# SCH_3_0-CONTROLADORA-PARA-PS2_2024-07-29.net
KiCad netlist of a schematic drawn in EasyEDA
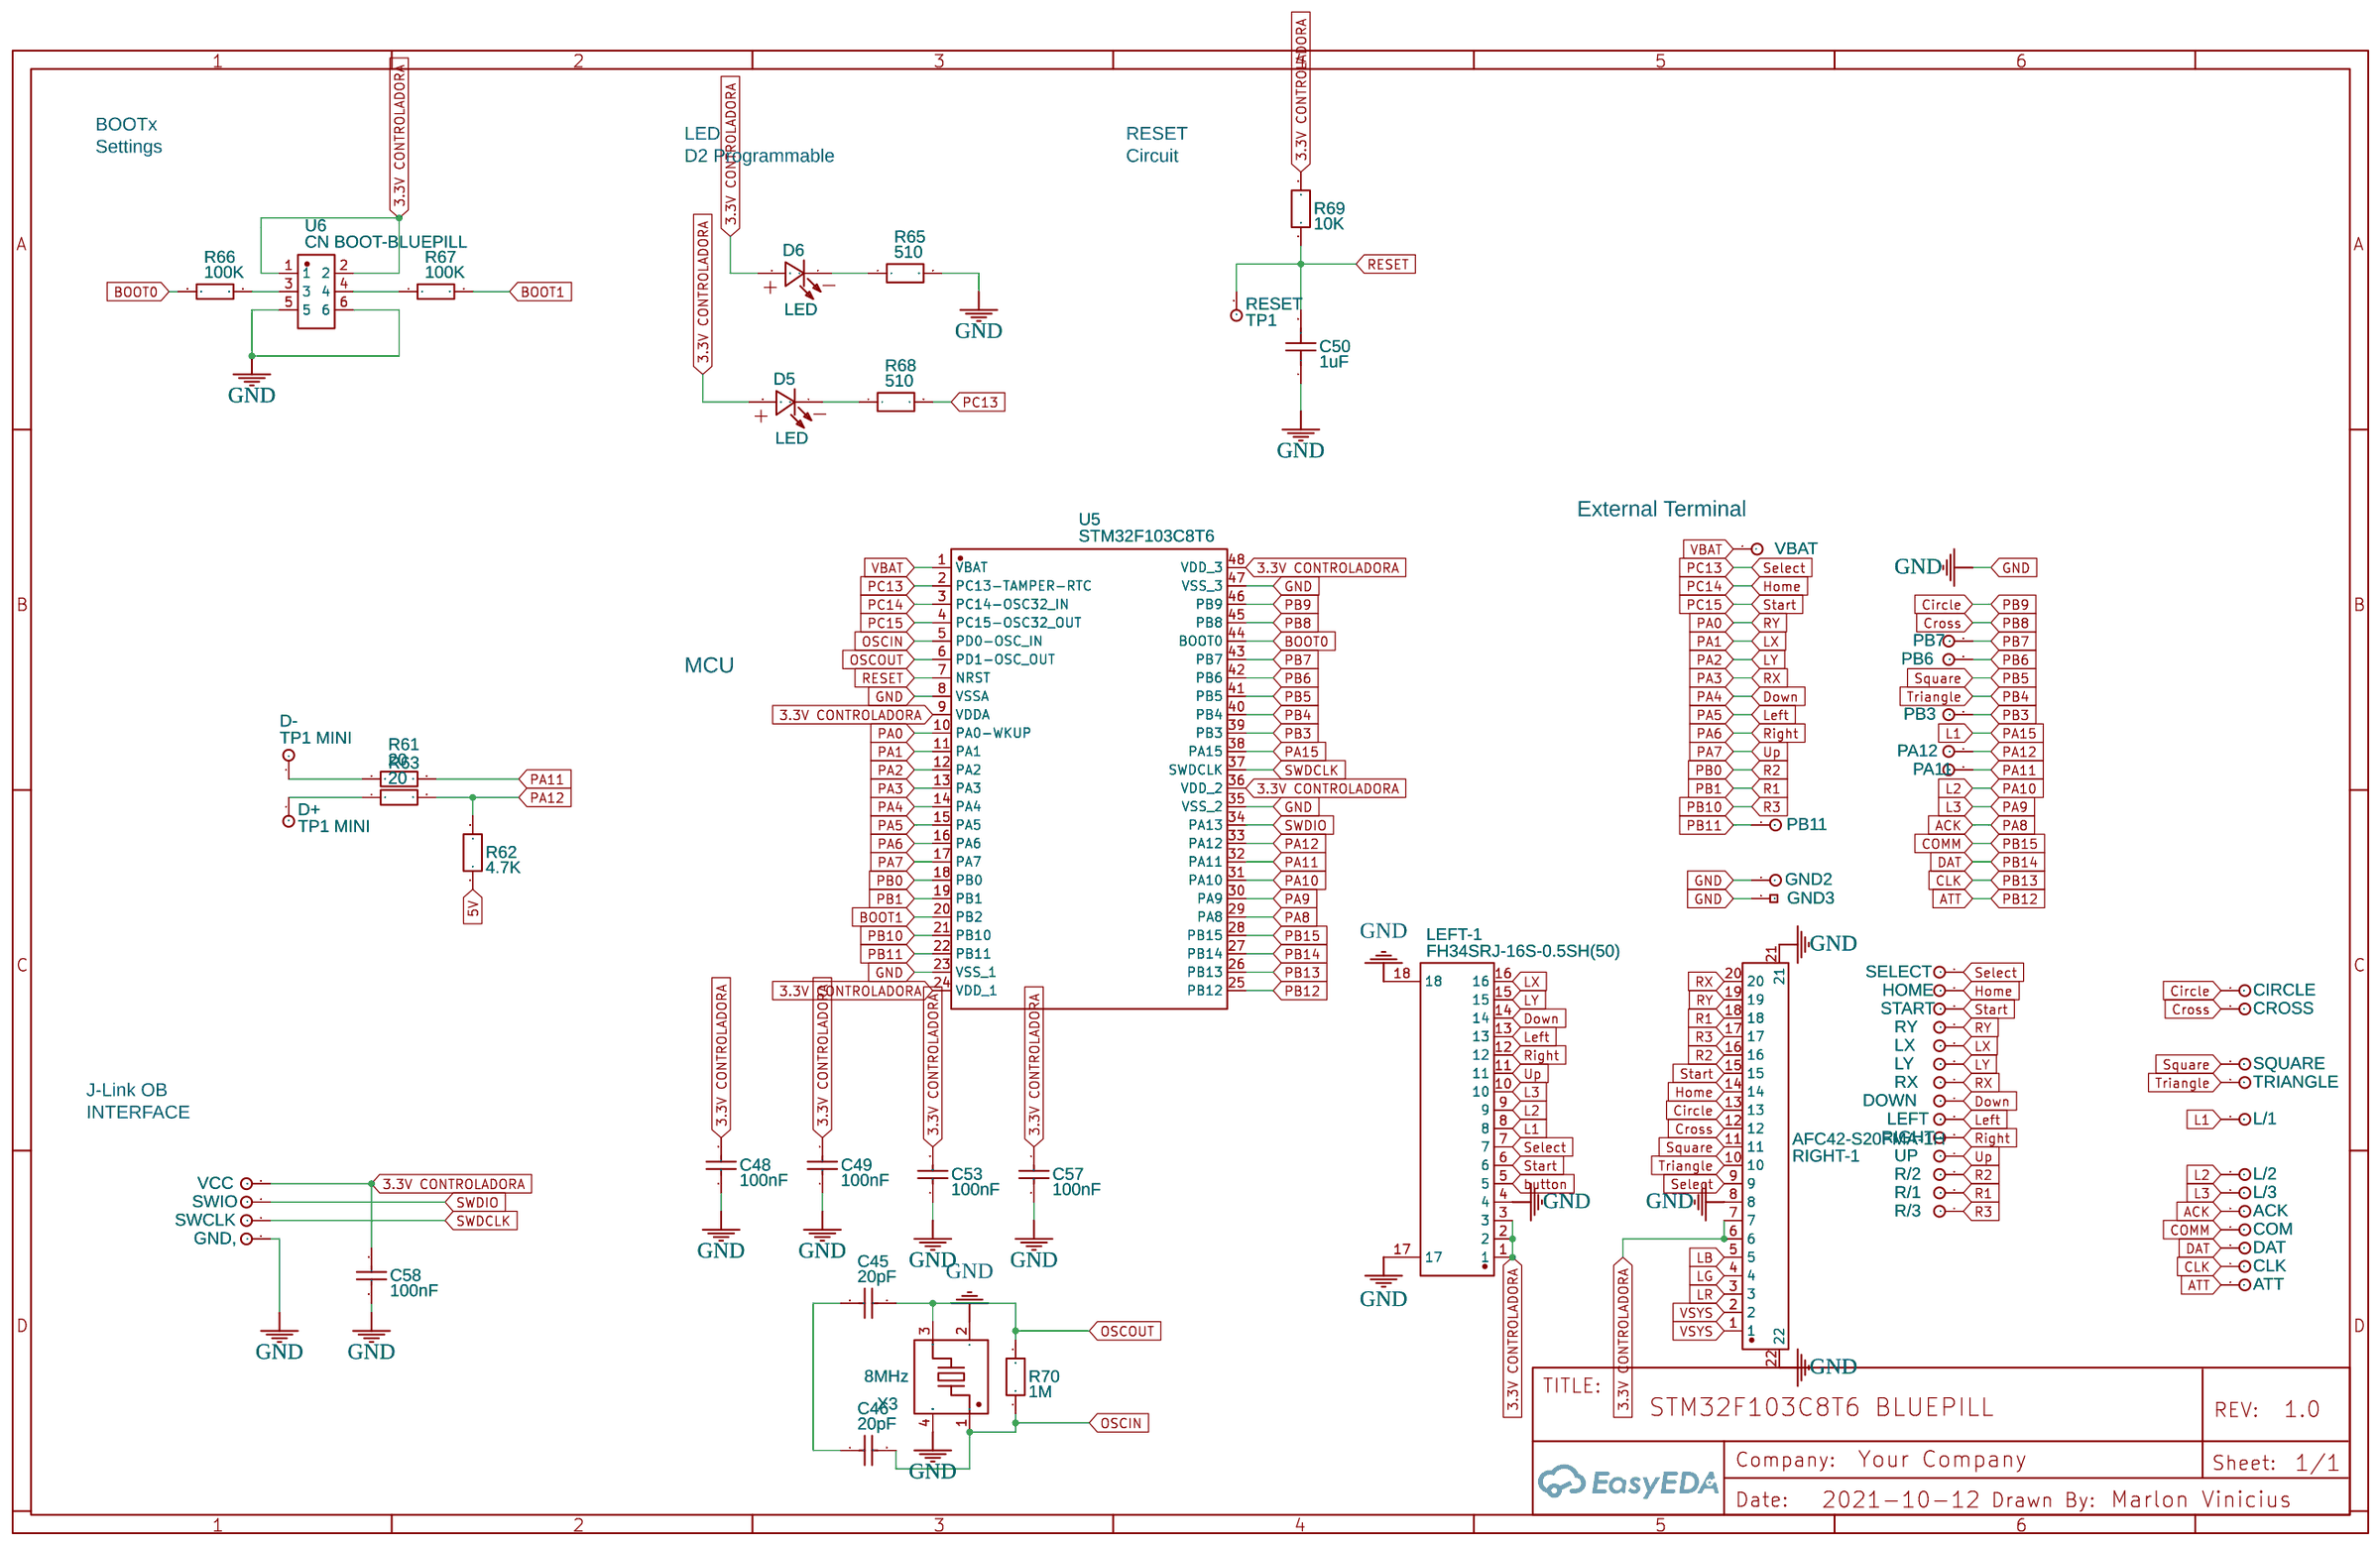
[diagram p0: STM32 BLUEPILL copy]
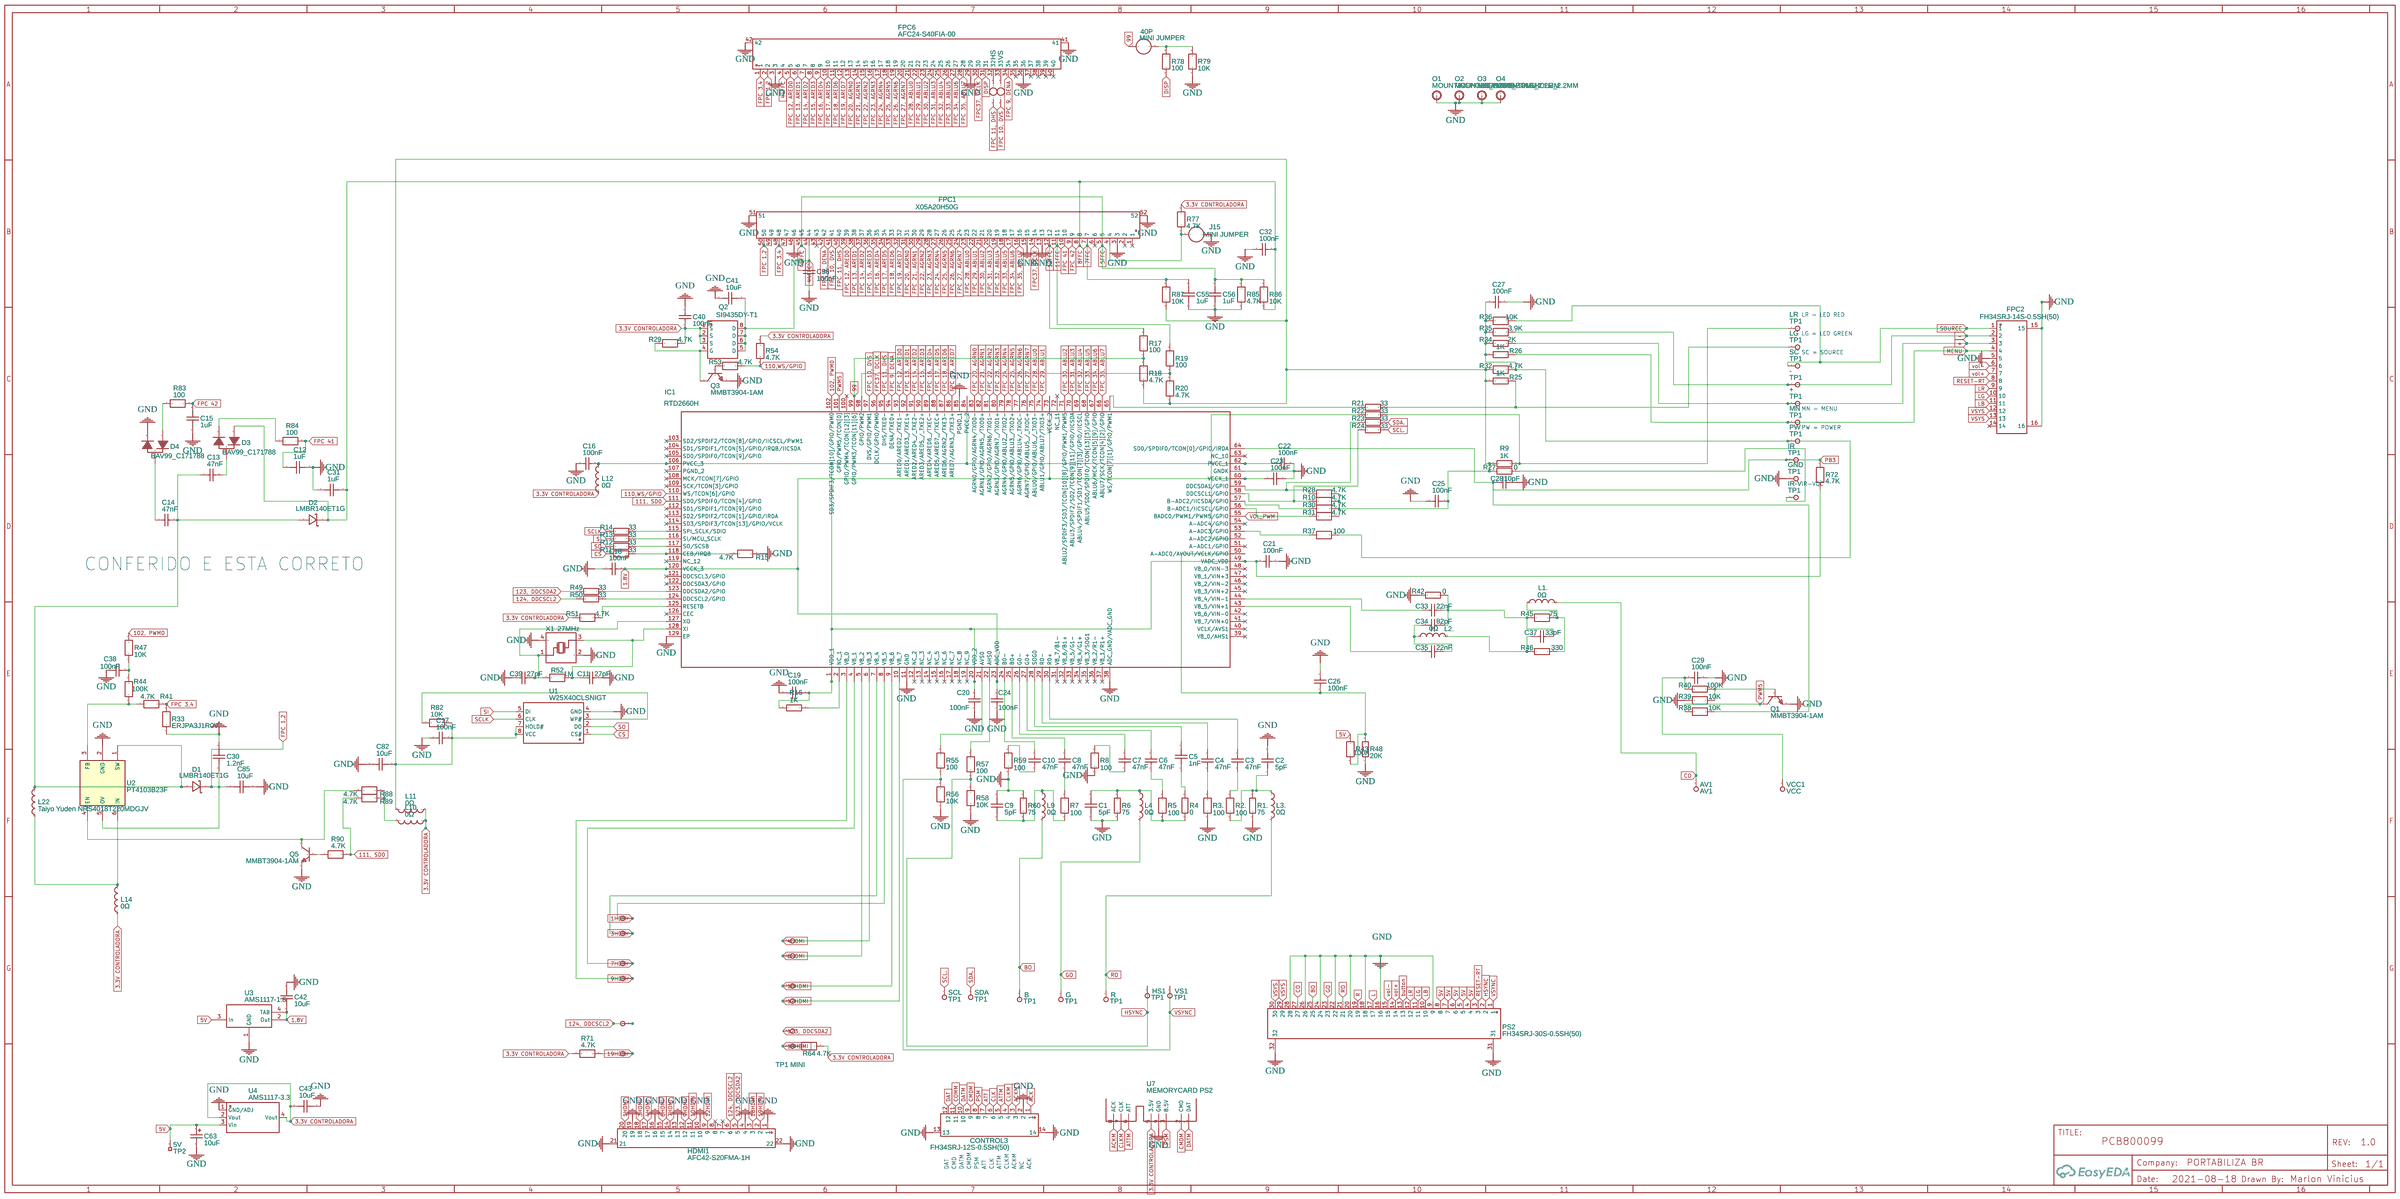
[diagram p1: Controladora copy]
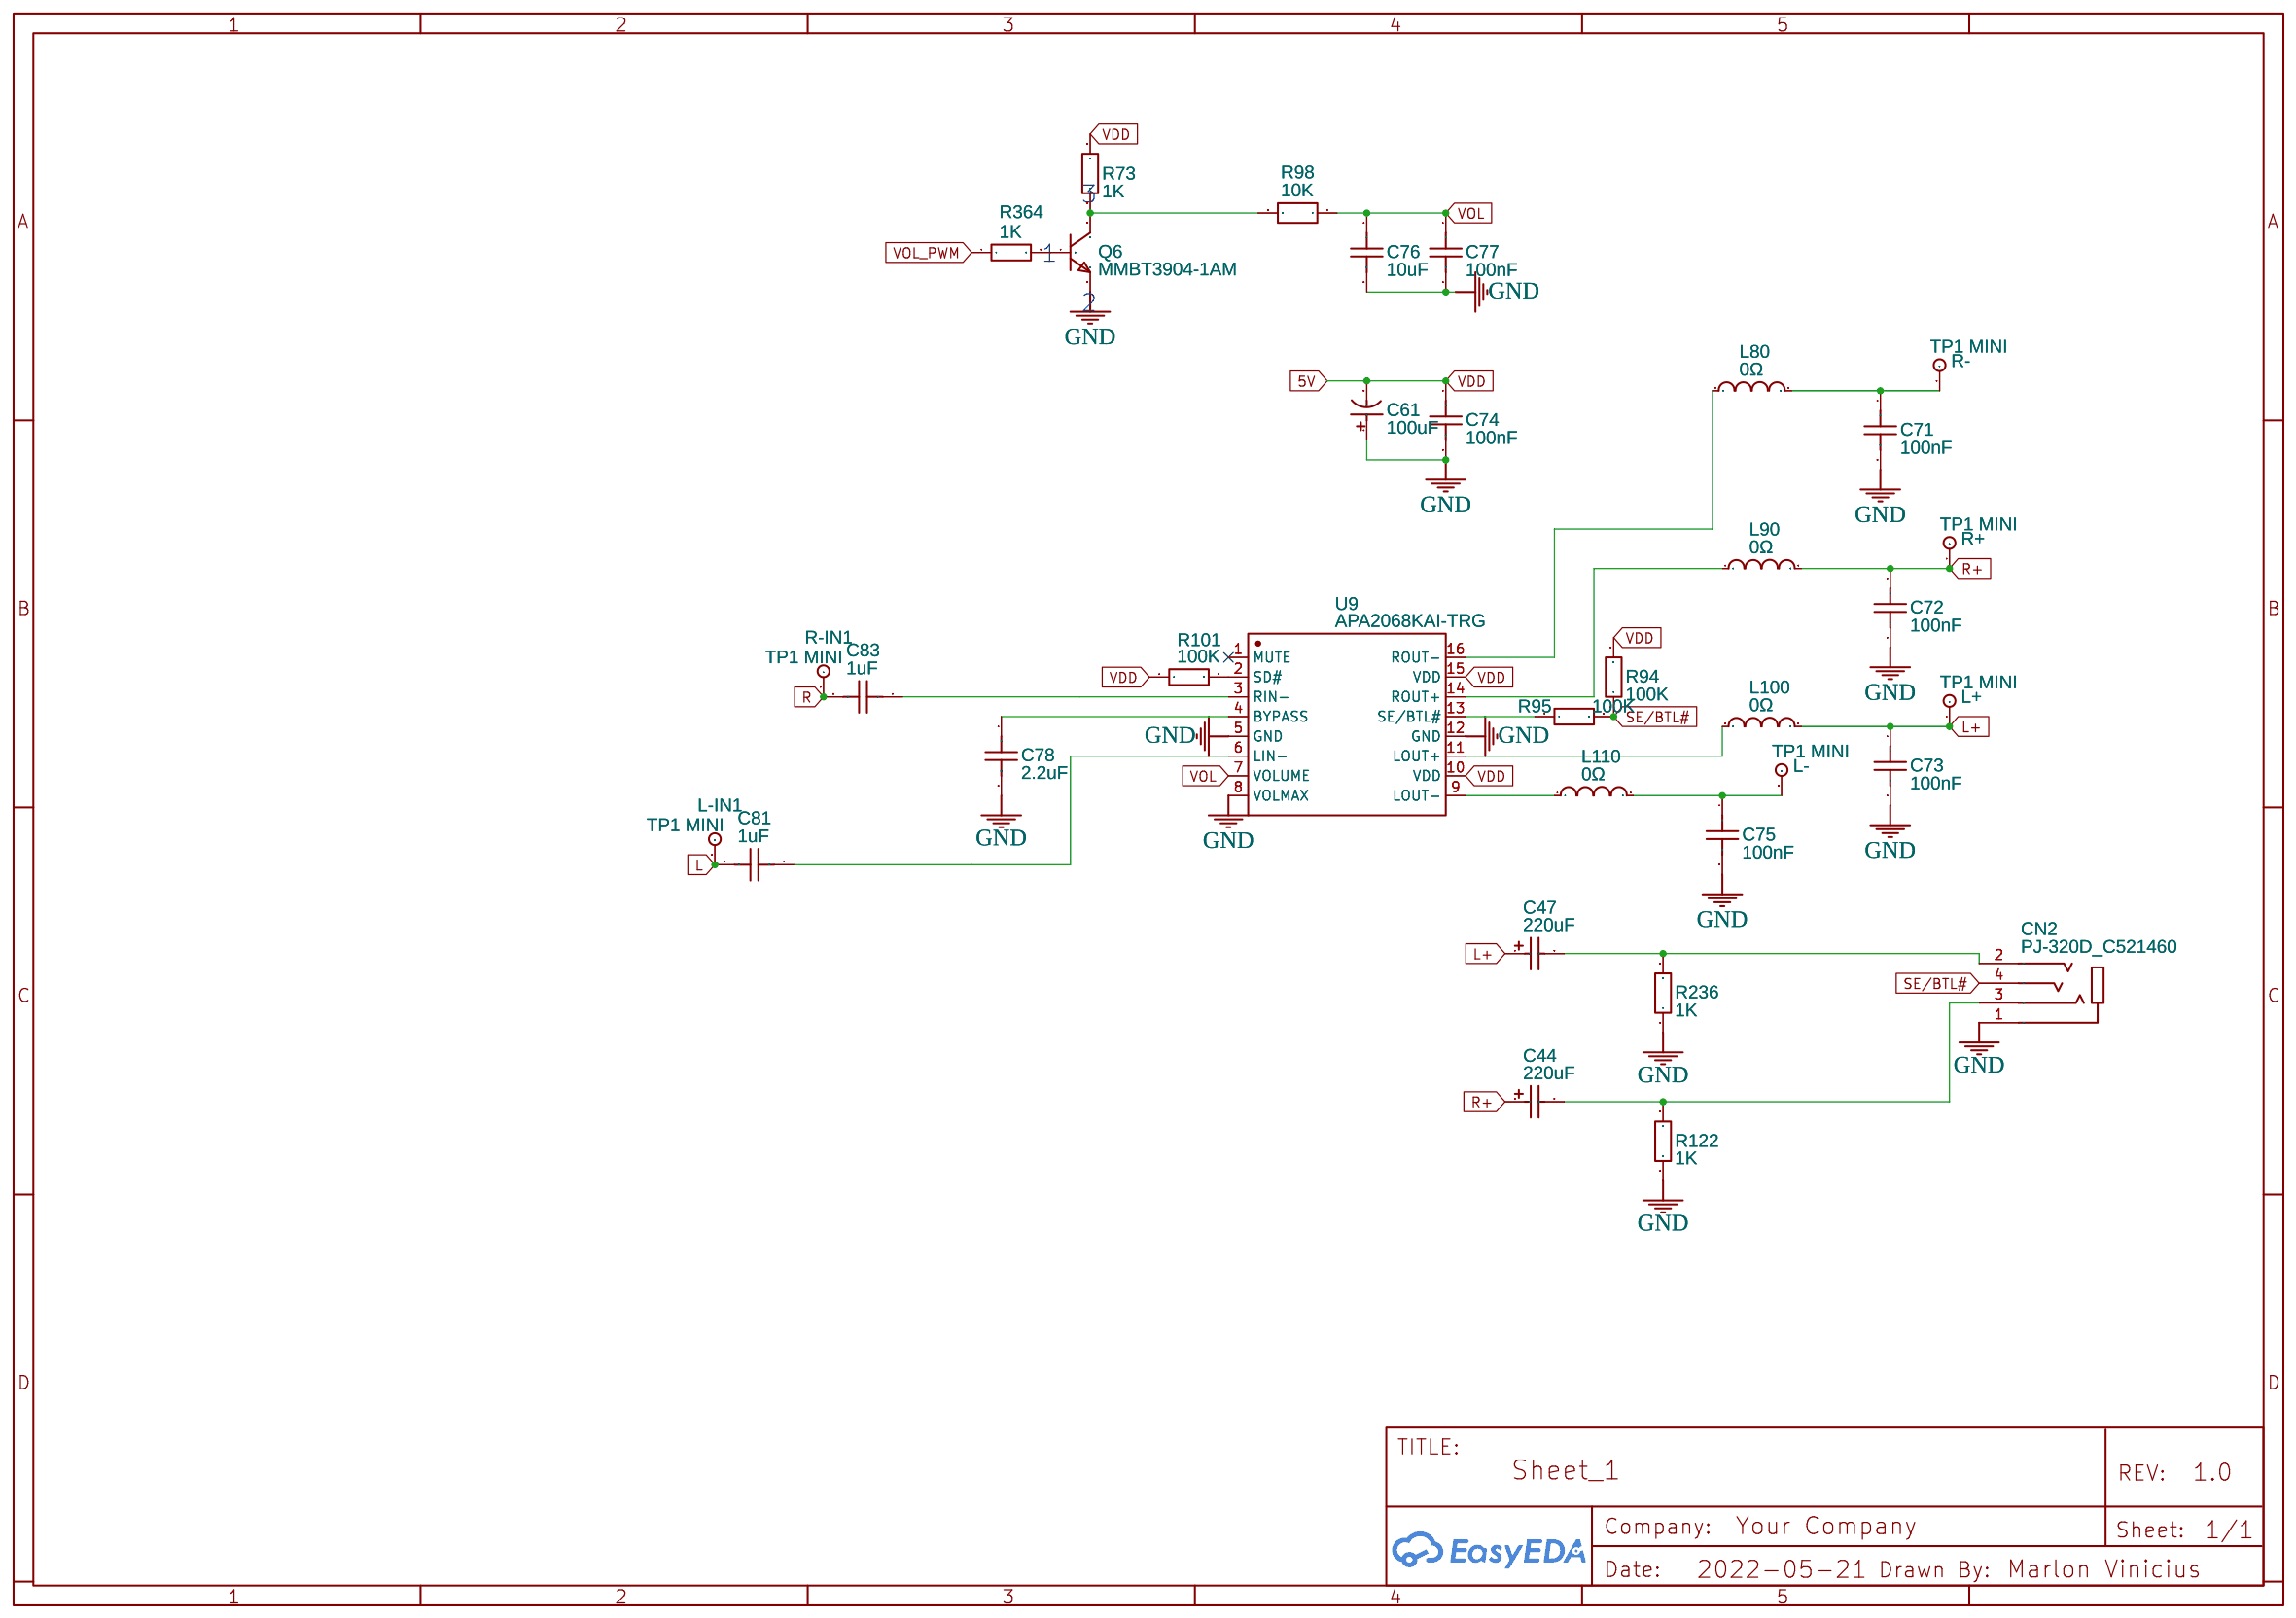
[diagram p2: AUDIO]
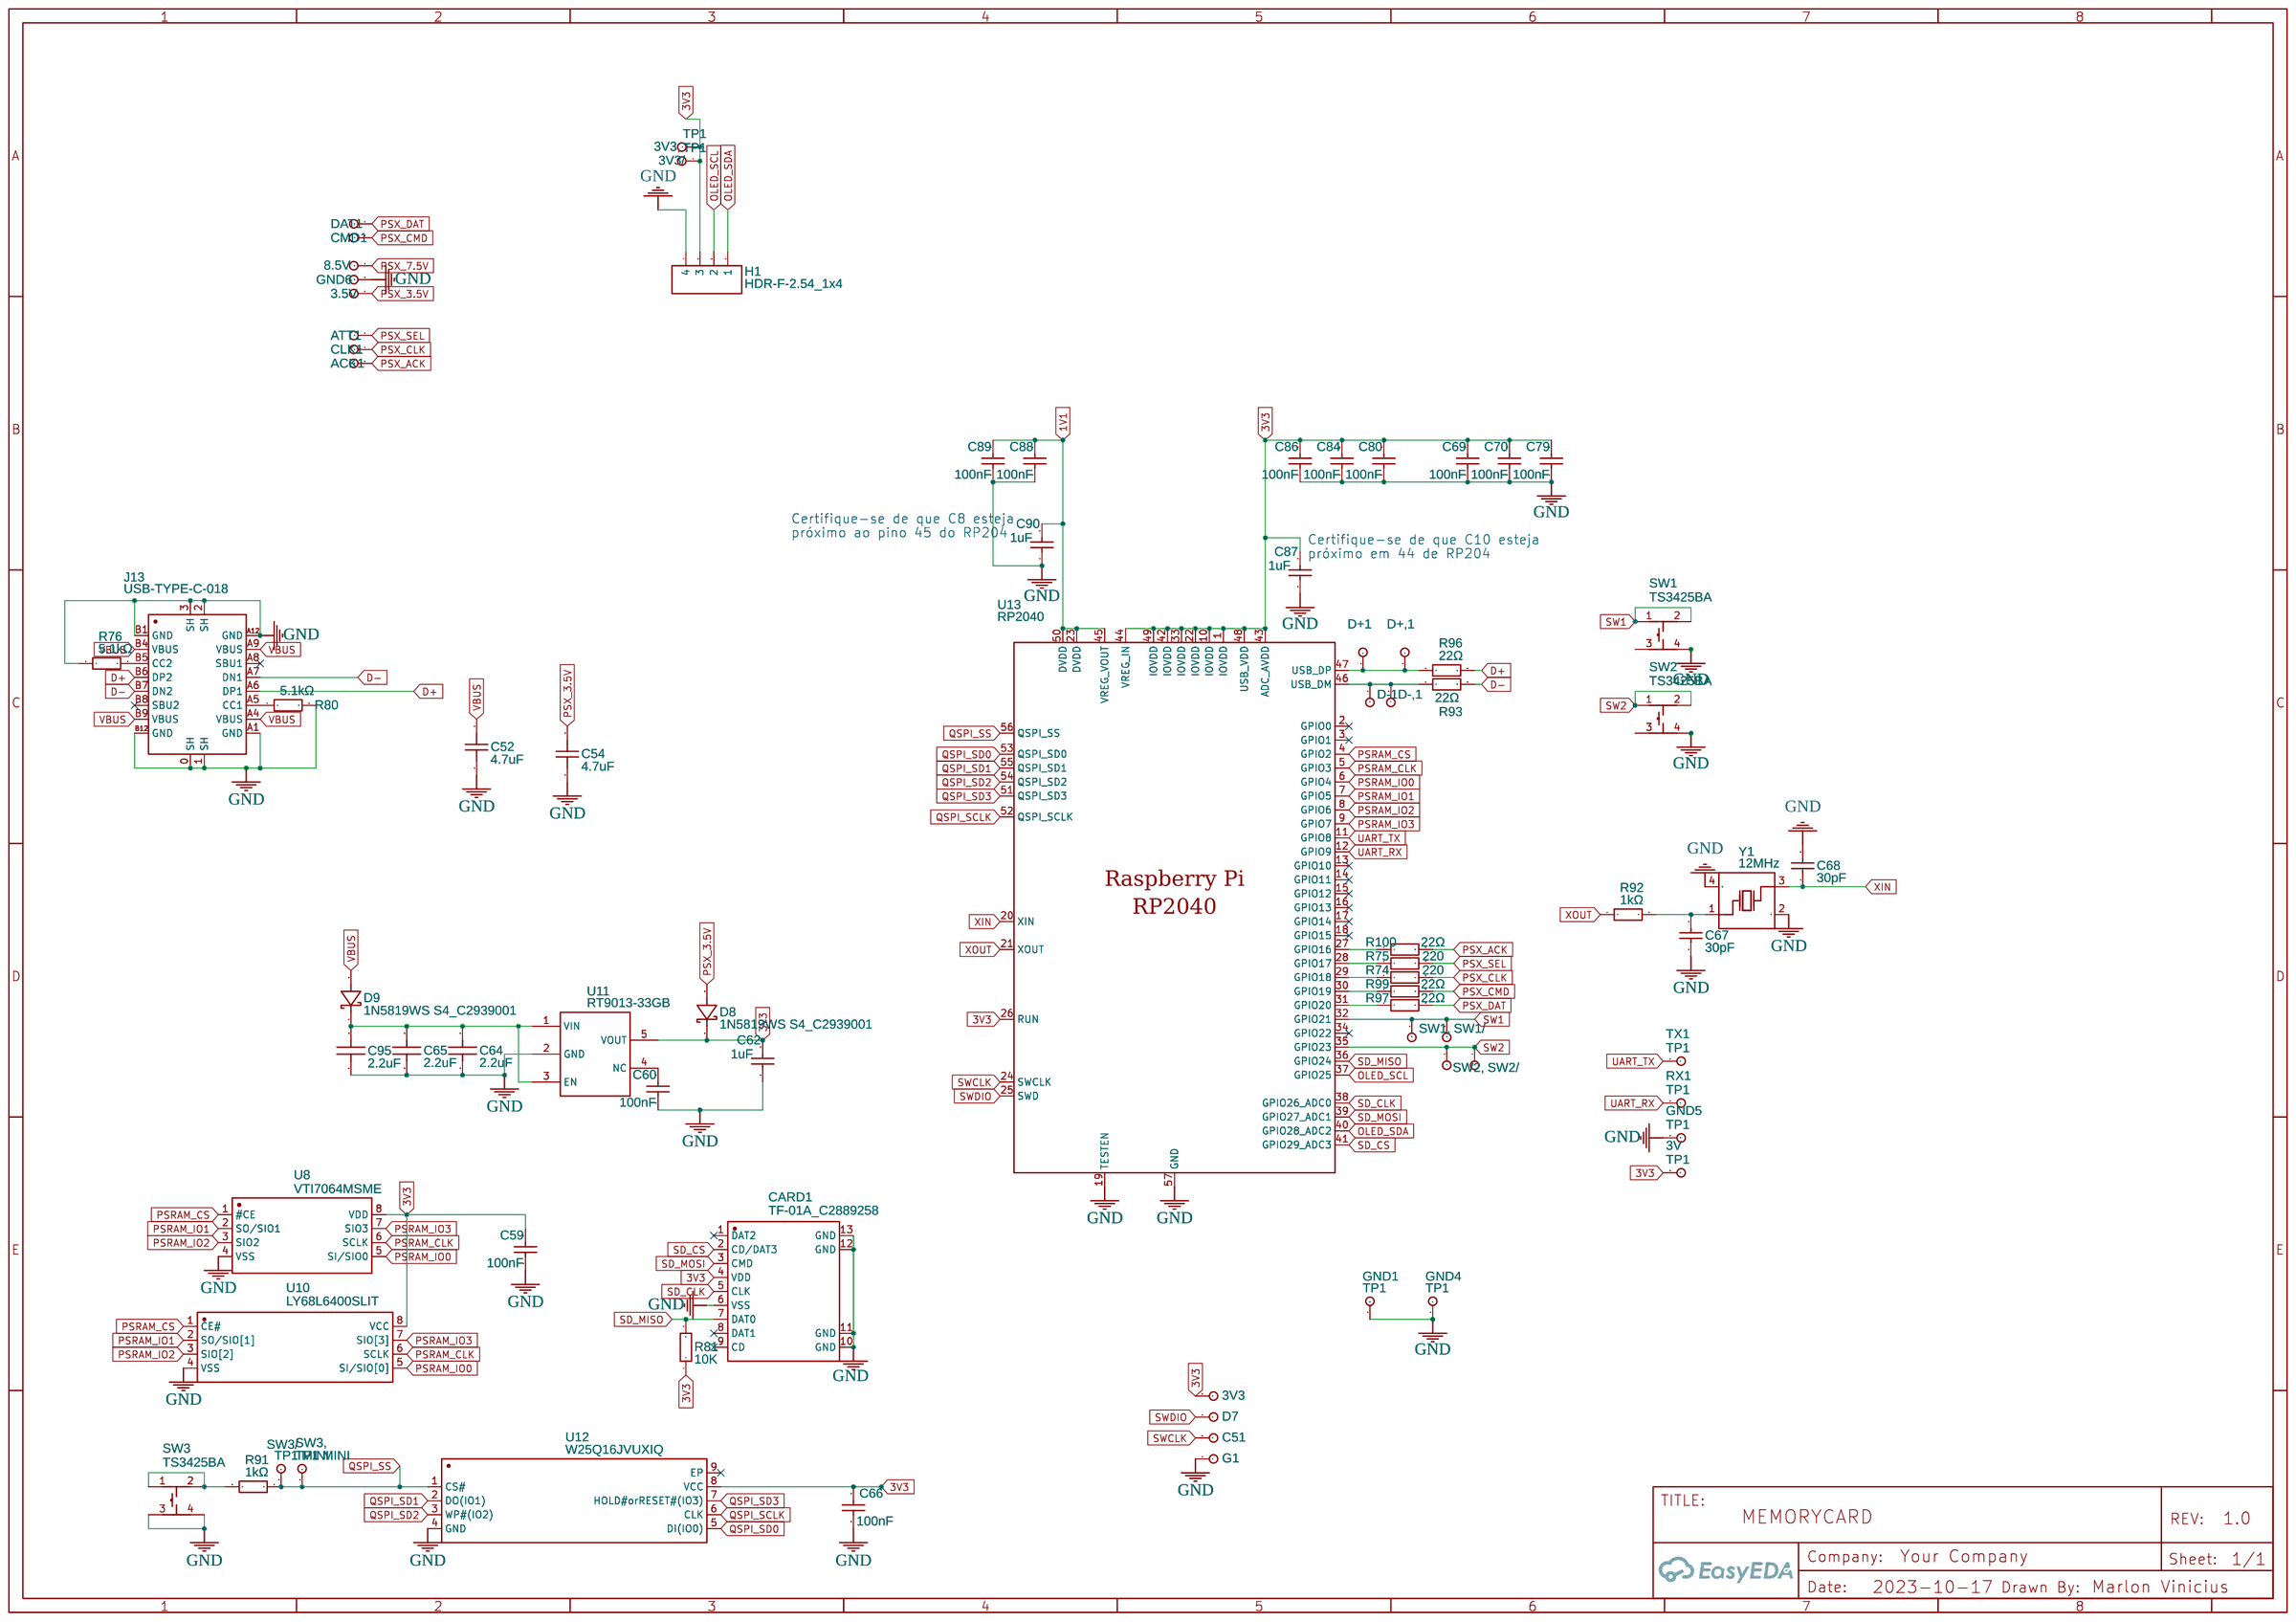
[diagram p3: MEMORYCARD]

(export (version "E")
  (design (tool "Eeschema 10.0.6"))
  (components
    (comp (ref "ACK") (value "TP1 MINI") (libsource (lib "") (part "TP1 MINI_27")))
    (comp (ref "ATT") (value "TP1 MINI") (libsource (lib "") (part "TP1 MINI_18")))
    (comp (ref "C45")
      (value "20pF")
      (fields (field (name "Manufacturer Part") "CC0402JRNPO9BN200") (field (name "Manufacturer") "YAGEO"))
      (libsource (lib "") (part "CC0402JRNPO9BN200"))
    )
    (comp (ref "C46")
      (value "20pF")
      (fields (field (name "Manufacturer Part") "CC0402JRNPO9BN200") (field (name "Manufacturer") "YAGEO"))
      (libsource (lib "") (part "CC0402JRNPO9BN200"))
    )
    (comp (ref "C48")
      (value "100nF")
      (fields (field (name "Manufacturer Part") "CC0402KRX7R8BB104") (field (name "Manufacturer") "YAGEO"))
      (libsource (lib "") (part "CC0402KRX7R8BB104"))
    )
    (comp (ref "C49")
      (value "100nF")
      (fields (field (name "Manufacturer Part") "CC0402KRX7R8BB104") (field (name "Manufacturer") "YAGEO"))
      (libsource (lib "") (part "CC0402KRX7R8BB104"))
    )
    (comp (ref "C50")
      (value "1uF")
      (fields (field (name "Manufacturer Part") "CL05A105KA5NQNC") (field (name "Manufacturer") "SAMSUNG"))
      (libsource (lib "") (part "CL05A105KA5NQNC"))
    )
    (comp (ref "C53")
      (value "100nF")
      (fields (field (name "Manufacturer Part") "CC0402KRX7R8BB104") (field (name "Manufacturer") "YAGEO"))
      (libsource (lib "") (part "CC0402KRX7R8BB104"))
    )
    (comp (ref "C57")
      (value "100nF")
      (fields (field (name "Manufacturer Part") "CC0402KRX7R8BB104") (field (name "Manufacturer") "YAGEO"))
      (libsource (lib "") (part "CC0402KRX7R8BB104"))
    )
    (comp (ref "C58")
      (value "100nF")
      (fields (field (name "Manufacturer Part") "CC0402KRX7R8BB104") (field (name "Manufacturer") "YAGEO"))
      (libsource (lib "") (part "CC0402KRX7R8BB104"))
    )
    (comp (ref "CIRCLE") (value "TP1 MINI") (libsource (lib "") (part "TP1 MINI_13")))
    (comp (ref "CLK") (value "TP1 MINI") (libsource (lib "") (part "TP1 MINI_7")))
    (comp (ref "COM") (value "TP1 MINI") (libsource (lib "") (part "TP1 MINI_6")))
    (comp (ref "CROSS") (value "TP1 MINI") (libsource (lib "") (part "TP1 MINI_14")))
    (comp (ref "D+") (value "TP1 MINI") (libsource (lib "") (part "TP1 MINI_24")))
    (comp (ref "D-") (value "TP1 MINI") (libsource (lib "") (part "TP1 MINI_11")))
    (comp (ref "D5")
      (value "LED")
      (fields
        (field (name "Manufacturer Part") "TJ-S2005SW9TGLC0A-A5")
        (field (name "Manufacturer") "TOGIALED")
      )
      (libsource (lib "") (part "TJ-S2005SW9TGLC0A-A5"))
    )
    (comp (ref "D6")
      (value "LED")
      (fields
        (field (name "Manufacturer Part") "TJ-S2005SW9TGLC0A-A5")
        (field (name "Manufacturer") "TOGIALED")
      )
      (libsource (lib "") (part "TJ-S2005SW9TGLC0A-A5"))
    )
    (comp (ref "DAT") (value "TP1 MINI") (libsource (lib "") (part "TP1 MINI_1")))
    (comp (ref "DOWN") (value "TP1 MINI") (libsource (lib "") (part "TP1 MINI_10")))
    (comp (ref "GND,") (value "TP1") (libsource (lib "") (part "TP1_2")))
    (comp (ref "GND2") (value "TP1") (libsource (lib "") (part "TP1_1")))
    (comp (ref "GND3") (value "TP2") (libsource (lib "") (part "TP2")))
    (comp (ref "HOME") (value "TP1 MINI") (libsource (lib "") (part "TP1 MINI_16")))
    (comp (ref "L/1") (value "TP1 MINI") (libsource (lib "") (part "TP1 MINI_5")))
    (comp (ref "L/2") (value "TP1 MINI") (libsource (lib "") (part "TP1 MINI_5")))
    (comp (ref "L/3") (value "TP1 MINI") (libsource (lib "") (part "TP1 MINI_5")))
    (comp (ref "LEFT") (value "TP1 MINI") (libsource (lib "") (part "TP1 MINI_20")))
    (comp (ref "LEFT-1")
      (value "FH34SRJ-16S-0.5SH(50)")
      (fields (field (name "Manufacturer") "Hirose"))
      (libsource (lib "") (part "FH34SRJ-16S-0.5SH(50)"))
    )
    (comp (ref "LX") (value "TP1 MINI") (libsource (lib "") (part "TP1 MINI_25")))
    (comp (ref "LY") (value "TP1 MINI") (libsource (lib "") (part "TP1 MINI")))
    (comp (ref "PA11") (value "TP1 MINI") (libsource (lib "") (part "TP1 MINI_23")))
    (comp (ref "PA12") (value "TP1 MINI") (libsource (lib "") (part "TP1 MINI_23")))
    (comp (ref "PB3") (value "TP1 MINI") (libsource (lib "") (part "TP1 MINI_21")))
    (comp (ref "PB6") (value "TP1 MINI") (libsource (lib "") (part "TP1 MINI_21")))
    (comp (ref "PB7") (value "TP1 MINI") (libsource (lib "") (part "TP1 MINI_21")))
    (comp (ref "PB11") (value "TP1 MINI") (libsource (lib "") (part "TP1 MINI_15")))
    (comp (ref "R/1") (value "TP1 MINI") (libsource (lib "") (part "TP1 MINI_3")))
    (comp (ref "R/2") (value "TP1 MINI") (libsource (lib "") (part "TP1 MINI_3")))
    (comp (ref "R/3") (value "TP1 MINI") (libsource (lib "") (part "TP1 MINI_3")))
    (comp (ref "R61")
      (value "20")
      (fields (field (name "Manufacturer Part") "RC0402FR-0720RL") (field (name "Manufacturer") "YAGEO"))
      (libsource (lib "") (part "RC0402FR-0720RL"))
    )
    (comp (ref "R62")
      (value "4.7K")
      (fields (field (name "Manufacturer Part") "ERJPA2F4701X") (field (name "Manufacturer") "PANASONIC"))
      (libsource (lib "") (part "ERJPA2F4701X"))
    )
    (comp (ref "R63")
      (value "20")
      (fields (field (name "Manufacturer Part") "RC0402FR-0720RL") (field (name "Manufacturer") "YAGEO"))
      (libsource (lib "") (part "RC0402FR-0720RL"))
    )
    (comp (ref "R65")
      (value "510")
      (fields (field (name "Manufacturer Part") "ERJ2RKF5100X") (field (name "Manufacturer") "PANASONIC"))
      (libsource (lib "") (part "ERJ2RKF5100X"))
    )
    (comp (ref "R66")
      (value "100K")
      (fields (field (name "Manufacturer Part") "RC0402FR-07100KL") (field (name "Manufacturer") "YAGEO"))
      (libsource (lib "") (part "RC0402FR-07100KL"))
    )
    (comp (ref "R67")
      (value "100K")
      (fields (field (name "Manufacturer Part") "RC0402FR-07100KL") (field (name "Manufacturer") "YAGEO"))
      (libsource (lib "") (part "RC0402FR-07100KL"))
    )
    (comp (ref "R68")
      (value "510")
      (fields (field (name "Manufacturer Part") "ERJ2RKF5100X") (field (name "Manufacturer") "PANASONIC"))
      (libsource (lib "") (part "ERJ2RKF5100X"))
    )
    (comp (ref "R69")
      (value "10K")
      (fields (field (name "Manufacturer Part") "ERJPA2F1002X") (field (name "Manufacturer") "PANASONIC"))
      (libsource (lib "") (part "ERJPA2F1002X"))
    )
    (comp (ref "R70")
      (value "1M")
      (fields (field (name "Manufacturer Part") "ERJPA2J105X") (field (name "Manufacturer") "PANASONIC"))
      (libsource (lib "") (part "ERJPA2J105X"))
    )
    (comp (ref "RESET") (value "TP1") (libsource (lib "") (part "TP1")))
    (comp (ref "RIGHT") (value "TP1 MINI") (libsource (lib "") (part "TP1 MINI_9")))
    (comp (ref "RIGHT-1")
      (value "AFC42-S20FMA-1H")
      (fields (field (name "Manufacturer") "JUSHUO"))
      (libsource (lib "") (part "AFC42-S20FMA-1H"))
    )
    (comp (ref "RX") (value "TP1 MINI") (libsource (lib "") (part "TP1 MINI_19")))
    (comp (ref "RY") (value "TP1 MINI") (libsource (lib "") (part "TP1 MINI_17")))
    (comp (ref "SELECT") (value "TP1 MINI") (libsource (lib "") (part "TP1 MINI_2")))
    (comp (ref "SQUARE") (value "TP1 MINI") (libsource (lib "") (part "TP1 MINI_12")))
    (comp (ref "START") (value "TP1 MINI") (libsource (lib "") (part "TP1 MINI_26")))
    (comp (ref "SWCLK") (value "TP1") (libsource (lib "") (part "TP1_4")))
    (comp (ref "SWIO") (value "TP1") (libsource (lib "") (part "TP1_3")))
    (comp (ref "TRIANGLE") (value "TP1 MINI") (libsource (lib "") (part "TP1 MINI_22")))
    (comp (ref "U5")
      (value "STM32F103C8T6")
      (fields (field (name "Manufacturer") "STMicroelectronics"))
      (libsource (lib "") (part "STM32F103C8T6"))
    )
    (comp (ref "U6") (value "CN BOOT-BLUEPILL") (libsource (lib "") (part "CN BOOT-BLUEPILL")))
    (comp (ref "UP") (value "TP1 MINI") (libsource (lib "") (part "TP1 MINI_8")))
    (comp (ref "VBAT") (value "TP1 MINI") (libsource (lib "") (part "TP1 MINI_4")))
    (comp (ref "VCC") (value "TP1") (libsource (lib "") (part "TP1_5")))
    (comp (ref "X3")
      (value "8MHz")
      (fields
        (field (name "Manufacturer Part") "3225-8.00-10-10-10/A")
        (field (name "Manufacturer") "Suzhou Liming Elec")
      )
      (libsource (lib "") (part "3225-8.00-10-10-10/A"))
    )
    (comp (ref "+") (value "TP1") (libsource (lib "") (part "TP1_15")))
    (comp (ref "-") (value "TP1") (libsource (lib "") (part "TP1_7")))
    (comp (ref "5V") (value "TP2") (libsource (lib "") (part "TP2")))
    (comp (ref "40P") (value "MINI JUMPER") (libsource (lib "") (part "MINI JUMPER_3")))
    (comp (ref "AV1") (value "AV1") (libsource (lib "") (part "TP1_11")))
    (comp (ref "B") (value "TP1") (libsource (lib "") (part "TP1_6")))
    (comp (ref "C1")
      (value "5pF")
      (fields (field (name "Manufacturer Part") "CC0402CRNPO9BN5R0") (field (name "Manufacturer") "YAGEO"))
      (libsource (lib "") (part "CC0402CRNPO9BN5R0"))
    )
    (comp (ref "C2")
      (value "5pF")
      (fields (field (name "Manufacturer Part") "CC0402CRNPO9BN5R0") (field (name "Manufacturer") "YAGEO"))
      (libsource (lib "") (part "CC0402CRNPO9BN5R0"))
    )
    (comp (ref "C3")
      (value "47nF")
      (fields (field (name "Manufacturer Part") "GRM155R71C473KA01D") (field (name "Manufacturer") "MuRata"))
      (libsource (lib "") (part "GRM155R71C473KA01D"))
    )
    (comp (ref "C4")
      (value "47nF")
      (fields (field (name "Manufacturer Part") "GRM155R71C473KA01D") (field (name "Manufacturer") "MuRata"))
      (libsource (lib "") (part "GRM155R71C473KA01D"))
    )
    (comp (ref "C5")
      (value "1nF")
      (fields (field (name "Manufacturer Part") "CC0402JRNPO8BN102") (field (name "Manufacturer") "YAGEO"))
      (libsource (lib "") (part "CC0402JRNPO8BN102"))
    )
    (comp (ref "C6")
      (value "47nF")
      (fields (field (name "Manufacturer Part") "GRM155R71C473KA01D") (field (name "Manufacturer") "MuRata"))
      (libsource (lib "") (part "GRM155R71C473KA01D"))
    )
    (comp (ref "C7")
      (value "47nF")
      (fields (field (name "Manufacturer Part") "GRM155R71C473KA01D") (field (name "Manufacturer") "MuRata"))
      (libsource (lib "") (part "GRM155R71C473KA01D"))
    )
    (comp (ref "C8")
      (value "47nF")
      (fields (field (name "Manufacturer Part") "GRM155R71C473KA01D") (field (name "Manufacturer") "MuRata"))
      (libsource (lib "") (part "GRM155R71C473KA01D"))
    )
    (comp (ref "C9")
      (value "5pF")
      (fields (field (name "Manufacturer Part") "CC0402CRNPO9BN5R0") (field (name "Manufacturer") "YAGEO"))
      (libsource (lib "") (part "CC0402CRNPO9BN5R0"))
    )
    (comp (ref "C10")
      (value "47nF")
      (fields (field (name "Manufacturer Part") "GRM155R71C473KA01D") (field (name "Manufacturer") "MuRata"))
      (libsource (lib "") (part "GRM155R71C473KA01D"))
    )
    (comp (ref "C11")
      (value "27pF")
      (fields (field (name "Manufacturer Part") "GCM1555C1H270JA16D") (field (name "Manufacturer") "MuRata"))
      (libsource (lib "") (part "GCM1555C1H270JA16D"))
    )
    (comp (ref "C12")
      (value "1uF")
      (fields (field (name "Manufacturer Part") "CL05A105KA5NQNC") (field (name "Manufacturer") "SAMSUNG"))
      (libsource (lib "") (part "CL05A105KA5NQNC_1"))
    )
    (comp (ref "C13")
      (value "47nF")
      (fields (field (name "Manufacturer Part") "CC0402KRX7R8BB473") (field (name "Manufacturer") "YAGEO"))
      (libsource (lib "") (part "CC0402KRX7R8BB473"))
    )
    (comp (ref "C14")
      (value "47nF")
      (fields (field (name "Manufacturer Part") "CC0402KRX7R8BB473") (field (name "Manufacturer") "YAGEO"))
      (libsource (lib "") (part "CC0402KRX7R8BB473"))
    )
    (comp (ref "C15")
      (value "1uF")
      (fields (field (name "Manufacturer Part") "CL05A105KA5NQNC") (field (name "Manufacturer") "SAMSUNG"))
      (libsource (lib "") (part "CL05A105KA5NQNC"))
    )
    (comp (ref "C16")
      (value "100nF")
      (fields (field (name "Manufacturer Part") "CC0402KRX7R8BB104") (field (name "Manufacturer") "YAGEO"))
      (libsource (lib "") (part "CC0402KRX7R8BB104"))
    )
    (comp (ref "C17")
      (value "100nF")
      (fields (field (name "Manufacturer Part") "CC0402KRX7R8BB104") (field (name "Manufacturer") "YAGEO"))
      (libsource (lib "") (part "CC0402KRX7R8BB104"))
    )
    (comp (ref "C18")
      (value "100nF")
      (fields (field (name "Manufacturer Part") "CC0402KRX7R8BB104") (field (name "Manufacturer") "YAGEO"))
      (libsource (lib "") (part "CC0402KRX7R8BB104"))
    )
    (comp (ref "C19")
      (value "100nF")
      (fields (field (name "Manufacturer Part") "CC0402JRX7R6BB104") (field (name "Manufacturer") "YAGEO"))
      (libsource (lib "") (part "CC0402JRX7R6BB104"))
    )
    (comp (ref "C20")
      (value "100nF")
      (fields (field (name "Manufacturer Part") "CC0402KRX7R8BB104") (field (name "Manufacturer") "YAGEO"))
      (libsource (lib "") (part "CC0402KRX7R8BB104_1"))
    )
    (comp (ref "C21")
      (value "100nF")
      (fields (field (name "Manufacturer Part") "CC0402KRX7R8BB104") (field (name "Manufacturer") "YAGEO"))
      (libsource (lib "") (part "CC0402KRX7R8BB104"))
    )
    (comp (ref "C22")
      (value "100nF")
      (fields (field (name "Manufacturer Part") "CC0402KRX7R8BB104") (field (name "Manufacturer") "YAGEO"))
      (libsource (lib "") (part "CC0402KRX7R8BB104"))
    )
    (comp (ref "C23")
      (value "100nF")
      (fields (field (name "Manufacturer Part") "CC0402KRX7R8BB104") (field (name "Manufacturer") "YAGEO"))
      (libsource (lib "") (part "CC0402KRX7R8BB104"))
    )
    (comp (ref "C24")
      (value "100nF")
      (fields (field (name "Manufacturer Part") "CC0402KRX7R8BB104") (field (name "Manufacturer") "YAGEO"))
      (libsource (lib "") (part "CC0402KRX7R8BB104_1"))
    )
    (comp (ref "C25")
      (value "100nF")
      (fields (field (name "Manufacturer Part") "CC0402KRX7R8BB104") (field (name "Manufacturer") "YAGEO"))
      (libsource (lib "") (part "CC0402KRX7R8BB104"))
    )
    (comp (ref "C26")
      (value "100nF")
      (fields (field (name "Manufacturer Part") "CC0402KRX7R8BB104") (field (name "Manufacturer") "YAGEO"))
      (libsource (lib "") (part "CC0402KRX7R8BB104_1"))
    )
    (comp (ref "C27")
      (value "100nF")
      (fields (field (name "Manufacturer Part") "CC0402KRX7R8BB104") (field (name "Manufacturer") "YAGEO"))
      (libsource (lib "") (part "CC0402KRX7R8BB104"))
    )
    (comp (ref "C28")
      (value "10pF")
      (fields (field (name "Manufacturer Part") "CC0402JRNPO9BN100") (field (name "Manufacturer") "YAGEO"))
      (libsource (lib "") (part "CC0402JRNPO9BN100"))
    )
    (comp (ref "C29")
      (value "100nF")
      (fields (field (name "Manufacturer Part") "CC0402KRX7R8BB104") (field (name "Manufacturer") "YAGEO"))
      (libsource (lib "") (part "CC0402KRX7R8BB104"))
    )
    (comp (ref "C30")
      (value "1.2nF")
      (fields (field (name "Manufacturer Part") "0402B122M500CT") (field (name "Manufacturer") "Huaxin S&T"))
      (libsource (lib "") (part "0402B122M500CT"))
    )
    (comp (ref "C31")
      (value "1uF")
      (fields (field (name "Manufacturer Part") "CL05A105KA5NQNC") (field (name "Manufacturer") "SAMSUNG"))
      (libsource (lib "") (part "CL05A105KA5NQNC_1"))
    )
    (comp (ref "C32")
      (value "100nF")
      (fields (field (name "Manufacturer Part") "CC0402KRX7R8BB104") (field (name "Manufacturer") "YAGEO"))
      (libsource (lib "") (part "CC0402KRX7R8BB104"))
    )
    (comp (ref "C33")
      (value "22nF")
      (fields (field (name "Manufacturer Part") "CC0402KRX7R9BB223") (field (name "Manufacturer") "YAGEO"))
      (libsource (lib "") (part "CC0402KRX7R9BB223"))
    )
    (comp (ref "C34")
      (value "82pF")
      (fields (field (name "Manufacturer Part") "CC0402JRNPO9BN820") (field (name "Manufacturer") "YAGEO"))
      (libsource (lib "") (part "CC0402JRNPO9BN820"))
    )
    (comp (ref "C35")
      (value "22nF")
      (fields (field (name "Manufacturer Part") "CC0402KRX7R9BB223") (field (name "Manufacturer") "YAGEO"))
      (libsource (lib "") (part "CC0402KRX7R9BB223"))
    )
    (comp (ref "C36")
      (value "100nF")
      (fields (field (name "Manufacturer Part") "CC0402KRX7R8BB104") (field (name "Manufacturer") "YAGEO"))
      (libsource (lib "") (part "CC0402KRX7R8BB104_1"))
    )
    (comp (ref "C37")
      (value "33pF")
      (fields (field (name "Manufacturer Part") "CL05C330JB5NNNC") (field (name "Manufacturer") "SAMSUNG"))
      (libsource (lib "") (part "CL05C330JB5NNNC"))
    )
    (comp (ref "C38")
      (value "100nF")
      (fields (field (name "Manufacturer Part") "CC0402KRX7R8BB104") (field (name "Manufacturer") "YAGEO"))
      (libsource (lib "") (part "CC0402KRX7R8BB104"))
    )
    (comp (ref "C39")
      (value "27pF")
      (fields (field (name "Manufacturer Part") "GCM1555C1H270JA16D") (field (name "Manufacturer") "MuRata"))
      (libsource (lib "") (part "GCM1555C1H270JA16D"))
    )
    (comp (ref "C40")
      (value "100nF")
      (fields (field (name "Manufacturer Part") "CC0402KRX7R8BB104") (field (name "Manufacturer") "YAGEO"))
      (libsource (lib "") (part "CC0402KRX7R8BB104_1"))
    )
    (comp (ref "C41")
      (value "10uF")
      (fields (field (name "Manufacturer Part") "CL10A106MA8NRNC") (field (name "Manufacturer") "SAMSUNG"))
      (libsource (lib "") (part "CL10A106MA8NRNC"))
    )
    (comp (ref "C42")
      (value "10uF")
      (fields (field (name "Manufacturer Part") "CL10A106MA8NRNC") (field (name "Manufacturer") "SAMSUNG"))
      (libsource (lib "") (part "CL10A106MA8NRNC_2"))
    )
    (comp (ref "C43")
      (value "10uF")
      (fields (field (name "Manufacturer Part") "CL10A106MA8NRNC") (field (name "Manufacturer") "SAMSUNG"))
      (libsource (lib "") (part "CL10A106MA8NRNC_1"))
    )
    (comp (ref "C55")
      (value "1uF")
      (fields (field (name "Manufacturer Part") "CL05A105KA5NQNC") (field (name "Manufacturer") "SAMSUNG"))
      (libsource (lib "") (part "CL05A105KA5NQNC"))
    )
    (comp (ref "C56")
      (value "1uF")
      (fields (field (name "Manufacturer Part") "CL05A105KA5NQNC") (field (name "Manufacturer") "SAMSUNG"))
      (libsource (lib "") (part "CL05A105KA5NQNC"))
    )
    (comp (ref "C63")
      (value "10uF")
      (fields (field (name "Manufacturer Part") "TAJA106K010RNJ") (field (name "Manufacturer") "AVX"))
      (libsource (lib "") (part "TAJA106K010RNJ"))
    )
    (comp (ref "C82")
      (value "10uF")
      (fields (field (name "Manufacturer Part") "CL10A106MA8NRNC") (field (name "Manufacturer") "SAMSUNG"))
      (libsource (lib "") (part "CL10A106MA8NRNC"))
    )
    (comp (ref "C85")
      (value "10uF")
      (fields (field (name "Manufacturer Part") "CL10A106MA8NRNC") (field (name "Manufacturer") "SAMSUNG"))
      (libsource (lib "") (part "CL10A106MA8NRNC"))
    )
    (comp (ref "CONTROL3")
      (value "FH34SRJ-12S-0.5SH(50)")
      (fields (field (name "Manufacturer") "Hirose"))
      (libsource (lib "") (part "FH34SRJ-12S-0.5SH(50)"))
    )
    (comp (ref "D1")
      (value "LMBR140ET1G")
      (fields (field (name "Manufacturer") "Leshan Radio"))
      (libsource (lib "") (part "LMBR140ET1G"))
    )
    (comp (ref "D2")
      (value "LMBR140ET1G")
      (fields (field (name "Manufacturer") "Leshan Radio"))
      (libsource (lib "") (part "LMBR140ET1G"))
    )
    (comp (ref "D3")
      (value "BAV99_C171788")
      (fields
        (field (name "Manufacturer Part") "BAV99")
        (field (name "Manufacturer") "Sangdest Microelectronicstronic (Nanjing)")
      )
      (libsource (lib "") (part "BAV99_C171788"))
    )
    (comp (ref "D4")
      (value "BAV99_C171788")
      (fields
        (field (name "Manufacturer Part") "BAV99")
        (field (name "Manufacturer") "Sangdest Microelectronicstronic (Nanjing)")
      )
      (libsource (lib "") (part "BAV99_C171788"))
    )
    (comp (ref "FPC1")
      (value "X05A20H50G")
      (fields (field (name "Manufacturer") "XKB Enterprise"))
      (libsource (lib "") (part "X05A20H50G"))
    )
    (comp (ref "FPC2")
      (value "FH34SRJ-14S-0.5SH(50)")
      (fields (field (name "Manufacturer") "Hirose"))
      (libsource (lib "") (part "FH34SRJ-14S-0.5SH(50)"))
    )
    (comp (ref "FPC6")
      (value "AFC24-S40FIA-00")
      (fields (field (name "Manufacturer") "JUSHUO"))
      (libsource (lib "") (part "AFC24-S40FIA-00"))
    )
    (comp (ref "G") (value "TP1") (libsource (lib "") (part "TP1_13")))
    (comp (ref "GND") (value "TP1") (libsource (lib "") (part "TP1_4")))
    (comp (ref "HDMI1")
      (value "AFC42-S20FMA-1H")
      (fields (field (name "Manufacturer") "JUSHUO"))
      (libsource (lib "") (part "AFC42-S20FMA-1H"))
    )
    (comp (ref "HS") (value "MINI JUMPER") (libsource (lib "") (part "MINI JUMPER_1")))
    (comp (ref "HS1") (value "TP1") (libsource (lib "") (part "TP1_5")))
    (comp (ref "IC1") (value "RTD2660H") (libsource (lib "") (part "RTD2660H")))
    (comp (ref "IR") (value "TP1") (libsource (lib "") (part "TP1_2")))
    (comp (ref "IR-V") (value "TP1") (libsource (lib "") (part "TP1_14")))
    (comp (ref "J1") (value "TP1 MINI") (libsource (lib "") (part "TP1 MINI")))
    (comp (ref "J2") (value "TP1 MINI") (libsource (lib "") (part "TP1 MINI")))
    (comp (ref "J3") (value "TP1 MINI") (libsource (lib "") (part "TP1 MINI")))
    (comp (ref "J4") (value "TP1 MINI") (libsource (lib "") (part "TP1 MINI")))
    (comp (ref "J5") (value "TP1 MINI") (libsource (lib "") (part "TP1 MINI")))
    (comp (ref "J6") (value "TP1 MINI") (libsource (lib "") (part "TP1 MINI")))
    (comp (ref "J7") (value "TP1 MINI") (libsource (lib "") (part "TP1 MINI_1")))
    (comp (ref "J8") (value "TP1 MINI") (libsource (lib "") (part "TP1 MINI_1")))
    (comp (ref "J9") (value "TP1 MINI") (libsource (lib "") (part "TP1 MINI_1")))
    (comp (ref "J10") (value "TP1 MINI") (libsource (lib "") (part "TP1 MINI_1")))
    (comp (ref "J11") (value "TP1 MINI") (libsource (lib "") (part "TP1 MINI_1")))
    (comp (ref "J12") (value "TP1 MINI") (libsource (lib "") (part "TP1 MINI_1")))
    (comp (ref "J15") (value "MINI JUMPER") (libsource (lib "") (part "MINI JUMPER")))
    (comp (ref "L1.")
      (value "0Ω")
      (fields (field (name "Manufacturer Part") "CBG100505U000T") (field (name "Manufacturer") "FH"))
      (libsource (lib "") (part "CBG100505U000T_2"))
    )
    (comp (ref "L2.")
      (value "0Ω")
      (fields (field (name "Manufacturer Part") "CBG100505U000T") (field (name "Manufacturer") "FH"))
      (libsource (lib "") (part "CBG100505U000T_1"))
    )
    (comp (ref "L3.")
      (value "0Ω")
      (fields (field (name "Manufacturer Part") "CBG100505U000T") (field (name "Manufacturer") "FH"))
      (libsource (lib "") (part "CBG100505U000T_3"))
    )
    (comp (ref "L4")
      (value "0Ω")
      (fields (field (name "Manufacturer Part") "CBG100505U000T") (field (name "Manufacturer") "FH"))
      (libsource (lib "") (part "CBG100505U000T"))
    )
    (comp (ref "L9")
      (value "0Ω")
      (fields (field (name "Manufacturer Part") "CBG100505U000T") (field (name "Manufacturer") "FH"))
      (libsource (lib "") (part "CBG100505U000T"))
    )
    (comp (ref "L10")
      (value "0Ω")
      (fields (field (name "Manufacturer Part") "CBW160808U000T") (field (name "Manufacturer") "FH"))
      (libsource (lib "") (part "CBW160808U000T"))
    )
    (comp (ref "L11")
      (value "0Ω")
      (fields (field (name "Manufacturer Part") "CBW160808U000T") (field (name "Manufacturer") "FH"))
      (libsource (lib "") (part "CBW160808U000T"))
    )
    (comp (ref "L12")
      (value "0Ω")
      (fields (field (name "Manufacturer Part") "CBW160808U000T") (field (name "Manufacturer") "FH"))
      (libsource (lib "") (part "CBW160808U000T_1"))
    )
    (comp (ref "L14")
      (value "0Ω")
      (fields (field (name "Manufacturer Part") "CBW160808U000T") (field (name "Manufacturer") "FH"))
      (libsource (lib "") (part "CBW160808U000T_2"))
    )
    (comp (ref "L22")
      (value "Taiyo Yuden NRS4018T220MDGJV")
      (fields
        (field (name "Manufacturer Part") "NRS4018T220MDGJV")
        (field (name "Manufacturer") "Taiyo Yuden")
      )
      (libsource (lib "") (part "Taiyo Yuden NRS4018T220MDGJV"))
    )
    (comp (ref "LG") (value "TP1") (libsource (lib "") (part "TP1_10")))
    (comp (ref "LR") (value "TP1") (libsource (lib "") (part "TP1_8")))
    (comp (ref "MN") (value "TP1") (libsource (lib "") (part "TP1_17")))
    (comp (ref "O1") (value "MOUNTINGHOLE_2.2MM") (libsource (lib "") (part "MOUNTINGHOLE_2.2MM")))
    (comp (ref "O2") (value "MOUNTINGHOLE_2.2MM") (libsource (lib "") (part "MOUNTINGHOLE_2.2MM")))
    (comp (ref "O3") (value "MOUNTINGHOLE_2.2MM") (libsource (lib "") (part "MOUNTINGHOLE_2.2MM")))
    (comp (ref "O4") (value "MOUNTINGHOLE_2.2MM") (libsource (lib "") (part "MOUNTINGHOLE_2.2MM")))
    (comp (ref "PS2")
      (value "FH34SRJ-30S-0.5SH(50)")
      (fields (field (name "Manufacturer") "Hirose"))
      (libsource (lib "") (part "FH34SRJ-30S-0.5SH(50)"))
    )
    (comp (ref "PW") (value "TP1") (libsource (lib "") (part "TP1_9")))
    (comp (ref "Q1")
      (value "MMBT3904-1AM")
      (fields (field (name "Manufacturer") "(MDD) Jiangsu Yutai Elec"))
      (libsource (lib "") (part "MMBT3904-1AM"))
    )
    (comp (ref "Q2")
      (value "SI9435DY-T1")
      (fields (field (name "Manufacturer") "VBsemi Elec"))
      (libsource (lib "") (part "SI9435DY-T1"))
    )
    (comp (ref "Q3")
      (value "MMBT3904-1AM")
      (fields (field (name "Manufacturer") "(MDD) Jiangsu Yutai Elec"))
      (libsource (lib "") (part "MMBT3904-1AM"))
    )
    (comp (ref "Q5")
      (value "MMBT3904-1AM")
      (fields (field (name "Manufacturer") "(MDD) Jiangsu Yutai Elec"))
      (libsource (lib "") (part "MMBT3904-1AM_1"))
    )
    (comp (ref "R") (value "TP1") (libsource (lib "") (part "TP1")))
    (comp (ref "R1.")
      (value "75")
      (fields (field (name "Manufacturer Part") "RC0402JR-0775RL") (field (name "Manufacturer") "YAGEO"))
      (libsource (lib "") (part "RC0402JR-0775RL"))
    )
    (comp (ref "R2.")
      (value "100")
      (fields (field (name "Manufacturer Part") "ERJPA2J101X") (field (name "Manufacturer") "PANASONIC"))
      (libsource (lib "") (part "ERJPA2J101X_2"))
    )
    (comp (ref "R3.")
      (value "100")
      (fields (field (name "Manufacturer Part") "ERJPA2J101X") (field (name "Manufacturer") "PANASONIC"))
      (libsource (lib "") (part "ERJPA2J101X_3"))
    )
    (comp (ref "R4")
      (value "0")
      (fields (field (name "Manufacturer Part") "RC0402FR-070RL") (field (name "Manufacturer") "YAGEO"))
      (libsource (lib "") (part "RC0402FR-070RL"))
    )
    (comp (ref "R5")
      (value "100")
      (fields (field (name "Manufacturer Part") "ERJPA2J101X") (field (name "Manufacturer") "PANASONIC"))
      (libsource (lib "") (part "ERJPA2J101X"))
    )
    (comp (ref "R6")
      (value "75")
      (fields (field (name "Manufacturer Part") "RC0402JR-0775RL") (field (name "Manufacturer") "YAGEO"))
      (libsource (lib "") (part "RC0402JR-0775RL_1"))
    )
    (comp (ref "R7")
      (value "100")
      (fields (field (name "Manufacturer Part") "ERJPA2J101X") (field (name "Manufacturer") "PANASONIC"))
      (libsource (lib "") (part "ERJPA2J101X"))
    )
    (comp (ref "R8")
      (value "100")
      (fields (field (name "Manufacturer Part") "ERJPA2J101X") (field (name "Manufacturer") "PANASONIC"))
      (libsource (lib "") (part "ERJPA2J101X"))
    )
    (comp (ref "R9")
      (value "1K")
      (fields (field (name "Manufacturer Part") "AC0402FR-071KL") (field (name "Manufacturer") "YAGEO"))
      (libsource (lib "") (part "AC0402FR-071KL"))
    )
    (comp (ref "R10")
      (value "4.7K")
      (fields (field (name "Manufacturer Part") "ERJPA2F4701X") (field (name "Manufacturer") "PANASONIC"))
      (libsource (lib "") (part "ERJPA2F4701X"))
    )
    (comp (ref "R11")
      (value "33")
      (fields (field (name "Manufacturer Part") "ERJ2RKF33R0X") (field (name "Manufacturer") "PANASONIC"))
      (libsource (lib "") (part "ERJ2RKF33R0X"))
    )
    (comp (ref "R12")
      (value "33")
      (fields (field (name "Manufacturer Part") "ERJ2RKF33R0X") (field (name "Manufacturer") "PANASONIC"))
      (libsource (lib "") (part "ERJ2RKF33R0X"))
    )
    (comp (ref "R13")
      (value "33")
      (fields (field (name "Manufacturer Part") "ERJ2RKF33R0X") (field (name "Manufacturer") "PANASONIC"))
      (libsource (lib "") (part "ERJ2RKF33R0X"))
    )
    (comp (ref "R14")
      (value "33")
      (fields (field (name "Manufacturer Part") "ERJ2RKF33R0X") (field (name "Manufacturer") "PANASONIC"))
      (libsource (lib "") (part "ERJ2RKF33R0X"))
    )
    (comp (ref "R15")
      (value "4.7K")
      (fields (field (name "Manufacturer Part") "ERJPA2F4701X") (field (name "Manufacturer") "PANASONIC"))
      (libsource (lib "") (part "ERJPA2F4701X_3"))
    )
    (comp (ref "R16")
      (value "1K")
      (fields (field (name "Manufacturer Part") "AC0402FR-071KL") (field (name "Manufacturer") "YAGEO"))
      (libsource (lib "") (part "AC0402FR-071KL"))
    )
    (comp (ref "R17")
      (value "100")
      (fields (field (name "Manufacturer Part") "ERJPA2J101X") (field (name "Manufacturer") "PANASONIC"))
      (libsource (lib "") (part "ERJPA2J101X"))
    )
    (comp (ref "R18")
      (value "4.7K")
      (fields (field (name "Manufacturer Part") "ERJPA2F4701X") (field (name "Manufacturer") "PANASONIC"))
      (libsource (lib "") (part "ERJPA2F4701X_1"))
    )
    (comp (ref "R19")
      (value "100")
      (fields (field (name "Manufacturer Part") "ERJPA2J101X") (field (name "Manufacturer") "PANASONIC"))
      (libsource (lib "") (part "ERJPA2J101X"))
    )
    (comp (ref "R20")
      (value "4.7K")
      (fields (field (name "Manufacturer Part") "ERJPA2F4701X") (field (name "Manufacturer") "PANASONIC"))
      (libsource (lib "") (part "ERJPA2F4701X_1"))
    )
    (comp (ref "R21")
      (value "33")
      (fields (field (name "Manufacturer Part") "ERJ2RKF33R0X") (field (name "Manufacturer") "PANASONIC"))
      (libsource (lib "") (part "ERJ2RKF33R0X"))
    )
    (comp (ref "R22")
      (value "33")
      (fields (field (name "Manufacturer Part") "ERJ2RKF33R0X") (field (name "Manufacturer") "PANASONIC"))
      (libsource (lib "") (part "ERJ2RKF33R0X"))
    )
    (comp (ref "R23")
      (value "33")
      (fields (field (name "Manufacturer Part") "ERJ2RKF33R0X") (field (name "Manufacturer") "PANASONIC"))
      (libsource (lib "") (part "ERJ2RKF33R0X"))
    )
    (comp (ref "R24")
      (value "33")
      (fields (field (name "Manufacturer Part") "ERJ2RKF33R0X") (field (name "Manufacturer") "PANASONIC"))
      (libsource (lib "") (part "ERJ2RKF33R0X"))
    )
    (comp (ref "R25")
      (value "1K")
      (fields (field (name "Manufacturer Part") "AC0402FR-071KL") (field (name "Manufacturer") "YAGEO"))
      (libsource (lib "") (part "AC0402FR-071KL"))
    )
    (comp (ref "R26")
      (value "1K")
      (fields (field (name "Manufacturer Part") "AC0402FR-071KL") (field (name "Manufacturer") "YAGEO"))
      (libsource (lib "") (part "AC0402FR-071KL"))
    )
    (comp (ref "R27")
      (value "0")
      (fields (field (name "Manufacturer Part") "RC0402FR-070RL") (field (name "Manufacturer") "YAGEO"))
      (libsource (lib "") (part "RC0402FR-070RL_1"))
    )
    (comp (ref "R28")
      (value "4.7K")
      (fields (field (name "Manufacturer Part") "ERJPA2F4701X") (field (name "Manufacturer") "PANASONIC"))
      (libsource (lib "") (part "ERJPA2F4701X"))
    )
    (comp (ref "R29")
      (value "4.7K")
      (fields (field (name "Manufacturer Part") "ERJPA2F4701X") (field (name "Manufacturer") "PANASONIC"))
      (libsource (lib "") (part "ERJPA2F4701X"))
    )
    (comp (ref "R30")
      (value "4.7K")
      (fields (field (name "Manufacturer Part") "ERJPA2F4701X") (field (name "Manufacturer") "PANASONIC"))
      (libsource (lib "") (part "ERJPA2F4701X"))
    )
    (comp (ref "R31")
      (value "4.7K")
      (fields (field (name "Manufacturer Part") "ERJPA2F4701X") (field (name "Manufacturer") "PANASONIC"))
      (libsource (lib "") (part "ERJPA2F4701X"))
    )
    (comp (ref "R32")
      (value "4.7K")
      (fields (field (name "Manufacturer Part") "ERJPA2F4701X") (field (name "Manufacturer") "PANASONIC"))
      (libsource (lib "") (part "ERJPA2F4701X"))
    )
    (comp (ref "R33")
      (value "ERJPA3J1R0V")
      (fields (field (name "Manufacturer") "PANASONIC"))
      (libsource (lib "") (part "ERJPA3J1R0V"))
    )
    (comp (ref "R34")
      (value "2K")
      (fields (field (name "Manufacturer Part") "RC0402FR-072KL") (field (name "Manufacturer") "YAGEO"))
      (libsource (lib "") (part "RC0402FR-072KL"))
    )
    (comp (ref "R35")
      (value "3.9K")
      (fields (field (name "Manufacturer Part") "ERJ2RKF3901X") (field (name "Manufacturer") "PANASONIC"))
      (libsource (lib "") (part "ERJ2RKF3901X"))
    )
    (comp (ref "R36")
      (value "10K")
      (fields (field (name "Manufacturer Part") "ERJPA2F1002X") (field (name "Manufacturer") "PANASONIC"))
      (libsource (lib "") (part "ERJPA2F1002X_1"))
    )
    (comp (ref "R37")
      (value "100")
      (fields (field (name "Manufacturer Part") "ERJPA2J101X") (field (name "Manufacturer") "PANASONIC"))
      (libsource (lib "") (part "ERJPA2J101X_1"))
    )
    (comp (ref "R38")
      (value "10K")
      (fields (field (name "Manufacturer Part") "ERJPA2F1002X") (field (name "Manufacturer") "PANASONIC"))
      (libsource (lib "") (part "ERJPA2F1002X_1"))
    )
    (comp (ref "R39")
      (value "10K")
      (fields (field (name "Manufacturer Part") "ERJPA2F1002X") (field (name "Manufacturer") "PANASONIC"))
      (libsource (lib "") (part "ERJPA2F1002X_1"))
    )
    (comp (ref "R40")
      (value "100K")
      (fields (field (name "Manufacturer Part") "RC0402FR-07100KL") (field (name "Manufacturer") "YAGEO"))
      (libsource (lib "") (part "RC0402FR-07100KL"))
    )
    (comp (ref "R41")
      (value "4.7K")
      (fields (field (name "Manufacturer Part") "ERJPA2F4701X") (field (name "Manufacturer") "PANASONIC"))
      (libsource (lib "") (part "ERJPA2F4701X_3"))
    )
    (comp (ref "R42")
      (value "0")
      (fields (field (name "Manufacturer Part") "RC0402FR-070RL") (field (name "Manufacturer") "YAGEO"))
      (libsource (lib "") (part "RC0402FR-070RL_1"))
    )
    (comp (ref "R43")
      (value "100K")
      (fields (field (name "Manufacturer Part") "ERJPA2J104X") (field (name "Manufacturer") "PANASONIC"))
      (libsource (lib "") (part "ERJPA2J104X"))
    )
    (comp (ref "R44")
      (value "100K")
      (fields (field (name "Manufacturer Part") "ERJPA2J104X") (field (name "Manufacturer") "PANASONIC"))
      (libsource (lib "") (part "ERJPA2J104X"))
    )
    (comp (ref "R45")
      (value "75")
      (fields (field (name "Manufacturer Part") "ERJ2RKF75R0X") (field (name "Manufacturer") "PANASONIC"))
      (libsource (lib "") (part "ERJ2RKF75R0X"))
    )
    (comp (ref "R46")
      (value "330")
      (fields (field (name "Manufacturer Part") "0402WGF3300TCE") (field (name "Manufacturer") "UniOhm"))
      (libsource (lib "") (part "0402WGF3300TCE"))
    )
    (comp (ref "R47")
      (value "10K")
      (fields (field (name "Manufacturer Part") "ERJPA2F1002X") (field (name "Manufacturer") "PANASONIC"))
      (libsource (lib "") (part "ERJPA2F1002X"))
    )
    (comp (ref "R48")
      (value "20K")
      (fields (field (name "Manufacturer Part") "RC0402JR-0720KL") (field (name "Manufacturer") "YAGEO"))
      (libsource (lib "") (part "RC0402JR-0720KL"))
    )
    (comp (ref "R49")
      (value "33")
      (fields (field (name "Manufacturer Part") "ERJ2RKF33R0X") (field (name "Manufacturer") "PANASONIC"))
      (libsource (lib "") (part "ERJ2RKF33R0X"))
    )
    (comp (ref "R50")
      (value "33")
      (fields (field (name "Manufacturer Part") "ERJ2RKF33R0X") (field (name "Manufacturer") "PANASONIC"))
      (libsource (lib "") (part "ERJ2RKF33R0X"))
    )
    (comp (ref "R51")
      (value "4.7K")
      (fields (field (name "Manufacturer Part") "ERJPA2F4701X") (field (name "Manufacturer") "PANASONIC"))
      (libsource (lib "") (part "ERJPA2F4701X"))
    )
    (comp (ref "R52")
      (value "1M")
      (fields (field (name "Manufacturer Part") "ERJPA2J105X") (field (name "Manufacturer") "PANASONIC"))
      (libsource (lib "") (part "ERJPA2J105X"))
    )
    (comp (ref "R53")
      (value "4.7K")
      (fields (field (name "Manufacturer Part") "ERJPA2F4701X") (field (name "Manufacturer") "PANASONIC"))
      (libsource (lib "") (part "ERJPA2F4701X"))
    )
    (comp (ref "R54")
      (value "4.7K")
      (fields (field (name "Manufacturer Part") "ERJPA2F4701X") (field (name "Manufacturer") "PANASONIC"))
      (libsource (lib "") (part "ERJPA2F4701X_2"))
    )
    (comp (ref "R55")
      (value "100")
      (fields (field (name "Manufacturer Part") "ERJPA2J101X") (field (name "Manufacturer") "PANASONIC"))
      (libsource (lib "") (part "ERJPA2J101X"))
    )
    (comp (ref "R56")
      (value "10K")
      (fields (field (name "Manufacturer Part") "ERJPA2F1002X") (field (name "Manufacturer") "PANASONIC"))
      (libsource (lib "") (part "ERJPA2F1002X"))
    )
    (comp (ref "R57")
      (value "100")
      (fields (field (name "Manufacturer Part") "ERJPA2J101X") (field (name "Manufacturer") "PANASONIC"))
      (libsource (lib "") (part "ERJPA2J101X"))
    )
    (comp (ref "R58")
      (value "10K")
      (fields (field (name "Manufacturer Part") "ERJPA2F1002X") (field (name "Manufacturer") "PANASONIC"))
      (libsource (lib "") (part "ERJPA2F1002X"))
    )
    (comp (ref "R59")
      (value "100")
      (fields (field (name "Manufacturer Part") "ERJPA2J101X") (field (name "Manufacturer") "PANASONIC"))
      (libsource (lib "") (part "ERJPA2J101X"))
    )
    (comp (ref "R60")
      (value "75")
      (fields (field (name "Manufacturer Part") "RC0402JR-0775RL") (field (name "Manufacturer") "YAGEO"))
      (libsource (lib "") (part "RC0402JR-0775RL_1"))
    )
    (comp (ref "R64")
      (value "4.7K")
      (fields (field (name "Manufacturer Part") "ERJPA2F4701X") (field (name "Manufacturer") "PANASONIC"))
      (libsource (lib "") (part "ERJPA2F4701X_3"))
    )
    (comp (ref "R71")
      (value "4.7K")
      (fields (field (name "Manufacturer Part") "ERJPA2F4701X") (field (name "Manufacturer") "PANASONIC"))
      (libsource (lib "") (part "ERJPA2F4701X"))
    )
    (comp (ref "R72")
      (value "4.7K")
      (fields (field (name "Manufacturer Part") "ERJPA2F4701X") (field (name "Manufacturer") "PANASONIC"))
      (libsource (lib "") (part "ERJPA2F4701X_2"))
    )
    (comp (ref "R77")
      (value "4.7K")
      (fields (field (name "Manufacturer Part") "ERJPA2F4701X") (field (name "Manufacturer") "PANASONIC"))
      (libsource (lib "") (part "ERJPA2F4701X_1"))
    )
    (comp (ref "R78")
      (value "100")
      (fields (field (name "Manufacturer Part") "ERJPA2J101X") (field (name "Manufacturer") "PANASONIC"))
      (libsource (lib "") (part "ERJPA2J101X"))
    )
    (comp (ref "R79")
      (value "10K")
      (fields (field (name "Manufacturer Part") "ERJPA2F1002X") (field (name "Manufacturer") "PANASONIC"))
      (libsource (lib "") (part "ERJPA2F1002X"))
    )
    (comp (ref "R82")
      (value "10K")
      (fields (field (name "Manufacturer Part") "ERJPA2F1002X") (field (name "Manufacturer") "PANASONIC"))
      (libsource (lib "") (part "ERJPA2F1002X_1"))
    )
    (comp (ref "R83")
      (value "100")
      (fields (field (name "Manufacturer Part") "ERJPA2J101X") (field (name "Manufacturer") "PANASONIC"))
      (libsource (lib "") (part "ERJPA2J101X_1"))
    )
    (comp (ref "R84")
      (value "100")
      (fields (field (name "Manufacturer Part") "ERJPA2J101X") (field (name "Manufacturer") "PANASONIC"))
      (libsource (lib "") (part "ERJPA2J101X_1"))
    )
    (comp (ref "R85")
      (value "4.7K")
      (fields (field (name "Manufacturer Part") "ERJPA2F4701X") (field (name "Manufacturer") "PANASONIC"))
      (libsource (lib "") (part "ERJPA2F4701X_1"))
    )
    (comp (ref "R86")
      (value "10K")
      (fields (field (name "Manufacturer Part") "ERJPA2F1002X") (field (name "Manufacturer") "PANASONIC"))
      (libsource (lib "") (part "ERJPA2F1002X"))
    )
    (comp (ref "R87")
      (value "10K")
      (fields (field (name "Manufacturer Part") "ERJPA2F1002X") (field (name "Manufacturer") "PANASONIC"))
      (libsource (lib "") (part "ERJPA2F1002X"))
    )
    (comp (ref "R88")
      (value "4.7K")
      (fields (field (name "Manufacturer Part") "ERJPA2F4701X") (field (name "Manufacturer") "PANASONIC"))
      (libsource (lib "") (part "ERJPA2F4701X_3"))
    )
    (comp (ref "R89")
      (value "4.7K")
      (fields (field (name "Manufacturer Part") "ERJPA2F4701X") (field (name "Manufacturer") "PANASONIC"))
      (libsource (lib "") (part "ERJPA2F4701X_3"))
    )
    (comp (ref "R90")
      (value "4.7K")
      (fields (field (name "Manufacturer Part") "ERJPA2F4701X") (field (name "Manufacturer") "PANASONIC"))
      (libsource (lib "") (part "ERJPA2F4701X_3"))
    )
    (comp (ref "SC") (value "TP1") (libsource (lib "") (part "TP1_12")))
    (comp (ref "SCL") (value "TP1") (libsource (lib "") (part "TP1_18")))
    (comp (ref "SDA") (value "TP1") (libsource (lib "") (part "TP1_16")))
    (comp (ref "U1")
      (value "W25X40CLSNIGT")
      (fields (field (name "Manufacturer") "WINBOND"))
      (libsource (lib "") (part "W25X40CLSNIGT"))
    )
    (comp (ref "U2")
      (value "PT4103B23F")
      (fields (field (name "Manufacturer") "PowTech"))
      (libsource (lib "") (part "PT4103B23F"))
    )
    (comp (ref "U3")
      (value "AMS1117-1.8")
      (fields (field (name "Manufacturer") "AMS"))
      (libsource (lib "") (part "AMS1117-1.8"))
    )
    (comp (ref "U4")
      (value "AMS1117-3.3")
      (fields (field (name "Manufacturer") "AMS"))
      (libsource (lib "") (part "AMS1117-3.3"))
    )
    (comp (ref "U7") (value "MEMORYCARD PS2") (libsource (lib "") (part "MEMORYCARD PS2")))
    (comp (ref "VCC1") (value "VCC") (libsource (lib "") (part "TP1_3")))
    (comp (ref "VS") (value "MINI JUMPER") (libsource (lib "") (part "MINI JUMPER_2")))
    (comp (ref "VS1") (value "TP1") (libsource (lib "") (part "TP1_1")))
    (comp (ref "X1")
      (value "27MHz")
      (fields (field (name "Manufacturer Part") "X322527MSB4SI") (field (name "Manufacturer") "YXC"))
      (libsource (lib "") (part "X322527MSB4SI"))
    )
    (comp (ref "C44")
      (value "220uF")
      (fields (field (name "Manufacturer Part") "TLJB227M006R0500") (field (name "Manufacturer") "AVX"))
      (libsource (lib "") (part "TLJB227M006R0500"))
    )
    (comp (ref "C47")
      (value "220uF")
      (fields (field (name "Manufacturer Part") "TLJB227M006R0500") (field (name "Manufacturer") "AVX"))
      (libsource (lib "") (part "TLJB227M006R0500"))
    )
    (comp (ref "C61")
      (value "100uF")
      (fields
        (field (name "Manufacturer Part") "CA45-A6R3K107T")
        (field (name "Manufacturer") "Hunan Xiangyee in S&T")
      )
      (libsource (lib "") (part "CA45-A6R3K107T"))
    )
    (comp (ref "C71")
      (value "100nF")
      (fields (field (name "Manufacturer Part") "CC0402JRX7R6BB104") (field (name "Manufacturer") "YAGEO"))
      (libsource (lib "") (part "CC0402JRX7R6BB104"))
    )
    (comp (ref "C72")
      (value "100nF")
      (fields (field (name "Manufacturer Part") "CC0402JRX7R6BB104") (field (name "Manufacturer") "YAGEO"))
      (libsource (lib "") (part "CC0402JRX7R6BB104"))
    )
    (comp (ref "C73")
      (value "100nF")
      (fields (field (name "Manufacturer Part") "CC0402JRX7R6BB104") (field (name "Manufacturer") "YAGEO"))
      (libsource (lib "") (part "CC0402JRX7R6BB104"))
    )
    (comp (ref "C74")
      (value "100nF")
      (fields (field (name "Manufacturer Part") "CC0402JRX7R6BB104") (field (name "Manufacturer") "YAGEO"))
      (libsource (lib "") (part "CC0402JRX7R6BB104"))
    )
    (comp (ref "C75")
      (value "100nF")
      (fields (field (name "Manufacturer Part") "CC0402JRX7R6BB104") (field (name "Manufacturer") "YAGEO"))
      (libsource (lib "") (part "CC0402JRX7R6BB104"))
    )
    (comp (ref "C76")
      (value "10uF")
      (fields (field (name "Manufacturer Part") "CL10A106KP8NNNC") (field (name "Manufacturer") "SAMSUNG"))
      (libsource (lib "") (part "CL10A106KP8NNNC"))
    )
    (comp (ref "C77")
      (value "100nF")
      (fields (field (name "Manufacturer Part") "CC0402JRX7R6BB104") (field (name "Manufacturer") "YAGEO"))
      (libsource (lib "") (part "CC0402JRX7R6BB104"))
    )
    (comp (ref "C78")
      (value "2.2uF")
      (fields
        (field (name "Manufacturer Part") "CL05A225KQ5NSNC")
        (field (name "Manufacturer") "Samsung Electro-Mechanics")
      )
      (libsource (lib "") (part "CL05A225KQ5NSNC"))
    )
    (comp (ref "C81")
      (value "1uF")
      (fields (field (name "Manufacturer Part") "CL05A105KA5NQNC") (field (name "Manufacturer") "SAMSUNG"))
      (libsource (lib "") (part "CL05A105KA5NQNC"))
    )
    (comp (ref "C83")
      (value "1uF")
      (fields (field (name "Manufacturer Part") "CL05A105KA5NQNC") (field (name "Manufacturer") "SAMSUNG"))
      (libsource (lib "") (part "CL05A105KA5NQNC"))
    )
    (comp (ref "CN2")
      (value "PJ-320D_C521460")
      (fields (field (name "Manufacturer Part") "PJ-320D") (field (name "Manufacturer") "USAKRO"))
      (libsource (lib "") (part "PJ-320D_C521460"))
    )
    (comp (ref "L+") (value "TP1 MINI") (libsource (lib "") (part "TP1 MINI")))
    (comp (ref "L-") (value "TP1 MINI") (libsource (lib "") (part "TP1 MINI_3")))
    (comp (ref "L-IN1") (value "TP1 MINI") (libsource (lib "") (part "TP1 MINI_5")))
    (comp (ref "L80")
      (value "0Ω")
      (fields (field (name "Manufacturer Part") "CBG100505U000T") (field (name "Manufacturer") "FH"))
      (libsource (lib "") (part "CBG100505U000T"))
    )
    (comp (ref "L90")
      (value "0Ω")
      (fields (field (name "Manufacturer Part") "CBG100505U000T") (field (name "Manufacturer") "FH"))
      (libsource (lib "") (part "CBG100505U000T"))
    )
    (comp (ref "L100")
      (value "0Ω")
      (fields (field (name "Manufacturer Part") "CBG100505U000T") (field (name "Manufacturer") "FH"))
      (libsource (lib "") (part "CBG100505U000T"))
    )
    (comp (ref "L110")
      (value "0Ω")
      (fields (field (name "Manufacturer Part") "CBG100505U000T") (field (name "Manufacturer") "FH"))
      (libsource (lib "") (part "CBG100505U000T"))
    )
    (comp (ref "Q6")
      (value "MMBT3904-1AM")
      (fields (field (name "Manufacturer") "(MDD) Jiangsu Yutai Elec"))
      (libsource (lib "") (part "MMBT3904-1AM"))
    )
    (comp (ref "R+") (value "TP1 MINI") (libsource (lib "") (part "TP1 MINI_4")))
    (comp (ref "R-") (value "TP1 MINI") (libsource (lib "") (part "TP1 MINI_1")))
    (comp (ref "R-IN1") (value "TP1 MINI") (libsource (lib "") (part "TP1 MINI_2")))
    (comp (ref "R73")
      (value "1K")
      (fields (field (name "Manufacturer Part") "AC0402FR-071KL") (field (name "Manufacturer") "YAGEO"))
      (libsource (lib "") (part "AC0402FR-071KL"))
    )
    (comp (ref "R94")
      (value "100K")
      (fields (field (name "Manufacturer Part") "RC0402FR-07100KL") (field (name "Manufacturer") "YAGEO"))
      (libsource (lib "") (part "RC0402FR-07100KL_1"))
    )
    (comp (ref "R95")
      (value "100K")
      (fields (field (name "Manufacturer Part") "RC0402FR-07100KL") (field (name "Manufacturer") "YAGEO"))
      (libsource (lib "") (part "RC0402FR-07100KL"))
    )
    (comp (ref "R98")
      (value "10K")
      (fields (field (name "Manufacturer Part") "ERJPA2F1002X") (field (name "Manufacturer") "PANASONIC"))
      (libsource (lib "") (part "ERJPA2F1002X"))
    )
    (comp (ref "R101")
      (value "100K")
      (fields (field (name "Manufacturer Part") "RC0402FR-07100KL") (field (name "Manufacturer") "YAGEO"))
      (libsource (lib "") (part "RC0402FR-07100KL"))
    )
    (comp (ref "R122")
      (value "1K")
      (fields (field (name "Manufacturer Part") "AC0402FR-071KL") (field (name "Manufacturer") "YAGEO"))
      (libsource (lib "") (part "AC0402FR-071KL"))
    )
    (comp (ref "R236")
      (value "1K")
      (fields (field (name "Manufacturer Part") "AC0402FR-071KL") (field (name "Manufacturer") "YAGEO"))
      (libsource (lib "") (part "AC0402FR-071KL"))
    )
    (comp (ref "R364")
      (value "1K")
      (fields (field (name "Manufacturer Part") "AC0402FR-071KL") (field (name "Manufacturer") "YAGEO"))
      (libsource (lib "") (part "AC0402FR-071KL_1"))
    )
    (comp (ref "U9")
      (value "APA2068KAI-TRG")
      (fields (field (name "Manufacturer") "ANPEC"))
      (libsource (lib "") (part "APA2068KAI-TRG"))
    )
    (comp (ref "3.5V") (value "TP1 MINI") (libsource (lib "") (part "TP1 MINI_17")))
    (comp (ref "3V") (value "TP1") (libsource (lib "") (part "TP1_5")))
    (comp (ref "3V3") (value "TP1 MINI") (libsource (lib "") (part "TP1 MINI")))
    (comp (ref "3V3,") (value "TP1") (libsource (lib "") (part "TP1")))
    (comp (ref "3V3/") (value "TP1") (libsource (lib "") (part "TP1_6")))
    (comp (ref "8.5V") (value "TP1 MINI") (libsource (lib "") (part "TP1 MINI_14")))
    (comp (ref "ACK1") (value "TP1 MINI") (libsource (lib "") (part "TP1 MINI_19")))
    (comp (ref "ATT1") (value "TP1 MINI") (libsource (lib "") (part "TP1 MINI_4")))
    (comp (ref "C51") (value "TP1 MINI") (libsource (lib "") (part "TP1 MINI_20")))
    (comp (ref "C52")
      (value "4.7uF")
      (fields
        (field (name "Manufacturer Part") "CL05A475KP5NRNC")
        (field (name "Manufacturer") "Samsung Electro-Mechanics")
      )
      (libsource (lib "") (part "CL05A475KP5NRNC"))
    )
    (comp (ref "C54")
      (value "4.7uF")
      (fields
        (field (name "Manufacturer Part") "CL05A475KP5NRNC")
        (field (name "Manufacturer") "Samsung Electro-Mechanics")
      )
      (libsource (lib "") (part "CL05A475KP5NRNC"))
    )
    (comp (ref "C59")
      (value "100nF")
      (fields (field (name "Manufacturer Part") "CL05B104KO5NNNC") (field (name "Manufacturer") "SAMSUNG"))
      (libsource (lib "") (part "CL05B104KO5NNNC"))
    )
    (comp (ref "C60")
      (value "100nF")
      (fields (field (name "Manufacturer Part") "CL05B104KO5NNNC") (field (name "Manufacturer") "SAMSUNG"))
      (libsource (lib "") (part "CL05B104KO5NNNC"))
    )
    (comp (ref "C62")
      (value "1uF")
      (fields (field (name "Manufacturer Part") "CL05A105KO5NNNC") (field (name "Manufacturer") "SAMSUNG"))
      (libsource (lib "") (part "CL05A105KO5NNNC"))
    )
    (comp (ref "C64")
      (value "2.2uF")
      (fields (field (name "Manufacturer Part") "CL05A225MQ5NSNC") (field (name "Manufacturer") "SAMSUNG"))
      (libsource (lib "") (part "CL05A225MQ5NSNC"))
    )
    (comp (ref "C65")
      (value "2.2uF")
      (fields (field (name "Manufacturer Part") "CL05A225MQ5NSNC") (field (name "Manufacturer") "SAMSUNG"))
      (libsource (lib "") (part "CL05A225MQ5NSNC"))
    )
    (comp (ref "C66")
      (value "100nF")
      (fields (field (name "Manufacturer Part") "CL05B104KO5NNNC") (field (name "Manufacturer") "SAMSUNG"))
      (libsource (lib "") (part "CL05B104KO5NNNC"))
    )
    (comp (ref "C67")
      (value "30pF")
      (fields
        (field (name "Manufacturer Part") "CC0402JRNPO9BN300")
        (field (name "Manufacturer") "YAGEO(国巨)")
      )
      (libsource (lib "") (part "CC0402JRNPO9BN300"))
    )
    (comp (ref "C68")
      (value "30pF")
      (fields
        (field (name "Manufacturer Part") "CC0402JRNPO9BN300")
        (field (name "Manufacturer") "YAGEO(国巨)")
      )
      (libsource (lib "") (part "CC0402JRNPO9BN300"))
    )
    (comp (ref "C69")
      (value "100nF")
      (fields (field (name "Manufacturer Part") "CL05B104KO5NNNC") (field (name "Manufacturer") "SAMSUNG"))
      (libsource (lib "") (part "CL05B104KO5NNNC"))
    )
    (comp (ref "C70")
      (value "100nF")
      (fields (field (name "Manufacturer Part") "CL05B104KO5NNNC") (field (name "Manufacturer") "SAMSUNG"))
      (libsource (lib "") (part "CL05B104KO5NNNC"))
    )
    (comp (ref "C79")
      (value "100nF")
      (fields (field (name "Manufacturer Part") "CL05B104KO5NNNC") (field (name "Manufacturer") "SAMSUNG"))
      (libsource (lib "") (part "CL05B104KO5NNNC"))
    )
    (comp (ref "C80")
      (value "100nF")
      (fields (field (name "Manufacturer Part") "CL05B104KO5NNNC") (field (name "Manufacturer") "SAMSUNG"))
      (libsource (lib "") (part "CL05B104KO5NNNC"))
    )
    (comp (ref "C84")
      (value "100nF")
      (fields (field (name "Manufacturer Part") "CL05B104KO5NNNC") (field (name "Manufacturer") "SAMSUNG"))
      (libsource (lib "") (part "CL05B104KO5NNNC"))
    )
    (comp (ref "C86")
      (value "100nF")
      (fields (field (name "Manufacturer Part") "CL05B104KO5NNNC") (field (name "Manufacturer") "SAMSUNG"))
      (libsource (lib "") (part "CL05B104KO5NNNC"))
    )
    (comp (ref "C87")
      (value "1uF")
      (fields (field (name "Manufacturer Part") "CL05A105KO5NNNC") (field (name "Manufacturer") "SAMSUNG"))
      (libsource (lib "") (part "CL05A105KO5NNNC"))
    )
    (comp (ref "C88")
      (value "100nF")
      (fields (field (name "Manufacturer Part") "CL05B104KO5NNNC") (field (name "Manufacturer") "SAMSUNG"))
      (libsource (lib "") (part "CL05B104KO5NNNC"))
    )
    (comp (ref "C89")
      (value "100nF")
      (fields (field (name "Manufacturer Part") "CL05B104KO5NNNC") (field (name "Manufacturer") "SAMSUNG"))
      (libsource (lib "") (part "CL05B104KO5NNNC"))
    )
    (comp (ref "C90")
      (value "1uF")
      (fields (field (name "Manufacturer Part") "CL05A105KO5NNNC") (field (name "Manufacturer") "SAMSUNG"))
      (libsource (lib "") (part "CL05A105KO5NNNC"))
    )
    (comp (ref "C95")
      (value "2.2uF")
      (fields (field (name "Manufacturer Part") "CL05A225MQ5NSNC") (field (name "Manufacturer") "SAMSUNG"))
      (libsource (lib "") (part "CL05A225MQ5NSNC"))
    )
    (comp (ref "CARD1")
      (value "TF-01A_C2889258")
      (fields (field (name "Manufacturer Part") "TF-01A") (field (name "Manufacturer") "Yuandi(台湾元迪)"))
      (libsource (lib "") (part "TF-01A_C2889258"))
    )
    (comp (ref "CLK1") (value "TP1 MINI") (libsource (lib "") (part "TP1 MINI_9")))
    (comp (ref "CMD1") (value "TP1 MINI") (libsource (lib "") (part "TP1 MINI_1")))
    (comp (ref "D+,1") (value "NO") (libsource (lib "") (part "TP1 MINI_7")))
    (comp (ref "D+1") (value "NO") (libsource (lib "") (part "TP1 MINI_3")))
    (comp (ref "D-,1") (value "NO") (libsource (lib "") (part "TP1 MINI_18")))
    (comp (ref "D-1") (value "NO") (libsource (lib "") (part "TP1 MINI_10")))
    (comp (ref "D7") (value "SWDIO") (libsource (lib "") (part "TP1 MINI_5")))
    (comp (ref "D8")
      (value "1N5819WS S4_C2939001")
      (fields (field (name "Manufacturer Part") "1N5819WS S4") (field (name "Manufacturer") "KUU"))
      (libsource (lib "") (part "1N5819WS S4_C2939001"))
    )
    (comp (ref "D9")
      (value "1N5819WS S4_C2939001")
      (fields (field (name "Manufacturer Part") "1N5819WS S4") (field (name "Manufacturer") "KUU"))
      (libsource (lib "") (part "1N5819WS S4_C2939001"))
    )
    (comp (ref "DAT1") (value "TP1 MINI") (libsource (lib "") (part "TP1 MINI_8")))
    (comp (ref "G1") (value "TP1 MINI") (libsource (lib "") (part "TP1 MINI_12")))
    (comp (ref "GND1") (value "TP1") (libsource (lib "") (part "TP1_3")))
    (comp (ref "GND4") (value "TP1") (libsource (lib "") (part "TP1_3")))
    (comp (ref "GND5") (value "TP1") (libsource (lib "") (part "TP1_4")))
    (comp (ref "GND6") (value "TP1 MINI") (libsource (lib "") (part "TP1 MINI_21")))
    (comp (ref "H1") (value "HDR-F-2.54_1x4") (libsource (lib "") (part "HDR-F-2.54_1x4")))
    (comp (ref "J13")
      (value "USB-TYPE-C-018")
      (fields (field (name "Manufacturer") "DEALON(德艺隆)"))
      (libsource (lib "") (part "USB-TYPE-C-018"))
    )
    (comp (ref "R74")
      (value "220")
      (fields (field (name "Manufacturer Part") "0402WGJ0221TCE") (field (name "Manufacturer") "UniOhm"))
      (libsource (lib "") (part "0402WGJ0221TCE"))
    )
    (comp (ref "R75")
      (value "220")
      (fields (field (name "Manufacturer Part") "0402WGJ0221TCE") (field (name "Manufacturer") "UniOhm"))
      (libsource (lib "") (part "0402WGJ0221TCE"))
    )
    (comp (ref "R76")
      (value "5.1kΩ")
      (fields
        (field (name "Manufacturer Part") "0402WGF5101TCE")
        (field (name "Manufacturer") "UNI-ROYAL(厚声)")
      )
      (libsource (lib "") (part "0402WGF5101TCE"))
    )
    (comp (ref "R80")
      (value "5.1kΩ")
      (fields
        (field (name "Manufacturer Part") "0402WGF5101TCE")
        (field (name "Manufacturer") "UNI-ROYAL(厚声)")
      )
      (libsource (lib "") (part "0402WGF5101TCE"))
    )
    (comp (ref "R81")
      (value "10K")
      (fields (field (name "Manufacturer Part") "0402WGF1002TCE") (field (name "Manufacturer") "UniOhm"))
      (libsource (lib "") (part "0402WGF1002TCE"))
    )
    (comp (ref "R91")
      (value "1kΩ")
      (fields (field (name "Manufacturer Part") "RC0402FR-071KL") (field (name "Manufacturer") "YAGEO(国巨)"))
      (libsource (lib "") (part "RC0402FR-071KL"))
    )
    (comp (ref "R92")
      (value "1kΩ")
      (fields (field (name "Manufacturer Part") "RC0402FR-071KL") (field (name "Manufacturer") "YAGEO(国巨)"))
      (libsource (lib "") (part "RC0402FR-071KL"))
    )
    (comp (ref "R93")
      (value "22Ω")
      (fields (field (name "Manufacturer Part") "RC0402JR-0722RL") (field (name "Manufacturer") "YAGEO(国巨)"))
      (libsource (lib "") (part "RC0402JR-0722RL"))
    )
    (comp (ref "R96")
      (value "22Ω")
      (fields (field (name "Manufacturer Part") "RC0402JR-0722RL") (field (name "Manufacturer") "YAGEO(国巨)"))
      (libsource (lib "") (part "RC0402JR-0722RL"))
    )
    (comp (ref "R97")
      (value "22Ω")
      (fields (field (name "Manufacturer Part") "RC0402JR-0722RL") (field (name "Manufacturer") "YAGEO(国巨)"))
      (libsource (lib "") (part "RC0402JR-0722RL"))
    )
    (comp (ref "R99")
      (value "22Ω")
      (fields (field (name "Manufacturer Part") "RC0402JR-0722RL") (field (name "Manufacturer") "YAGEO(国巨)"))
      (libsource (lib "") (part "RC0402JR-0722RL"))
    )
    (comp (ref "R100")
      (value "22Ω")
      (fields (field (name "Manufacturer Part") "RC0402JR-0722RL") (field (name "Manufacturer") "YAGEO(国巨)"))
      (libsource (lib "") (part "RC0402JR-0722RL"))
    )
    (comp (ref "RX1") (value "TP1") (libsource (lib "") (part "TP1_2")))
    (comp (ref "SW1")
      (value "TS3425BA")
      (fields (field (name "Manufacturer") "SHOU HAN(首韩)"))
      (libsource (lib "") (part "TS3425BA"))
    )
    (comp (ref "SW1,") (value "NO") (libsource (lib "") (part "TP1 MINI_2")))
    (comp (ref "SW1/") (value "NO") (libsource (lib "") (part "TP1 MINI_6")))
    (comp (ref "SW2")
      (value "TS3425BA")
      (fields (field (name "Manufacturer") "SHOU HAN(首韩)"))
      (libsource (lib "") (part "TS3425BA"))
    )
    (comp (ref "SW2,") (value "NO") (libsource (lib "") (part "TP1 MINI_16")))
    (comp (ref "SW2/") (value "NO") (libsource (lib "") (part "TP1 MINI_15")))
    (comp (ref "SW3")
      (value "TS3425BA")
      (fields (field (name "Manufacturer") "SHOU HAN(首韩)"))
      (libsource (lib "") (part "TS3425BA"))
    )
    (comp (ref "SW3,") (value "TP1 MINI") (libsource (lib "") (part "TP1 MINI_11")))
    (comp (ref "SW3/") (value "TP1 MINI") (libsource (lib "") (part "TP1 MINI_13")))
    (comp (ref "TX1") (value "TP1") (libsource (lib "") (part "TP1_1")))
    (comp (ref "U8")
      (value "VTI7064MSME")
      (fields (field (name "Manufacturer") "Vilsion"))
      (libsource (lib "") (part "VTI7064MSME"))
    )
    (comp (ref "U10")
      (value "LY68L6400SLIT")
      (fields (field (name "Manufacturer") "Lyontek(来扬)"))
      (libsource (lib "") (part "LY68L6400SLIT"))
    )
    (comp (ref "U11")
      (value "RT9013-33GB")
      (fields (field (name "Manufacturer") "RICHTEK(立锜)"))
      (libsource (lib "") (part "RT9013-33GB"))
    )
    (comp (ref "U12")
      (value "W25Q16JVUXIQ")
      (fields (field (name "Manufacturer") "WINBOND(华邦)"))
      (libsource (lib "") (part "W25Q16JVUXIQ"))
    )
    (comp (ref "U13")
      (value "RP2040")
      (fields (field (name "Manufacturer") "Raspberry Pi(树莓派)"))
      (libsource (lib "") (part "RP2040"))
    )
    (comp (ref "Y1")
      (value "12MHz")
      (fields (field (name "Manufacturer Part") "TAXM12M4RDBCCT2T") (field (name "Manufacturer") "TAE(雅晶鑫)"))
      (libsource (lib "") (part "SMD-3225_4P12MHZ10PF10PPM-40&#126;+85℃"))
    )
  )
  (nets
    (net (code "1") (name "+") (class "Default")
      (node (ref "+") (pin "1") (pinfunction "1_1") (pintype "unspecified"))
      (node (ref "FPC2") (pin "3") (pinfunction "3_3") (pintype "unspecified"))
      (node (ref "R34") (pin "2") (pinfunction "2_2") (pintype "input"))
    )
    (net (code "2") (name "-") (class "Default")
      (node (ref "-") (pin "1") (pinfunction "1_1") (pintype "unspecified"))
      (node (ref "FPC2") (pin "2") (pinfunction "2_2") (pintype "unspecified"))
      (node (ref "R35") (pin "2") (pinfunction "2_2") (pintype "unspecified"))
    )
    (net (code "3") (name "1.8V") (class "Default")
      (node (ref "C18") (pin "2") (pinfunction "2_2") (pintype "input"))
      (node (ref "C23") (pin "1") (pinfunction "1_1") (pintype "input"))
      (node (ref "C24") (pin "2") (pinfunction "2_2") (pintype "input"))
      (node (ref "C42") (pin "1") (pinfunction "1_1") (pintype "unspecified"))
      (node (ref "IC1") (pin "120") (pinfunction "VCCK_3_120") (pintype "bidirectional"))
      (node (ref "IC1") (pin "23") (pinfunction "ADC_VDD_23") (pintype "bidirectional"))
      (node (ref "IC1") (pin "60") (pinfunction "VCCK_1_60") (pintype "bidirectional"))
      (node (ref "IC1") (pin "73") (pinfunction "VCCK_2_73") (pintype "bidirectional"))
      (node (ref "U3") (pin "2") (pinfunction "Out_2") (pintype "unspecified"))
      (node (ref "U3") (pin "4") (pinfunction "TAB_4") (pintype "unspecified"))
    )
    (net (code "4") (name "1HDMI") (class "Default")
      (node (ref "HDMI1") (pin "20") (pinfunction "20_20") (pintype "unspecified"))
      (node (ref "IC1") (pin "8") (pinfunction "V8_5_8") (pintype "bidirectional"))
      (node (ref "J1") (pin "1") (pinfunction "1_1") (pintype "unspecified"))
    )
    (net (code "5") (name "1V1") (class "Default")
      (node (ref "C88") (pin "2") (pinfunction "2_2") (pintype "input"))
      (node (ref "C89") (pin "2") (pinfunction "2_2") (pintype "input"))
      (node (ref "C90") (pin "2") (pinfunction "2_2") (pintype "input"))
      (node (ref "U13") (pin "23") (pinfunction "DVDD_23") (pintype "bidirectional"))
      (node (ref "U13") (pin "45") (pinfunction "VREG_VOUT_45") (pintype "bidirectional"))
      (node (ref "U13") (pin "50") (pinfunction "DVDD_50") (pintype "bidirectional"))
    )
    (net (code "6") (name "3.3V CONTROLADORA") (class "Default")
      (node (ref "C40") (pin "1") (pinfunction "1_1") (pintype "input"))
      (node (ref "C43") (pin "2") (pinfunction "2_2") (pintype "unspecified"))
      (node (ref "C48") (pin "2") (pinfunction "2_2") (pintype "input"))
      (node (ref "C49") (pin "2") (pinfunction "2_2") (pintype "input"))
      (node (ref "C53") (pin "2") (pinfunction "2_2") (pintype "input"))
      (node (ref "C57") (pin "2") (pinfunction "2_2") (pintype "input"))
      (node (ref "C58") (pin "2") (pinfunction "2_2") (pintype "input"))
      (node (ref "D5") (pin "2") (pinfunction "2_2") (pintype "unspecified"))
      (node (ref "D6") (pin "2") (pinfunction "2_2") (pintype "unspecified"))
      (node (ref "L10") (pin "1") (pinfunction "1_1") (pintype "unspecified"))
      (node (ref "L11") (pin "1") (pinfunction "1_1") (pintype "unspecified"))
      (node (ref "L12") (pin "1") (pinfunction "1_1") (pintype "unspecified"))
      (node (ref "L14") (pin "1") (pinfunction "1_1") (pintype "unspecified"))
      (node (ref "LEFT-1") (pin "1") (pinfunction "1_1") (pintype "unspecified"))
      (node (ref "LEFT-1") (pin "2") (pinfunction "2_2") (pintype "unspecified"))
      (node (ref "LEFT-1") (pin "3") (pinfunction "3_3") (pintype "unspecified"))
      (node (ref "Q2") (pin "1") (pinfunction "S_1") (pintype "unspecified"))
      (node (ref "Q2") (pin "2") (pinfunction "S_2") (pintype "unspecified"))
      (node (ref "Q2") (pin "3") (pinfunction "S_3") (pintype "unspecified"))
      (node (ref "R29") (pin "1") (pinfunction "1_1") (pintype "unspecified"))
      (node (ref "R51") (pin "2") (pinfunction "2_2") (pintype "unspecified"))
      (node (ref "R54") (pin "1") (pinfunction "1_1") (pintype "unspecified"))
      (node (ref "R64") (pin "2") (pinfunction "2_2") (pintype "unspecified"))
      (node (ref "R69") (pin "2") (pinfunction "2_2") (pintype "unspecified"))
      (node (ref "R71") (pin "2") (pinfunction "2_2") (pintype "unspecified"))
      (node (ref "R77") (pin "2") (pinfunction "2_2") (pintype "unspecified"))
      (node (ref "RIGHT-1") (pin "6") (pinfunction "6_6") (pintype "unspecified"))
      (node (ref "RIGHT-1") (pin "7") (pinfunction "7_7") (pintype "unspecified"))
      (node (ref "U4") (pin "2") (pinfunction "Vout_2") (pintype "unspecified"))
      (node (ref "U4") (pin "4") (pinfunction "Vout_4") (pintype "unspecified"))
      (node (ref "U5") (pin "24") (pinfunction "VDD_1_24") (pintype "unspecified"))
      (node (ref "U5") (pin "36") (pinfunction "VDD_2_36") (pintype "unspecified"))
      (node (ref "U5") (pin "48") (pinfunction "VDD_3_48") (pintype "unspecified"))
      (node (ref "U5") (pin "9") (pinfunction "VDDA_9") (pintype "unspecified"))
      (node (ref "U6") (pin "1") (pinfunction "1_1") (pintype "unspecified"))
      (node (ref "U6") (pin "2") (pinfunction "2_2") (pintype "unspecified"))
      (node (ref "U7") (pin "5") (pinfunction "3.5V_5") (pintype "unspecified"))
      (node (ref "VCC") (pin "1") (pinfunction "1_1") (pintype "unspecified"))
    )
    (net (code "7") (name "3HDMI") (class "Default")
      (node (ref "HDMI1") (pin "18") (pinfunction "18_18") (pintype "unspecified"))
      (node (ref "IC1") (pin "7") (pinfunction "V8_4_7") (pintype "bidirectional"))
      (node (ref "J2") (pin "1") (pinfunction "1_1") (pintype "unspecified"))
    )
    (net (code "8") (name "3V3") (class "Default")
      (node (ref "3V") (pin "1") (pinfunction "1_1") (pintype "unspecified"))
      (node (ref "3V3") (pin "1") (pinfunction "1_1") (pintype "unspecified"))
      (node (ref "3V3,") (pin "1") (pinfunction "1_1") (pintype "unspecified"))
      (node (ref "3V3/") (pin "1") (pinfunction "1_1") (pintype "unspecified"))
      (node (ref "C59") (pin "2") (pinfunction "2_2") (pintype "input"))
      (node (ref "C62") (pin "2") (pinfunction "2_2") (pintype "input"))
      (node (ref "C66") (pin "2") (pinfunction "2_2") (pintype "input"))
      (node (ref "C69") (pin "2") (pinfunction "2_2") (pintype "input"))
      (node (ref "C70") (pin "2") (pinfunction "2_2") (pintype "input"))
      (node (ref "C79") (pin "2") (pinfunction "2_2") (pintype "input"))
      (node (ref "C80") (pin "2") (pinfunction "2_2") (pintype "input"))
      (node (ref "C84") (pin "2") (pinfunction "2_2") (pintype "input"))
      (node (ref "C86") (pin "2") (pinfunction "2_2") (pintype "input"))
      (node (ref "C87") (pin "2") (pinfunction "2_2") (pintype "input"))
      (node (ref "CARD1") (pin "4") (pinfunction "VDD_4") (pintype "unspecified"))
      (node (ref "D8") (pin "1") (pinfunction "K_1") (pintype "unspecified"))
      (node (ref "H1") (pin "3") (pinfunction "3_3") (pintype "unspecified"))
      (node (ref "R81") (pin "1") (pinfunction "1_1") (pintype "input"))
      (node (ref "U10") (pin "8") (pinfunction "VCC_8") (pintype "unspecified"))
      (node (ref "U11") (pin "5") (pinfunction "VOUT_5") (pintype "unspecified"))
      (node (ref "U12") (pin "8") (pinfunction "VCC_8") (pintype "unspecified"))
      (node (ref "U13") (pin "1") (pinfunction "IOVDD_1") (pintype "bidirectional"))
      (node (ref "U13") (pin "10") (pinfunction "IOVDD_10") (pintype "bidirectional"))
      (node (ref "U13") (pin "22") (pinfunction "IOVDD_22") (pintype "bidirectional"))
      (node (ref "U13") (pin "26") (pinfunction "RUN_26") (pintype "input"))
      (node (ref "U13") (pin "33") (pinfunction "IOVDD_33") (pintype "bidirectional"))
      (node (ref "U13") (pin "42") (pinfunction "IOVDD_42") (pintype "bidirectional"))
      (node (ref "U13") (pin "43") (pinfunction "ADC_AVDD_43") (pintype "bidirectional"))
      (node (ref "U13") (pin "44") (pinfunction "VREG_IN_44") (pintype "bidirectional"))
      (node (ref "U13") (pin "48") (pinfunction "USB_VDD_48") (pintype "bidirectional"))
      (node (ref "U13") (pin "49") (pinfunction "IOVDD_49") (pintype "bidirectional"))
      (node (ref "U8") (pin "8") (pinfunction "VDD_8") (pintype "unspecified"))
    )
    (net (code "9") (name "4HDMI") (class "Default")
      (node (ref "HDMI1") (pin "17") (pinfunction "17_17") (pintype "unspecified"))
      (node (ref "IC1") (pin "6") (pinfunction "V8_3_6") (pintype "bidirectional"))
      (node (ref "J7") (pin "1") (pinfunction "1_1") (pintype "unspecified"))
    )
    (net (code "10") (name "5V") (class "Default")
      (node (ref "5V") (pin "1") (pinfunction "1_1") (pintype "unspecified"))
      (node (ref "C61") (pin "2") (pinfunction "2_2") (pintype "input"))
      (node (ref "C63") (pin "1") (pinfunction "1_1") (pintype "input"))
      (node (ref "C74") (pin "1") (pinfunction "1_1") (pintype "unspecified"))
      (node (ref "PS2") (pin "4") (pinfunction "4_4") (pintype "unspecified"))
      (node (ref "PS2") (pin "5") (pinfunction "5_5") (pintype "unspecified"))
      (node (ref "PS2") (pin "6") (pinfunction "6_6") (pintype "unspecified"))
      (node (ref "PS2") (pin "7") (pinfunction "7_7") (pintype "unspecified"))
      (node (ref "PS2") (pin "8") (pinfunction "8_8") (pintype "unspecified"))
      (node (ref "R101") (pin "1") (pinfunction "1_1") (pintype "input"))
      (node (ref "R43") (pin "2") (pinfunction "2_2") (pintype "unspecified"))
      (node (ref "R62") (pin "1") (pinfunction "1_1") (pintype "unspecified"))
      (node (ref "R73") (pin "2") (pinfunction "2_2") (pintype "unspecified"))
      (node (ref "R94") (pin "2") (pinfunction "2_2") (pintype "input"))
      (node (ref "U3") (pin "3") (pinfunction "In_3") (pintype "unspecified"))
      (node (ref "U4") (pin "3") (pinfunction "Vin_3") (pintype "unspecified"))
      (node (ref "U9") (pin "10") (pinfunction "VDD_10") (pintype "unspecified"))
      (node (ref "U9") (pin "15") (pinfunction "VDD_15") (pintype "unspecified"))
    )
    (net (code "11") (name "6HDMI") (class "Default")
      (node (ref "HDMI1") (pin "15") (pinfunction "15_15") (pintype "unspecified"))
      (node (ref "IC1") (pin "5") (pinfunction "V8_2_5") (pintype "bidirectional"))
      (node (ref "J8") (pin "1") (pinfunction "1_1") (pintype "unspecified"))
    )
    (net (code "12") (name "7FFC") (class "Default")
      (node (ref "C55") (pin "2") (pinfunction "2_2") (pintype "unspecified"))
      (node (ref "FPC1") (pin "7") (pinfunction "7_7") (pintype "unspecified"))
      (node (ref "R87") (pin "2") (pinfunction "2_2") (pintype "unspecified"))
    )
    (net (code "13") (name "7HDMI") (class "Default")
      (node (ref "HDMI1") (pin "14") (pinfunction "14_14") (pintype "unspecified"))
      (node (ref "IC1") (pin "4") (pinfunction "V8_1_4") (pintype "bidirectional"))
      (node (ref "J3") (pin "1") (pinfunction "1_1") (pintype "unspecified"))
    )
    (net (code "14") (name "8FFC") (class "Default")
      (node (ref "C31") (pin "2") (pinfunction "2_2") (pintype "unspecified"))
      (node (ref "C32") (pin "2") (pinfunction "2_2") (pintype "input"))
      (node (ref "D2") (pin "1") (pinfunction "1_1") (pintype "unspecified"))
      (node (ref "D3") (pin "1") (pinfunction "A_1") (pintype "unspecified"))
      (node (ref "FPC1") (pin "8") (pinfunction "8_8") (pintype "unspecified"))
      (node (ref "R86") (pin "1") (pinfunction "1_1") (pintype "unspecified"))
    )
    (net (code "15") (name "9HDMI") (class "Default")
      (node (ref "HDMI1") (pin "12") (pinfunction "12_12") (pintype "unspecified"))
      (node (ref "IC1") (pin "3") (pinfunction "V8_0_3") (pintype "bidirectional"))
      (node (ref "J4") (pin "1") (pinfunction "1_1") (pintype "unspecified"))
    )
    (net (code "16") (name "10HDMI") (class "Default")
      (node (ref "HDMI1") (pin "11") (pinfunction "11_11") (pintype "unspecified"))
      (node (ref "IC1") (pin "9") (pinfunction "V8_6_9") (pintype "bidirectional"))
      (node (ref "J9") (pin "1") (pinfunction "1_1") (pintype "unspecified"))
    )
    (net (code "17") (name "11FFC") (class "Default")
      (node (ref "FPC1") (pin "11") (pinfunction "11_11") (pintype "unspecified"))
      (node (ref "R19") (pin "2") (pinfunction "2_2") (pintype "unspecified"))
    )
    (net (code "18") (name "12FFC") (class "Default")
      (node (ref "FPC1") (pin "12") (pinfunction "12_12") (pintype "unspecified"))
      (node (ref "R17") (pin "2") (pinfunction "2_2") (pintype "unspecified"))
    )
    (net (code "19") (name "12HDMI") (class "Default")
      (node (ref "HDMI1") (pin "9") (pinfunction "9_9") (pintype "unspecified"))
      (node (ref "IC1") (pin "10") (pinfunction "V8_7_10") (pintype "bidirectional"))
      (node (ref "J10") (pin "1") (pinfunction "1_1") (pintype "unspecified"))
    )
    (net (code "20") (name "18HDMI") (class "Default")
      (node (ref "HDMI1") (pin "3") (pinfunction "3_3") (pintype "unspecified"))
      (node (ref "J12") (pin "1") (pinfunction "1_1") (pintype "unspecified"))
      (node (ref "R64") (pin "1") (pinfunction "1_1") (pintype "unspecified"))
    )
    (net (code "21") (name "19HDMI") (class "Default")
      (node (ref "HDMI1") (pin "2") (pinfunction "2_2") (pintype "unspecified"))
      (node (ref "J6") (pin "1") (pinfunction "1_1") (pintype "unspecified"))
      (node (ref "R71") (pin "1") (pinfunction "1_1") (pintype "unspecified"))
    )
    (net (code "22") (name "44FFC") (class "Default")
      (node (ref "C36") (pin "2") (pinfunction "2_2") (pintype "input"))
      (node (ref "C41") (pin "2") (pinfunction "2_2") (pintype "unspecified"))
      (node (ref "FPC1") (pin "44") (pinfunction "44_44") (pintype "unspecified"))
      (node (ref "FPC6") (pin "4") (pinfunction "4_4") (pintype "unspecified"))
      (node (ref "Q2") (pin "5") (pinfunction "D_5") (pintype "unspecified"))
      (node (ref "Q2") (pin "6") (pinfunction "D_6") (pintype "unspecified"))
      (node (ref "Q2") (pin "7") (pinfunction "D_7") (pintype "unspecified"))
      (node (ref "Q2") (pin "8") (pinfunction "D_8") (pintype "unspecified"))
    )
    (net (code "23") (name "45FFC") (class "Default")
      (node (ref "C56") (pin "2") (pinfunction "2_2") (pintype "unspecified"))
      (node (ref "FPC1") (pin "45") (pinfunction "45_45") (pintype "unspecified"))
      (node (ref "FPC1") (pin "5") (pinfunction "5_5") (pintype "unspecified"))
      (node (ref "R85") (pin "2") (pinfunction "2_2") (pintype "unspecified"))
      (node (ref "R86") (pin "2") (pinfunction "2_2") (pintype "unspecified"))
    )
    (net (code "24") (name "99") (class "Default")
      (node (ref "40P") (pin "1") (pinfunction "1_1") (pintype "input"))
      (node (ref "IC1") (pin "99") (pinfunction "GPIO/PWM3/TCON[11][6]_99") (pintype "bidirectional"))
      (node (ref "R17") (pin "1") (pinfunction "1_1") (pintype "unspecified"))
      (node (ref "R18") (pin "2") (pinfunction "2_2") (pintype "unspecified"))
    )
    (net (code "25") (name "102, PWM0") (class "Default")
      (node (ref "IC1") (pin "102") (pinfunction "SD3/SPDIF3/TCON[10]/GPIO/PWM0_102") (pintype "bidirectional"))
      (node (ref "R47") (pin "2") (pinfunction "2_2") (pintype "unspecified"))
    )
    (net (code "26") (name "110,WS{slash}GPIO") (class "Default")
      (node (ref "IC1") (pin "110") (pinfunction "WS/TCON[6]/GPIO_110") (pintype "bidirectional"))
      (node (ref "R53") (pin "1") (pinfunction "1_1") (pintype "unspecified"))
      (node (ref "R54") (pin "2") (pinfunction "2_2") (pintype "unspecified"))
    )
    (net (code "27") (name "111, SD0") (class "Default")
      (node (ref "IC1") (pin "111") (pinfunction "SD0/SPDIF0/TCON[4]/GPIO_111") (pintype "bidirectional"))
      (node (ref "R89") (pin "1") (pinfunction "1_1") (pintype "unspecified"))
      (node (ref "R90") (pin "2") (pinfunction "2_2") (pintype "unspecified"))
    )
    (net (code "28") (name "123, DDCSDA2") (class "Default")
      (node (ref "HDMI1") (pin "5") (pinfunction "5_5") (pintype "unspecified"))
      (node (ref "J11") (pin "1") (pinfunction "1_1") (pintype "unspecified"))
      (node (ref "R49") (pin "1") (pinfunction "1_1") (pintype "unspecified"))
    )
    (net (code "29") (name "124, DDCSCL2") (class "Default")
      (node (ref "HDMI1") (pin "6") (pinfunction "6_6") (pintype "unspecified"))
      (node (ref "J5") (pin "1") (pinfunction "1_1") (pintype "unspecified"))
      (node (ref "R50") (pin "1") (pinfunction "1_1") (pintype "unspecified"))
    )
    (net (code "30") (name "ACK") (class "Default")
      (node (ref "ACK") (pin "1") (pinfunction "1_1") (pintype "unspecified"))
      (node (ref "CONTROL3") (pin "1") (pinfunction "1_1") (pintype "unspecified"))
      (node (ref "U5") (pin "29") (pinfunction "PA8_29") (pintype "unspecified"))
    )
    (net (code "31") (name "ACKM") (class "Default")
      (node (ref "CONTROL3") (pin "3") (pinfunction "3_3") (pintype "unspecified"))
      (node (ref "U7") (pin "8") (pinfunction "ACK_8") (pintype "unspecified"))
    )
    (net (code "32") (name "ATT") (class "Default")
      (node (ref "ATT") (pin "1") (pinfunction "1_1") (pintype "unspecified"))
      (node (ref "CONTROL3") (pin "7") (pinfunction "7_7") (pintype "unspecified"))
      (node (ref "U5") (pin "25") (pinfunction "PB12_25") (pintype "unspecified"))
    )
    (net (code "33") (name "ATTM") (class "Default")
      (node (ref "CONTROL3") (pin "5") (pinfunction "5_5") (pintype "unspecified"))
      (node (ref "U7") (pin "6") (pinfunction "ATT_6") (pintype "unspecified"))
    )
    (net (code "34") (name "BO") (class "Default")
      (node (ref "B") (pin "1") (pinfunction "1_1") (pintype "unspecified"))
      (node (ref "L9") (pin "2") (pinfunction "2_2") (pintype "unspecified"))
      (node (ref "PS2") (pin "25") (pinfunction "25_25") (pintype "unspecified"))
    )
    (net (code "35") (name "BOOT0") (class "Default")
      (node (ref "R66") (pin "1") (pinfunction "1_1") (pintype "input"))
      (node (ref "U5") (pin "44") (pinfunction "BOOT0_44") (pintype "unspecified"))
    )
    (net (code "36") (name "BOOT1") (class "Default")
      (node (ref "R67") (pin "2") (pinfunction "2_2") (pintype "input"))
      (node (ref "U5") (pin "20") (pinfunction "PB2_20") (pintype "unspecified"))
    )
    (net (code "37") (name "CLK") (class "Default")
      (node (ref "CLK") (pin "1") (pinfunction "1_1") (pintype "unspecified"))
      (node (ref "CONTROL3") (pin "6") (pinfunction "6_6") (pintype "unspecified"))
      (node (ref "U5") (pin "26") (pinfunction "PB13_26") (pintype "unspecified"))
    )
    (net (code "38") (name "CLKM") (class "Default")
      (node (ref "CONTROL3") (pin "4") (pinfunction "4_4") (pintype "unspecified"))
      (node (ref "U7") (pin "7") (pinfunction "CLK_7") (pintype "unspecified"))
    )
    (net (code "39") (name "CMDM") (class "Default")
      (node (ref "CONTROL3") (pin "9") (pinfunction "9_9") (pintype "unspecified"))
      (node (ref "U7") (pin "2") (pinfunction "CMD_2") (pintype "unspecified"))
    )
    (net (code "40") (name "CO") (class "Default")
      (node (ref "AV1") (pin "1") (pinfunction "1_1") (pintype "unspecified"))
      (node (ref "L1.") (pin "2") (pinfunction "2_2") (pintype "unspecified"))
      (node (ref "PS2") (pin "27") (pinfunction "27_27") (pintype "unspecified"))
    )
    (net (code "41") (name "COMM") (class "Default")
      (node (ref "COM") (pin "1") (pinfunction "1_1") (pintype "unspecified"))
      (node (ref "CONTROL3") (pin "11") (pinfunction "11_11") (pintype "unspecified"))
      (node (ref "U5") (pin "28") (pinfunction "PB15_28") (pintype "unspecified"))
    )
    (net (code "42") (name "CS") (class "Default")
      (node (ref "R11") (pin "1") (pinfunction "1_1") (pintype "unspecified"))
      (node (ref "U1") (pin "1") (pinfunction "CS#_1") (pintype "unspecified"))
    )
    (net (code "43") (name "Circle") (class "Default")
      (node (ref "CIRCLE") (pin "1") (pinfunction "1_1") (pintype "unspecified"))
      (node (ref "RIGHT-1") (pin "13") (pinfunction "13_13") (pintype "unspecified"))
      (node (ref "U5") (pin "46") (pinfunction "PB9_46") (pintype "unspecified"))
    )
    (net (code "44") (name "Cross") (class "Default")
      (node (ref "CROSS") (pin "1") (pinfunction "1_1") (pintype "unspecified"))
      (node (ref "RIGHT-1") (pin "12") (pinfunction "12_12") (pintype "unspecified"))
      (node (ref "U5") (pin "45") (pinfunction "PB8_45") (pintype "unspecified"))
    )
    (net (code "45") (name "D+") (class "Default")
      (node (ref "J13") (pin "A6") (pinfunction "DP1_A6") (pintype "unspecified"))
      (node (ref "J13") (pin "B6") (pinfunction "DP2_B6") (pintype "unspecified"))
      (node (ref "R96") (pin "2") (pinfunction "2_2") (pintype "input"))
    )
    (net (code "46") (name "D-") (class "Default")
      (node (ref "J13") (pin "A7") (pinfunction "DN1_A7") (pintype "unspecified"))
      (node (ref "J13") (pin "B7") (pinfunction "DN2_B7") (pintype "unspecified"))
      (node (ref "R93") (pin "2") (pinfunction "2_2") (pintype "input"))
    )
    (net (code "47") (name "DAT") (class "Default")
      (node (ref "CONTROL3") (pin "12") (pinfunction "12_12") (pintype "unspecified"))
      (node (ref "DAT") (pin "1") (pinfunction "1_1") (pintype "unspecified"))
      (node (ref "U5") (pin "27") (pinfunction "PB14_27") (pintype "unspecified"))
    )
    (net (code "48") (name "DATM") (class "Default")
      (node (ref "CONTROL3") (pin "10") (pinfunction "10_10") (pintype "unspecified"))
      (node (ref "U7") (pin "1") (pinfunction "DAT_1") (pintype "unspecified"))
    )
    (net (code "49") (name "DISP") (class "Default")
      (node (ref "FPC6") (pin "31") (pinfunction "31_31") (pintype "unspecified"))
      (node (ref "R78") (pin "1") (pinfunction "1_1") (pintype "unspecified"))
    )
    (net (code "50") (name "Down") (class "Default")
      (node (ref "DOWN") (pin "1") (pinfunction "1_1") (pintype "unspecified"))
      (node (ref "LEFT-1") (pin "14") (pinfunction "14_14") (pintype "unspecified"))
      (node (ref "U5") (pin "14") (pinfunction "PA4_14") (pintype "unspecified"))
    )
    (net (code "51") (name "FPC 1,2") (class "Default")
      (node (ref "C30") (pin "1") (pinfunction "1_1") (pintype "unspecified"))
      (node (ref "C85") (pin "1") (pinfunction "1_1") (pintype "unspecified"))
      (node (ref "D1") (pin "1") (pinfunction "1_1") (pintype "unspecified"))
      (node (ref "FPC1") (pin "49") (pinfunction "49_49") (pintype "unspecified"))
      (node (ref "FPC1") (pin "50") (pinfunction "50_50") (pintype "unspecified"))
      (node (ref "FPC6") (pin "2") (pinfunction "2_2") (pintype "unspecified"))
      (node (ref "U2") (pin "5") (pinfunction "OV_5") (pintype "unspecified"))
    )
    (net (code "52") (name "FPC 3,4") (class "Default")
      (node (ref "FPC1") (pin "47") (pinfunction "47_47") (pintype "unspecified"))
      (node (ref "FPC1") (pin "48") (pinfunction "48_48") (pintype "unspecified"))
      (node (ref "FPC6") (pin "1") (pinfunction "1_1") (pintype "unspecified"))
      (node (ref "R33") (pin "2") (pinfunction "2_2") (pintype "unspecified"))
      (node (ref "R41") (pin "2") (pinfunction "2_2") (pintype "unspecified"))
    )
    (net (code "53") (name "FPC 9, DENA") (class "Default")
      (node (ref "FPC1") (pin "42") (pinfunction "42_42") (pintype "unspecified"))
      (node (ref "FPC6") (pin "34") (pinfunction "34_34") (pintype "unspecified"))
      (node (ref "IC1") (pin "94") (pinfunction "DENA/TXE0+_94") (pintype "bidirectional"))
    )
    (net (code "54") (name "FPC 10, DVS") (class "Default")
      (node (ref "FPC1") (pin "41") (pinfunction "41_41") (pintype "unspecified"))
      (node (ref "IC1") (pin "97") (pinfunction "DVS/GPIO/PWM1_97") (pintype "bidirectional"))
      (node (ref "VS") (pin "1") (pinfunction "1_1") (pintype "input"))
    )
    (net (code "55") (name "FPC 11, DHS") (class "Default")
      (node (ref "FPC1") (pin "40") (pinfunction "40_40") (pintype "unspecified"))
      (node (ref "HS") (pin "1") (pinfunction "1_1") (pintype "input"))
      (node (ref "IC1") (pin "95") (pinfunction "DHS/TXE0-_95") (pintype "bidirectional"))
    )
    (net (code "56") (name "FPC 12, ARED0") (class "Default")
      (node (ref "FPC1") (pin "39") (pinfunction "39_39") (pintype "unspecified"))
      (node (ref "FPC6") (pin "5") (pinfunction "5_5") (pintype "unspecified"))
      (node (ref "IC1") (pin "93") (pinfunction "ARED0/ARED2_/TXE1-_93") (pintype "bidirectional"))
    )
    (net (code "57") (name "FPC 13, ARED1") (class "Default")
      (node (ref "FPC1") (pin "38") (pinfunction "38_38") (pintype "unspecified"))
      (node (ref "FPC6") (pin "6") (pinfunction "6_6") (pintype "unspecified"))
      (node (ref "IC1") (pin "92") (pinfunction "ARED1/ARED3_/TXE1+_92") (pintype "bidirectional"))
    )
    (net (code "58") (name "FPC 14, ARED2") (class "Default")
      (node (ref "FPC1") (pin "37") (pinfunction "37_37") (pintype "unspecified"))
      (node (ref "FPC6") (pin "7") (pinfunction "7_7") (pintype "unspecified"))
      (node (ref "IC1") (pin "91") (pinfunction "ARED2/ARED4_/_TXE2-_91") (pintype "bidirectional"))
    )
    (net (code "59") (name "FPC 15, ARED3") (class "Default")
      (node (ref "FPC1") (pin "36") (pinfunction "36_36") (pintype "unspecified"))
      (node (ref "FPC6") (pin "8") (pinfunction "8_8") (pintype "unspecified"))
      (node (ref "IC1") (pin "90") (pinfunction "ARED3/ARED5_/_TXE2+_90") (pintype "bidirectional"))
    )
    (net (code "60") (name "FPC 16, ARED4") (class "Default")
      (node (ref "FPC1") (pin "35") (pinfunction "35_35") (pintype "unspecified"))
      (node (ref "FPC6") (pin "9") (pinfunction "9_9") (pintype "unspecified"))
      (node (ref "IC1") (pin "89") (pinfunction "ARED4/ARED6_/TXEC-_89") (pintype "bidirectional"))
    )
    (net (code "61") (name "FPC 17, ARED5") (class "Default")
      (node (ref "FPC1") (pin "34") (pinfunction "34_34") (pintype "unspecified"))
      (node (ref "FPC6") (pin "10") (pinfunction "10_10") (pintype "unspecified"))
      (node (ref "IC1") (pin "88") (pinfunction "ARED5/ARED7_/TXEC+_88") (pintype "bidirectional"))
    )
    (net (code "62") (name "FPC 18, ARED6") (class "Default")
      (node (ref "FPC1") (pin "33") (pinfunction "33_33") (pintype "unspecified"))
      (node (ref "FPC6") (pin "11") (pinfunction "11_11") (pintype "unspecified"))
      (node (ref "IC1") (pin "87") (pinfunction "ARED6/AGRN2_/TXE3-_87") (pintype "bidirectional"))
    )
    (net (code "63") (name "FPC 19, ARED7") (class "Default")
      (node (ref "FPC1") (pin "32") (pinfunction "32_32") (pintype "unspecified"))
      (node (ref "FPC6") (pin "12") (pinfunction "12_12") (pintype "unspecified"))
      (node (ref "IC1") (pin "86") (pinfunction "ARED7/AGRN3_/TXE3+_86") (pintype "bidirectional"))
    )
    (net (code "64") (name "FPC 20, AGRN0") (class "Default")
      (node (ref "FPC1") (pin "31") (pinfunction "31_31") (pintype "unspecified"))
      (node (ref "FPC6") (pin "13") (pinfunction "13_13") (pintype "unspecified"))
      (node (ref "IC1") (pin "83") (pinfunction "AGRN0/GPIO/AGRN4/TXO0-_83") (pintype "bidirectional"))
    )
    (net (code "65") (name "FPC 21, AGRN1") (class "Default")
      (node (ref "FPC1") (pin "30") (pinfunction "30_30") (pintype "unspecified"))
      (node (ref "FPC6") (pin "14") (pinfunction "14_14") (pintype "unspecified"))
      (node (ref "IC1") (pin "82") (pinfunction "AGRN1/GPIO/AGRN5_/TXO0+_82") (pintype "bidirectional"))
    )
    (net (code "66") (name "FPC 22, AGRN2") (class "Default")
      (node (ref "FPC1") (pin "29") (pinfunction "29_29") (pintype "unspecified"))
      (node (ref "FPC6") (pin "15") (pinfunction "15_15") (pintype "unspecified"))
      (node (ref "IC1") (pin "81") (pinfunction "AGRN2/GPIO/AGRN6/TXO1-_81") (pintype "bidirectional"))
    )
    (net (code "67") (name "FPC 23, AGRN3") (class "Default")
      (node (ref "FPC1") (pin "28") (pinfunction "28_28") (pintype "unspecified"))
      (node (ref "FPC6") (pin "16") (pinfunction "16_16") (pintype "unspecified"))
      (node (ref "IC1") (pin "80") (pinfunction "AGRN3/GPIO/AGRN7_/TXO1+_80") (pintype "bidirectional"))
    )
    (net (code "68") (name "FPC 24, AGRN4") (class "Default")
      (node (ref "FPC1") (pin "27") (pinfunction "27_27") (pintype "unspecified"))
      (node (ref "FPC6") (pin "17") (pinfunction "17_17") (pintype "unspecified"))
      (node (ref "IC1") (pin "79") (pinfunction "AGRN4/GPIO/ABLU2_/TXO2-_79") (pintype "bidirectional"))
    )
    (net (code "69") (name "FPC 25, AGRN5") (class "Default")
      (node (ref "FPC1") (pin "26") (pinfunction "26_26") (pintype "unspecified"))
      (node (ref "FPC6") (pin "18") (pinfunction "18_18") (pintype "unspecified"))
      (node (ref "IC1") (pin "78") (pinfunction "AGRN5/GPIO/ABLU3_/TXO2+_78") (pintype "bidirectional"))
    )
    (net (code "70") (name "FPC 26, AGRN6") (class "Default")
      (node (ref "FPC1") (pin "25") (pinfunction "25_25") (pintype "unspecified"))
      (node (ref "FPC6") (pin "19") (pinfunction "19_19") (pintype "unspecified"))
      (node (ref "IC1") (pin "77") (pinfunction "AGRN6/GPIO/ABLU4/_TXOC-_77") (pintype "bidirectional"))
    )
    (net (code "71") (name "FPC 27, AGRN7") (class "Default")
      (node (ref "FPC1") (pin "24") (pinfunction "24_24") (pintype "unspecified"))
      (node (ref "FPC6") (pin "20") (pinfunction "20_20") (pintype "unspecified"))
      (node (ref "IC1") (pin "76") (pinfunction "AGRN7/GPIO/ABLU5_/_TXOC+_76") (pintype "bidirectional"))
    )
    (net (code "72") (name "FPC 28, ABLU0") (class "Default")
      (node (ref "FPC1") (pin "23") (pinfunction "23_23") (pintype "unspecified"))
      (node (ref "FPC6") (pin "21") (pinfunction "21_21") (pintype "unspecified"))
      (node (ref "IC1") (pin "75") (pinfunction "ABLU0/GPIO/ABLU6_/_TXO3-_75") (pintype "bidirectional"))
    )
    (net (code "73") (name "FPC 29, ABLU1") (class "Default")
      (node (ref "FPC1") (pin "22") (pinfunction "22_22") (pintype "unspecified"))
      (node (ref "FPC6") (pin "22") (pinfunction "22_22") (pintype "unspecified"))
      (node (ref "IC1") (pin "74") (pinfunction "ABLU1/GPIO/ABLU7/TXO3+_74") (pintype "bidirectional"))
    )
    (net (code "74") (name "FPC 30, ABLU2") (class "Default")
      (node (ref "FPC1") (pin "21") (pinfunction "21_21") (pintype "unspecified"))
      (node (ref "FPC6") (pin "23") (pinfunction "23_23") (pintype "unspecified"))
      (node (ref "IC1") (pin "71") (pinfunction "ABLU2/SPDIF3/SD3/TCON[10][8]/GPIO/PWM1/PWM5_71") (pintype "bidirectional"))
    )
    (net (code "75") (name "FPC 31, ABLU3") (class "Default")
      (node (ref "FPC1") (pin "20") (pinfunction "20_20") (pintype "unspecified"))
      (node (ref "FPC6") (pin "24") (pinfunction "24_24") (pintype "unspecified"))
      (node (ref "IC1") (pin "70") (pinfunction "ABLU3/SPDIF2/SD2/TCON[9][11]/GPIO/IICSDA_70") (pintype "bidirectional"))
    )
    (net (code "76") (name "FPC 32, ABLU4") (class "Default")
      (node (ref "FPC1") (pin "19") (pinfunction "19_19") (pintype "unspecified"))
      (node (ref "FPC6") (pin "25") (pinfunction "25_25") (pintype "unspecified"))
      (node (ref "IC1") (pin "69") (pinfunction "ABLU4/SPDIF1/SD1/TCON[7][3]/GPIO/IICSCL_69") (pintype "bidirectional"))
    )
    (net (code "77") (name "FPC 33, ABLU5") (class "Default")
      (node (ref "FPC1") (pin "18") (pinfunction "18_18") (pintype "unspecified"))
      (node (ref "FPC6") (pin "26") (pinfunction "26_26") (pintype "unspecified"))
      (node (ref "IC1") (pin "68") (pinfunction "ABLU5/SD0/SPDIF0/TCON[13][3]/GPIO_68") (pintype "bidirectional"))
    )
    (net (code "78") (name "FPC 34, ABLU6") (class "Default")
      (node (ref "FPC1") (pin "17") (pinfunction "17_17") (pintype "unspecified"))
      (node (ref "FPC6") (pin "27") (pinfunction "27_27") (pintype "unspecified"))
      (node (ref "IC1") (pin "67") (pinfunction "ABLU6/MCK/TCON[5][9]/GPIO_67") (pintype "bidirectional"))
    )
    (net (code "79") (name "FPC 35, ABLU7") (class "Default")
      (node (ref "FPC1") (pin "16") (pinfunction "16_16") (pintype "unspecified"))
      (node (ref "FPC6") (pin "28") (pinfunction "28_28") (pintype "unspecified"))
      (node (ref "IC1") (pin "66") (pinfunction "ABLU7/SCK/TCON[4][2]/GPIO_66") (pintype "bidirectional"))
    )
    (net (code "80") (name "FPC 41") (class "Default")
      (node (ref "C12") (pin "1") (pinfunction "1_1") (pintype "unspecified"))
      (node (ref "FPC1") (pin "10") (pinfunction "10_10") (pintype "unspecified"))
      (node (ref "R84") (pin "2") (pinfunction "2_2") (pintype "unspecified"))
    )
    (net (code "81") (name "FPC 42") (class "Default")
      (node (ref "C15") (pin "2") (pinfunction "2_2") (pintype "unspecified"))
      (node (ref "FPC1") (pin "9") (pinfunction "9_9") (pintype "unspecified"))
      (node (ref "R83") (pin "2") (pinfunction "2_2") (pintype "unspecified"))
    )
    (net (code "82") (name "FPC37, DCLK") (class "Default")
      (node (ref "FPC1") (pin "14") (pinfunction "14_14") (pintype "unspecified"))
      (node (ref "FPC6") (pin "30") (pinfunction "30_30") (pintype "unspecified"))
      (node (ref "IC1") (pin "96") (pinfunction "DCLK/GPIO/PWM0_96") (pintype "bidirectional"))
    )
    (net (code "83") (name "GND") (class "Default")
      (node (ref "C1") (pin "1") (pinfunction "1_1") (pintype "unspecified"))
      (node (ref "C11") (pin "2") (pinfunction "2_2") (pintype "input"))
      (node (ref "C12") (pin "2") (pinfunction "2_2") (pintype "unspecified"))
      (node (ref "C15") (pin "1") (pinfunction "1_1") (pintype "unspecified"))
      (node (ref "C16") (pin "1") (pinfunction "1_1") (pintype "input"))
      (node (ref "C17") (pin "1") (pinfunction "1_1") (pintype "input"))
      (node (ref "C18") (pin "1") (pinfunction "1_1") (pintype "input"))
      (node (ref "C19") (pin "2") (pinfunction "2_2") (pintype "unspecified"))
      (node (ref "C2") (pin "2") (pinfunction "2_2") (pintype "unspecified"))
      (node (ref "C20") (pin "1") (pinfunction "1_1") (pintype "input"))
      (node (ref "C21") (pin "2") (pinfunction "2_2") (pintype "input"))
      (node (ref "C22") (pin "2") (pinfunction "2_2") (pintype "input"))
      (node (ref "C23") (pin "2") (pinfunction "2_2") (pintype "input"))
      (node (ref "C24") (pin "1") (pinfunction "1_1") (pintype "input"))
      (node (ref "C25") (pin "1") (pinfunction "1_1") (pintype "input"))
      (node (ref "C26") (pin "2") (pinfunction "2_2") (pintype "input"))
      (node (ref "C27") (pin "2") (pinfunction "2_2") (pintype "input"))
      (node (ref "C28") (pin "2") (pinfunction "2_2") (pintype "input"))
      (node (ref "C29") (pin "2") (pinfunction "2_2") (pintype "input"))
      (node (ref "C30") (pin "2") (pinfunction "2_2") (pintype "unspecified"))
      (node (ref "C31") (pin "1") (pinfunction "1_1") (pintype "unspecified"))
      (node (ref "C32") (pin "1") (pinfunction "1_1") (pintype "input"))
      (node (ref "C36") (pin "1") (pinfunction "1_1") (pintype "input"))
      (node (ref "C38") (pin "1") (pinfunction "1_1") (pintype "input"))
      (node (ref "C39") (pin "1") (pinfunction "1_1") (pintype "input"))
      (node (ref "C40") (pin "2") (pinfunction "2_2") (pintype "input"))
      (node (ref "C41") (pin "1") (pinfunction "1_1") (pintype "unspecified"))
      (node (ref "C42") (pin "2") (pinfunction "2_2") (pintype "unspecified"))
      (node (ref "C43") (pin "1") (pinfunction "1_1") (pintype "unspecified"))
      (node (ref "C48") (pin "1") (pinfunction "1_1") (pintype "input"))
      (node (ref "C49") (pin "1") (pinfunction "1_1") (pintype "input"))
      (node (ref "C50") (pin "1") (pinfunction "1_1") (pintype "unspecified"))
      (node (ref "C52") (pin "1") (pinfunction "1_1") (pintype "unspecified"))
      (node (ref "C53") (pin "1") (pinfunction "1_1") (pintype "input"))
      (node (ref "C54") (pin "1") (pinfunction "1_1") (pintype "unspecified"))
      (node (ref "C55") (pin "1") (pinfunction "1_1") (pintype "unspecified"))
      (node (ref "C56") (pin "1") (pinfunction "1_1") (pintype "unspecified"))
      (node (ref "C57") (pin "1") (pinfunction "1_1") (pintype "input"))
      (node (ref "C58") (pin "1") (pinfunction "1_1") (pintype "input"))
      (node (ref "C59") (pin "1") (pinfunction "1_1") (pintype "input"))
      (node (ref "C60") (pin "1") (pinfunction "1_1") (pintype "input"))
      (node (ref "C61") (pin "1") (pinfunction "1_1") (pintype "input"))
      (node (ref "C62") (pin "1") (pinfunction "1_1") (pintype "input"))
      (node (ref "C63") (pin "2") (pinfunction "2_2") (pintype "input"))
      (node (ref "C64") (pin "1") (pinfunction "1_1") (pintype "unspecified"))
      (node (ref "C65") (pin "1") (pinfunction "1_1") (pintype "unspecified"))
      (node (ref "C66") (pin "1") (pinfunction "1_1") (pintype "input"))
      (node (ref "C67") (pin "1") (pinfunction "1_1") (pintype "input"))
      (node (ref "C68") (pin "2") (pinfunction "2_2") (pintype "input"))
      (node (ref "C69") (pin "1") (pinfunction "1_1") (pintype "input"))
      (node (ref "C70") (pin "1") (pinfunction "1_1") (pintype "input"))
      (node (ref "C71") (pin "2") (pinfunction "2_2") (pintype "unspecified"))
      (node (ref "C72") (pin "2") (pinfunction "2_2") (pintype "unspecified"))
      (node (ref "C73") (pin "2") (pinfunction "2_2") (pintype "unspecified"))
      (node (ref "C74") (pin "2") (pinfunction "2_2") (pintype "unspecified"))
      (node (ref "C75") (pin "2") (pinfunction "2_2") (pintype "unspecified"))
      (node (ref "C76") (pin "2") (pinfunction "2_2") (pintype "unspecified"))
      (node (ref "C77") (pin "2") (pinfunction "2_2") (pintype "unspecified"))
      (node (ref "C78") (pin "2") (pinfunction "2_2") (pintype "unspecified"))
      (node (ref "C79") (pin "1") (pinfunction "1_1") (pintype "input"))
      (node (ref "C80") (pin "1") (pinfunction "1_1") (pintype "input"))
      (node (ref "C82") (pin "1") (pinfunction "1_1") (pintype "unspecified"))
      (node (ref "C84") (pin "1") (pinfunction "1_1") (pintype "input"))
      (node (ref "C85") (pin "2") (pinfunction "2_2") (pintype "unspecified"))
      (node (ref "C86") (pin "1") (pinfunction "1_1") (pintype "input"))
      (node (ref "C87") (pin "1") (pinfunction "1_1") (pintype "input"))
      (node (ref "C88") (pin "1") (pinfunction "1_1") (pintype "input"))
      (node (ref "C89") (pin "1") (pinfunction "1_1") (pintype "input"))
      (node (ref "C9") (pin "2") (pinfunction "2_2") (pintype "unspecified"))
      (node (ref "C90") (pin "1") (pinfunction "1_1") (pintype "input"))
      (node (ref "C95") (pin "1") (pinfunction "1_1") (pintype "unspecified"))
      (node (ref "CARD1") (pin "10") (pinfunction "GND_10") (pintype "unspecified"))
      (node (ref "CARD1") (pin "11") (pinfunction "GND_11") (pintype "unspecified"))
      (node (ref "CARD1") (pin "12") (pinfunction "GND_12") (pintype "unspecified"))
      (node (ref "CARD1") (pin "13") (pinfunction "GND_13") (pintype "unspecified"))
      (node (ref "CARD1") (pin "6") (pinfunction "VSS_6") (pintype "unspecified"))
      (node (ref "CN2") (pin "1") (pinfunction "1_1") (pintype "unspecified"))
      (node (ref "CONTROL3") (pin "13") (pinfunction "13_13") (pintype "unspecified"))
      (node (ref "CONTROL3") (pin "14") (pinfunction "14_14") (pintype "unspecified"))
      (node (ref "CONTROL3") (pin "2") (pinfunction "2_2") (pintype "unspecified"))
      (node (ref "D4") (pin "2") (pinfunction "K_2") (pintype "unspecified"))
      (node (ref "FPC1") (pin "13") (pinfunction "13_13") (pintype "unspecified"))
      (node (ref "FPC1") (pin "15") (pinfunction "15_15") (pintype "unspecified"))
      (node (ref "FPC1") (pin "3") (pinfunction "3_3") (pintype "unspecified"))
      (node (ref "FPC1") (pin "46") (pinfunction "46_46") (pintype "unspecified"))
      (node (ref "FPC1") (pin "51") (pinfunction "51_51") (pintype "unspecified"))
      (node (ref "FPC1") (pin "52") (pinfunction "52_52") (pintype "unspecified"))
      (node (ref "FPC2") (pin "15") (pinfunction "15_15") (pintype "unspecified"))
      (node (ref "FPC2") (pin "16") (pinfunction "16_16") (pintype "unspecified"))
      (node (ref "FPC2") (pin "5") (pinfunction "5_5") (pintype "unspecified"))
      (node (ref "FPC6") (pin "29") (pinfunction "29_29") (pintype "unspecified"))
      (node (ref "FPC6") (pin "3") (pinfunction "3_3") (pintype "unspecified"))
      (node (ref "FPC6") (pin "36") (pinfunction "36_36") (pintype "unspecified"))
      (node (ref "FPC6") (pin "41") (pinfunction "41_41") (pintype "unspecified"))
      (node (ref "FPC6") (pin "42") (pinfunction "42_42") (pintype "unspecified"))
      (node (ref "G1") (pin "1") (pinfunction "1_1") (pintype "unspecified"))
      (node (ref "GND") (pin "1") (pinfunction "1_1") (pintype "unspecified"))
      (node (ref "GND,") (pin "1") (pinfunction "1_1") (pintype "unspecified"))
      (node (ref "GND1") (pin "1") (pinfunction "1_1") (pintype "unspecified"))
      (node (ref "GND2") (pin "1") (pinfunction "1_1") (pintype "unspecified"))
      (node (ref "GND3") (pin "1") (pinfunction "1_1") (pintype "unspecified"))
      (node (ref "GND4") (pin "1") (pinfunction "1_1") (pintype "unspecified"))
      (node (ref "GND5") (pin "1") (pinfunction "1_1") (pintype "unspecified"))
      (node (ref "GND6") (pin "1") (pinfunction "1_1") (pintype "unspecified"))
      (node (ref "H1") (pin "4") (pinfunction "4_4") (pintype "unspecified"))
      (node (ref "HDMI1") (pin "1") (pinfunction "1_1") (pintype "unspecified"))
      (node (ref "HDMI1") (pin "10") (pinfunction "10_10") (pintype "unspecified"))
      (node (ref "HDMI1") (pin "13") (pinfunction "13_13") (pintype "unspecified"))
      (node (ref "HDMI1") (pin "16") (pinfunction "16_16") (pintype "unspecified"))
      (node (ref "HDMI1") (pin "19") (pinfunction "19_19") (pintype "unspecified"))
      (node (ref "HDMI1") (pin "21") (pinfunction "21_21") (pintype "unspecified"))
      (node (ref "HDMI1") (pin "22") (pinfunction "22_22") (pintype "unspecified"))
      (node (ref "HDMI1") (pin "4") (pinfunction "4_4") (pintype "unspecified"))
      (node (ref "IC1") (pin "11") (pinfunction "GND_11") (pintype "bidirectional"))
      (node (ref "IC1") (pin "129") (pinfunction "EP_129") (pintype "bidirectional"))
      (node (ref "IC1") (pin "38") (pinfunction "ADC_GND/VADC_GND_38") (pintype "bidirectional"))
      (node (ref "IC1") (pin "61") (pinfunction "GNDK_61") (pintype "bidirectional"))
      (node (ref "IC1") (pin "85") (pinfunction "PGND_1_85") (pintype "bidirectional"))
      (node (ref "J13") (pin "0") (pinfunction "SH_0") (pintype "unspecified"))
      (node (ref "J13") (pin "1") (pinfunction "SH_1") (pintype "unspecified"))
      (node (ref "J13") (pin "2") (pinfunction "SH_2") (pintype "unspecified"))
      (node (ref "J13") (pin "3") (pinfunction "SH_3") (pintype "unspecified"))
      (node (ref "J13") (pin "A1") (pinfunction "GND_A1") (pintype "unspecified"))
      (node (ref "J13") (pin "A12") (pinfunction "GND_A12") (pintype "unspecified"))
      (node (ref "J13") (pin "B1") (pinfunction "GND_B1") (pintype "unspecified"))
      (node (ref "J13") (pin "B12") (pinfunction "GND_B12") (pintype "unspecified"))
      (node (ref "J15") (pin "2") (pinfunction "2_2") (pintype "input"))
      (node (ref "LEFT-1") (pin "17") (pinfunction "17_17") (pintype "unspecified"))
      (node (ref "LEFT-1") (pin "18") (pinfunction "18_18") (pintype "unspecified"))
      (node (ref "LEFT-1") (pin "4") (pinfunction "4_4") (pintype "unspecified"))
      (node (ref "O1") (pin "1") (pinfunction "1_1") (pintype "unspecified"))
      (node (ref "O2") (pin "1") (pinfunction "1_1") (pintype "unspecified"))
      (node (ref "O3") (pin "1") (pinfunction "1_1") (pintype "unspecified"))
      (node (ref "O4") (pin "1") (pinfunction "1_1") (pintype "unspecified"))
      (node (ref "PS2") (pin "16") (pinfunction "16_16") (pintype "unspecified"))
      (node (ref "PS2") (pin "18") (pinfunction "18_18") (pintype "unspecified"))
      (node (ref "PS2") (pin "20") (pinfunction "20_20") (pintype "unspecified"))
      (node (ref "PS2") (pin "22") (pinfunction "22_22") (pintype "unspecified"))
      (node (ref "PS2") (pin "24") (pinfunction "24_24") (pintype "unspecified"))
      (node (ref "PS2") (pin "26") (pinfunction "26_26") (pintype "unspecified"))
      (node (ref "PS2") (pin "28") (pinfunction "28_28") (pintype "unspecified"))
      (node (ref "PS2") (pin "31") (pinfunction "31_31") (pintype "unspecified"))
      (node (ref "PS2") (pin "32") (pinfunction "32_32") (pintype "unspecified"))
      (node (ref "PS2") (pin "9") (pinfunction "9_9") (pintype "unspecified"))
      (node (ref "Q1") (pin "2") (pinfunction "E_2") (pintype "unspecified"))
      (node (ref "Q3") (pin "2") (pinfunction "E_2") (pintype "unspecified"))
      (node (ref "Q5") (pin "2") (pinfunction "E_2") (pintype "unspecified"))
      (node (ref "Q6") (pin "2") (pinfunction "E_2") (pintype "unspecified"))
      (node (ref "R1.") (pin "1") (pinfunction "1_1") (pintype "input"))
      (node (ref "R122") (pin "1") (pinfunction "1_1") (pintype "unspecified"))
      (node (ref "R15") (pin "2") (pinfunction "2_2") (pintype "unspecified"))
      (node (ref "R236") (pin "1") (pinfunction "1_1") (pintype "unspecified"))
      (node (ref "R3.") (pin "1") (pinfunction "1_1") (pintype "unspecified"))
      (node (ref "R33") (pin "1") (pinfunction "1_1") (pintype "unspecified"))
      (node (ref "R39") (pin "2") (pinfunction "2_2") (pintype "unspecified"))
      (node (ref "R42") (pin "1") (pinfunction "1_1") (pintype "input"))
      (node (ref "R48") (pin "1") (pinfunction "1_1") (pintype "input"))
      (node (ref "R56") (pin "1") (pinfunction "1_1") (pintype "unspecified"))
      (node (ref "R58") (pin "1") (pinfunction "1_1") (pintype "unspecified"))
      (node (ref "R59") (pin "1") (pinfunction "1_1") (pintype "unspecified"))
      (node (ref "R6") (pin "1") (pinfunction "1_1") (pintype "input"))
      (node (ref "R60") (pin "2") (pinfunction "2_2") (pintype "input"))
      (node (ref "R65") (pin "2") (pinfunction "2_2") (pintype "unspecified"))
      (node (ref "R76") (pin "1") (pinfunction "1_1") (pintype "input"))
      (node (ref "R79") (pin "1") (pinfunction "1_1") (pintype "unspecified"))
      (node (ref "R8") (pin "1") (pinfunction "1_1") (pintype "unspecified"))
      (node (ref "R80") (pin "2") (pinfunction "2_2") (pintype "input"))
      (node (ref "R85") (pin "1") (pinfunction "1_1") (pintype "unspecified"))
      (node (ref "RIGHT-1") (pin "21") (pinfunction "21_21") (pintype "unspecified"))
      (node (ref "RIGHT-1") (pin "22") (pinfunction "22_22") (pintype "unspecified"))
      (node (ref "RIGHT-1") (pin "8") (pinfunction "8_8") (pintype "unspecified"))
      (node (ref "SW1") (pin "3") (pinfunction "3_3") (pintype "unspecified"))
      (node (ref "SW1") (pin "4") (pinfunction "4_4") (pintype "unspecified"))
      (node (ref "SW2") (pin "3") (pinfunction "3_3") (pintype "unspecified"))
      (node (ref "SW2") (pin "4") (pinfunction "4_4") (pintype "unspecified"))
      (node (ref "SW3") (pin "3") (pinfunction "3_3") (pintype "unspecified"))
      (node (ref "SW3") (pin "4") (pinfunction "4_4") (pintype "unspecified"))
      (node (ref "U1") (pin "4") (pinfunction "GND_4") (pintype "unspecified"))
      (node (ref "U10") (pin "4") (pinfunction "VSS_4") (pintype "unspecified"))
      (node (ref "U11") (pin "2") (pinfunction "GND_2") (pintype "unspecified"))
      (node (ref "U12") (pin "4") (pinfunction "GND_4") (pintype "unspecified"))
      (node (ref "U13") (pin "19") (pinfunction "TESTEN_19") (pintype "unspecified"))
      (node (ref "U13") (pin "57") (pinfunction "GND_57") (pintype "bidirectional"))
      (node (ref "U2") (pin "2") (pinfunction "GND_2") (pintype "unspecified"))
      (node (ref "U3") (pin "1") (pinfunction "GND_1") (pintype "unspecified"))
      (node (ref "U4") (pin "1") (pinfunction "GND/ADJ_1") (pintype "unspecified"))
      (node (ref "U5") (pin "23") (pinfunction "VSS_1_23") (pintype "unspecified"))
      (node (ref "U5") (pin "35") (pinfunction "VSS_2_35") (pintype "unspecified"))
      (node (ref "U5") (pin "47") (pinfunction "VSS_3_47") (pintype "unspecified"))
      (node (ref "U5") (pin "8") (pinfunction "VSSA_8") (pintype "unspecified"))
      (node (ref "U6") (pin "5") (pinfunction "5_5") (pintype "unspecified"))
      (node (ref "U6") (pin "6") (pinfunction "6_6") (pintype "unspecified"))
      (node (ref "U7") (pin "4") (pinfunction "GND_4") (pintype "unspecified"))
      (node (ref "U8") (pin "4") (pinfunction "VSS_4") (pintype "unspecified"))
      (node (ref "U9") (pin "12") (pinfunction "GND_12") (pintype "unspecified"))
      (node (ref "U9") (pin "5") (pinfunction "GND_5") (pintype "unspecified"))
      (node (ref "U9") (pin "8") (pinfunction "VOLMAX_8") (pintype "unspecified"))
      (node (ref "X1") (pin "2") (pinfunction "GND_2") (pintype "unspecified"))
      (node (ref "X1") (pin "4") (pinfunction "GND_4") (pintype "unspecified"))
      (node (ref "X3") (pin "2") (pinfunction "GND_2") (pintype "input"))
      (node (ref "X3") (pin "4") (pinfunction "GND_4") (pintype "input"))
      (node (ref "Y1") (pin "2") (pinfunction "GND_2") (pintype "unspecified"))
      (node (ref "Y1") (pin "4") (pinfunction "GND_4") (pintype "unspecified"))
    )
    (net (code "84") (name "GO") (class "Default")
      (node (ref "G") (pin "1") (pinfunction "1_1") (pintype "unspecified"))
      (node (ref "L4") (pin "2") (pinfunction "2_2") (pintype "unspecified"))
      (node (ref "PS2") (pin "23") (pinfunction "23_23") (pintype "unspecified"))
    )
    (net (code "85") (name "HSYNC") (class "Default")
      (node (ref "HS1") (pin "1") (pinfunction "1_1") (pintype "unspecified"))
      (node (ref "PS2") (pin "2") (pinfunction "2_2") (pintype "unspecified"))
      (node (ref "R57") (pin "1") (pinfunction "1_1") (pintype "unspecified"))
      (node (ref "R58") (pin "2") (pinfunction "2_2") (pintype "unspecified"))
    )
    (net (code "86") (name "Home") (class "Default")
      (node (ref "HOME") (pin "1") (pinfunction "1_1") (pintype "unspecified"))
      (node (ref "RIGHT-1") (pin "14") (pinfunction "14_14") (pintype "unspecified"))
      (node (ref "U5") (pin "3") (pinfunction "PC14-OSC32_IN_3") (pintype "unspecified"))
    )
    (net (code "87") (name "L") (class "Default")
      (node (ref "C81") (pin "2") (pinfunction "2_2") (pintype "unspecified"))
      (node (ref "L-IN1") (pin "1") (pinfunction "1_1") (pintype "unspecified"))
      (node (ref "PS2") (pin "17") (pinfunction "17_17") (pintype "unspecified"))
    )
    (net (code "88") (name "L+") (class "Default")
      (node (ref "C47") (pin "1") (pinfunction "1_1") (pintype "input"))
      (node (ref "C73") (pin "1") (pinfunction "1_1") (pintype "unspecified"))
      (node (ref "L+") (pin "1") (pinfunction "1_1") (pintype "unspecified"))
      (node (ref "L100") (pin "2") (pinfunction "2_2") (pintype "unspecified"))
    )
    (net (code "89") (name "L1") (class "Default")
      (node (ref "L/1") (pin "1") (pinfunction "1_1") (pintype "unspecified"))
      (node (ref "LEFT-1") (pin "8") (pinfunction "8_8") (pintype "unspecified"))
      (node (ref "U5") (pin "38") (pinfunction "PA15_38") (pintype "unspecified"))
    )
    (net (code "90") (name "L2") (class "Default")
      (node (ref "L/2") (pin "1") (pinfunction "1_1") (pintype "unspecified"))
      (node (ref "LEFT-1") (pin "9") (pinfunction "9_9") (pintype "unspecified"))
      (node (ref "U5") (pin "31") (pinfunction "PA10_31") (pintype "unspecified"))
    )
    (net (code "91") (name "L3") (class "Default")
      (node (ref "L/3") (pin "1") (pinfunction "1_1") (pintype "unspecified"))
      (node (ref "LEFT-1") (pin "10") (pinfunction "10_10") (pintype "unspecified"))
      (node (ref "U5") (pin "30") (pinfunction "PA9_30") (pintype "unspecified"))
    )
    (net (code "92") (name "LB") (class "Default")
      (node (ref "FPC2") (pin "11") (pinfunction "11_11") (pintype "unspecified"))
      (node (ref "PS2") (pin "10") (pinfunction "10_10") (pintype "unspecified"))
      (node (ref "RIGHT-1") (pin "5") (pinfunction "5_5") (pintype "unspecified"))
    )
    (net (code "93") (name "LG") (class "Default")
      (node (ref "FPC2") (pin "10") (pinfunction "10_10") (pintype "unspecified"))
      (node (ref "PS2") (pin "11") (pinfunction "11_11") (pintype "unspecified"))
      (node (ref "RIGHT-1") (pin "4") (pinfunction "4_4") (pintype "unspecified"))
    )
    (net (code "94") (name "LR") (class "Default")
      (node (ref "FPC2") (pin "9") (pinfunction "9_9") (pintype "unspecified"))
      (node (ref "PS2") (pin "12") (pinfunction "12_12") (pintype "unspecified"))
      (node (ref "RIGHT-1") (pin "3") (pinfunction "3_3") (pintype "unspecified"))
    )
    (net (code "95") (name "LX") (class "Default")
      (node (ref "LEFT-1") (pin "16") (pinfunction "16_16") (pintype "unspecified"))
      (node (ref "LX") (pin "1") (pinfunction "1_1") (pintype "unspecified"))
      (node (ref "U5") (pin "11") (pinfunction "PA1_11") (pintype "unspecified"))
    )
    (net (code "96") (name "LY") (class "Default")
      (node (ref "LEFT-1") (pin "15") (pinfunction "15_15") (pintype "unspecified"))
      (node (ref "LY") (pin "1") (pinfunction "1_1") (pintype "unspecified"))
      (node (ref "U5") (pin "12") (pinfunction "PA2_12") (pintype "unspecified"))
    )
    (net (code "97") (name "Left") (class "Default")
      (node (ref "LEFT") (pin "1") (pinfunction "1_1") (pintype "unspecified"))
      (node (ref "LEFT-1") (pin "13") (pinfunction "13_13") (pintype "unspecified"))
      (node (ref "U5") (pin "15") (pinfunction "PA5_15") (pintype "unspecified"))
    )
    (net (code "98") (name "MENU") (class "Default")
      (node (ref "FPC2") (pin "4") (pinfunction "4_4") (pintype "unspecified"))
      (node (ref "MN") (pin "1") (pinfunction "1_1") (pintype "unspecified"))
      (node (ref "R26") (pin "2") (pinfunction "2_2") (pintype "unspecified"))
    )
    (net (code "99") (name "Net-(40P-Pad2)") (class "Default")
      (node (ref "40P") (pin "2") (pinfunction "2_2") (pintype "input"))
      (node (ref "R78") (pin "2") (pinfunction "2_2") (pintype "unspecified"))
      (node (ref "R79") (pin "2") (pinfunction "2_2") (pintype "unspecified"))
    )
    (net (code "100") (name "Net-(C1-Pad2)") (class "Default")
      (node (ref "C1") (pin "2") (pinfunction "2_2") (pintype "unspecified"))
      (node (ref "L4") (pin "1") (pinfunction "1_1") (pintype "unspecified"))
      (node (ref "R4") (pin "1") (pinfunction "1_1") (pintype "input"))
      (node (ref "R5") (pin "1") (pinfunction "1_1") (pintype "unspecified"))
      (node (ref "R6") (pin "2") (pinfunction "2_2") (pintype "input"))
    )
    (net (code "101") (name "Net-(C2-Pad1)") (class "Default")
      (node (ref "C2") (pin "1") (pinfunction "1_1") (pintype "unspecified"))
      (node (ref "L3.") (pin "1") (pinfunction "1_1") (pintype "unspecified"))
      (node (ref "R1.") (pin "2") (pinfunction "2_2") (pintype "input"))
      (node (ref "R2.") (pin "1") (pinfunction "1_1") (pintype "unspecified"))
    )
    (net (code "102") (name "Net-(C3-Pad1)") (class "Default")
      (node (ref "C3") (pin "1") (pinfunction "1_1") (pintype "input"))
      (node (ref "R2.") (pin "2") (pinfunction "2_2") (pintype "unspecified"))
    )
    (net (code "103") (name "Net-(C4-Pad1)") (class "Default")
      (node (ref "C4") (pin "1") (pinfunction "1_1") (pintype "input"))
      (node (ref "R3.") (pin "2") (pinfunction "2_2") (pintype "unspecified"))
    )
    (net (code "104") (name "Net-(C5-Pad1)") (class "Default")
      (node (ref "C5") (pin "1") (pinfunction "1_1") (pintype "unspecified"))
      (node (ref "R4") (pin "2") (pinfunction "2_2") (pintype "input"))
    )
    (net (code "105") (name "Net-(C6-Pad1)") (class "Default")
      (node (ref "C6") (pin "1") (pinfunction "1_1") (pintype "input"))
      (node (ref "R5") (pin "2") (pinfunction "2_2") (pintype "unspecified"))
    )
    (net (code "106") (name "Net-(C7-Pad1)") (class "Default")
      (node (ref "C7") (pin "1") (pinfunction "1_1") (pintype "input"))
      (node (ref "R8") (pin "2") (pinfunction "2_2") (pintype "unspecified"))
    )
    (net (code "107") (name "Net-(C8-Pad1)") (class "Default")
      (node (ref "C8") (pin "1") (pinfunction "1_1") (pintype "input"))
      (node (ref "R7") (pin "2") (pinfunction "2_2") (pintype "unspecified"))
    )
    (net (code "108") (name "Net-(C9-Pad1)") (class "Default")
      (node (ref "C9") (pin "1") (pinfunction "1_1") (pintype "unspecified"))
      (node (ref "L9") (pin "1") (pinfunction "1_1") (pintype "unspecified"))
      (node (ref "R60") (pin "1") (pinfunction "1_1") (pintype "input"))
      (node (ref "R7") (pin "1") (pinfunction "1_1") (pintype "unspecified"))
    )
    (net (code "109") (name "Net-(C10-Pad1)") (class "Default")
      (node (ref "C10") (pin "1") (pinfunction "1_1") (pintype "input"))
      (node (ref "R59") (pin "2") (pinfunction "2_2") (pintype "unspecified"))
    )
    (net (code "110") (name "Net-(C27-Pad1)") (class "Default")
      (node (ref "C27") (pin "1") (pinfunction "1_1") (pintype "input"))
      (node (ref "PW") (pin "1") (pinfunction "1_1") (pintype "unspecified"))
      (node (ref "R26") (pin "1") (pinfunction "1_1") (pintype "unspecified"))
      (node (ref "R32") (pin "1") (pinfunction "1_1") (pintype "unspecified"))
      (node (ref "R34") (pin "1") (pinfunction "1_1") (pintype "input"))
      (node (ref "R35") (pin "1") (pinfunction "1_1") (pintype "unspecified"))
      (node (ref "R36") (pin "2") (pinfunction "2_2") (pintype "unspecified"))
      (node (ref "R37") (pin "2") (pinfunction "2_2") (pintype "unspecified"))
    )
    (net (code "111") (name "Net-(C29-Pad1)") (class "Default")
      (node (ref "C29") (pin "1") (pinfunction "1_1") (pintype "input"))
      (node (ref "R40") (pin "1") (pinfunction "1_1") (pintype "input"))
      (node (ref "VCC1") (pin "1") (pinfunction "1_1") (pintype "unspecified"))
    )
    (net (code "112") (name "Net-(C33-Pad2)") (class "Default")
      (node (ref "C33") (pin "2") (pinfunction "2_2") (pintype "input"))
      (node (ref "C34") (pin "2") (pinfunction "2_2") (pintype "input"))
      (node (ref "C37") (pin "2") (pinfunction "2_2") (pintype "input"))
      (node (ref "R42") (pin "2") (pinfunction "2_2") (pintype "input"))
      (node (ref "R45") (pin "1") (pinfunction "1_1") (pintype "unspecified"))
    )
    (net (code "113") (name "Net-(C34-Pad1)") (class "Default")
      (node (ref "C34") (pin "1") (pinfunction "1_1") (pintype "input"))
      (node (ref "C35") (pin "2") (pinfunction "2_2") (pintype "input"))
      (node (ref "L2.") (pin "1") (pinfunction "1_1") (pintype "unspecified"))
    )
    (net (code "114") (name "Net-(C37-Pad1)") (class "Default")
      (node (ref "C37") (pin "1") (pinfunction "1_1") (pintype "input"))
      (node (ref "L2.") (pin "2") (pinfunction "2_2") (pintype "unspecified"))
      (node (ref "R46") (pin "1") (pinfunction "1_1") (pintype "input"))
    )
    (net (code "115") (name "Net-(C38-Pad2)") (class "Default")
      (node (ref "C38") (pin "2") (pinfunction "2_2") (pintype "input"))
      (node (ref "R44") (pin "2") (pinfunction "2_2") (pintype "unspecified"))
      (node (ref "R47") (pin "1") (pinfunction "1_1") (pintype "unspecified"))
    )
    (net (code "116") (name "Net-(C44-Pad2)") (class "Default")
      (node (ref "C44") (pin "2") (pinfunction "2_2") (pintype "input"))
      (node (ref "CN2") (pin "3") (pinfunction "3_3") (pintype "unspecified"))
      (node (ref "R122") (pin "2") (pinfunction "2_2") (pintype "unspecified"))
    )
    (net (code "117") (name "Net-(C45-Pad1)") (class "Default")
      (node (ref "C45") (pin "1") (pinfunction "1_1") (pintype "input"))
      (node (ref "C46") (pin "1") (pinfunction "1_1") (pintype "input"))
    )
    (net (code "118") (name "Net-(C47-Pad2)") (class "Default")
      (node (ref "C47") (pin "2") (pinfunction "2_2") (pintype "input"))
      (node (ref "CN2") (pin "2") (pinfunction "2_2") (pintype "unspecified"))
      (node (ref "R236") (pin "2") (pinfunction "2_2") (pintype "unspecified"))
    )
    (net (code "119") (name "Net-(C71-Pad1)") (class "Default")
      (node (ref "C71") (pin "1") (pinfunction "1_1") (pintype "unspecified"))
      (node (ref "L80") (pin "2") (pinfunction "2_2") (pintype "unspecified"))
      (node (ref "R-") (pin "1") (pinfunction "1_1") (pintype "unspecified"))
    )
    (net (code "120") (name "Net-(C75-Pad1)") (class "Default")
      (node (ref "C75") (pin "1") (pinfunction "1_1") (pintype "unspecified"))
      (node (ref "L-") (pin "1") (pinfunction "1_1") (pintype "unspecified"))
      (node (ref "L110") (pin "2") (pinfunction "2_2") (pintype "unspecified"))
    )
    (net (code "121") (name "Net-(D+-Pad1)") (class "Default")
      (node (ref "D+") (pin "1") (pinfunction "1_1") (pintype "unspecified"))
      (node (ref "R63") (pin "1") (pinfunction "1_1") (pintype "input"))
    )
    (net (code "122") (name "Net-(D--Pad1)") (class "Default")
      (node (ref "D-") (pin "1") (pinfunction "1_1") (pintype "unspecified"))
      (node (ref "R61") (pin "1") (pinfunction "1_1") (pintype "input"))
    )
    (net (code "123") (name "Net-(D3-COM)") (class "Default")
      (node (ref "C13") (pin "2") (pinfunction "2_2") (pintype "input"))
      (node (ref "D3") (pin "3") (pinfunction "COM_3") (pintype "unspecified"))
    )
    (net (code "124") (name "Net-(D3-K)") (class "Default")
      (node (ref "D3") (pin "2") (pinfunction "K_2") (pintype "unspecified"))
      (node (ref "R84") (pin "1") (pinfunction "1_1") (pintype "unspecified"))
    )
    (net (code "125") (name "Net-(D4-A)") (class "Default")
      (node (ref "D4") (pin "1") (pinfunction "A_1") (pintype "unspecified"))
      (node (ref "R83") (pin "1") (pinfunction "1_1") (pintype "unspecified"))
    )
    (net (code "126") (name "Net-(D4-COM)") (class "Default")
      (node (ref "C14") (pin "1") (pinfunction "1_1") (pintype "input"))
      (node (ref "D4") (pin "3") (pinfunction "COM_3") (pintype "unspecified"))
    )
    (net (code "127") (name "Net-(D5-Pad1)") (class "Default")
      (node (ref "D5") (pin "1") (pinfunction "1_1") (pintype "unspecified"))
      (node (ref "R68") (pin "1") (pinfunction "1_1") (pintype "unspecified"))
    )
    (net (code "128") (name "Net-(D6-Pad1)") (class "Default")
      (node (ref "D6") (pin "1") (pinfunction "1_1") (pintype "unspecified"))
      (node (ref "R65") (pin "1") (pinfunction "1_1") (pintype "unspecified"))
    )
    (net (code "129") (name "Net-(D9-K)") (class "Default")
      (node (ref "C64") (pin "2") (pinfunction "2_2") (pintype "unspecified"))
      (node (ref "C65") (pin "2") (pinfunction "2_2") (pintype "unspecified"))
      (node (ref "C95") (pin "2") (pinfunction "2_2") (pintype "unspecified"))
      (node (ref "D9") (pin "1") (pinfunction "K_1") (pintype "unspecified"))
      (node (ref "U11") (pin "1") (pinfunction "VIN_1") (pintype "unspecified"))
      (node (ref "U11") (pin "3") (pinfunction "EN_3") (pintype "unspecified"))
    )
    (net (code "130") (name "Net-(FPC1-Pad4)") (class "Default")
      (node (ref "FPC1") (pin "4") (pinfunction "4_4") (pintype "unspecified"))
      (node (ref "J15") (pin "1") (pinfunction "1_1") (pintype "input"))
      (node (ref "R77") (pin "1") (pinfunction "1_1") (pintype "unspecified"))
    )
    (net (code "131") (name "Net-(FPC6-Pad32)") (class "Default")
      (node (ref "FPC6") (pin "32") (pinfunction "32_32") (pintype "unspecified"))
      (node (ref "HS") (pin "2") (pinfunction "2_2") (pintype "input"))
    )
    (net (code "132") (name "Net-(FPC6-Pad33)") (class "Default")
      (node (ref "FPC6") (pin "33") (pinfunction "33_33") (pintype "unspecified"))
      (node (ref "VS") (pin "2") (pinfunction "2_2") (pintype "input"))
    )
    (net (code "133") (name "Net-(IC1-A-ADC0{slash}AVOUT{slash}VCLK{slash}GPIO)") (class "Default")
      (node (ref "C26") (pin "1") (pinfunction "1_1") (pintype "input"))
      (node (ref "IC1") (pin "50") (pinfunction "A-ADC0/AVOUT/VCLK/GPIO_50") (pintype "bidirectional"))
      (node (ref "R43") (pin "1") (pinfunction "1_1") (pintype "unspecified"))
      (node (ref "R48") (pin "2") (pinfunction "2_2") (pintype "input"))
    )
    (net (code "134") (name "Net-(IC1-A-ADC2{slash}GPIO)") (class "Default")
      (node (ref "IC1") (pin "52") (pinfunction "A-ADC2/GPIO_52") (pintype "bidirectional"))
      (node (ref "R22") (pin "1") (pinfunction "1_1") (pintype "unspecified"))
    )
    (net (code "135") (name "Net-(IC1-A-ADC3{slash}GPIO)") (class "Default")
      (node (ref "IC1") (pin "53") (pinfunction "A-ADC3/GPIO_53") (pintype "bidirectional"))
      (node (ref "R37") (pin "1") (pinfunction "1_1") (pintype "unspecified"))
    )
    (net (code "136") (name "Net-(IC1-AHS0)") (class "Default")
      (node (ref "IC1") (pin "22") (pinfunction "AHS0_22") (pintype "bidirectional"))
      (node (ref "R57") (pin "2") (pinfunction "2_2") (pintype "unspecified"))
    )
    (net (code "137") (name "Net-(IC1-AVS0)") (class "Default")
      (node (ref "IC1") (pin "21") (pinfunction "AVS0_21") (pintype "bidirectional"))
      (node (ref "R55") (pin "2") (pinfunction "2_2") (pintype "unspecified"))
    )
    (net (code "138") (name "Net-(IC1-B-ADC1{slash}IICSCL{slash}GPIO)") (class "Default")
      (node (ref "IC1") (pin "56") (pinfunction "B-ADC1/IICSCL/GPIO_56") (pintype "bidirectional"))
      (node (ref "R31") (pin "2") (pinfunction "2_2") (pintype "unspecified"))
    )
    (net (code "139") (name "Net-(IC1-B-ADC2{slash}IICSDA{slash}GPIO)") (class "Default")
      (node (ref "IC1") (pin "57") (pinfunction "B-ADC2/IICSDA/GPIO_57") (pintype "bidirectional"))
      (node (ref "R30") (pin "2") (pinfunction "2_2") (pintype "unspecified"))
    )
    (net (code "140") (name "Net-(IC1-B0+)") (class "Default")
      (node (ref "C8") (pin "2") (pinfunction "2_2") (pintype "input"))
      (node (ref "IC1") (pin "25") (pinfunction "B0+_25") (pintype "bidirectional"))
    )
    (net (code "141") (name "Net-(IC1-B0-)") (class "Default")
      (node (ref "C10") (pin "2") (pinfunction "2_2") (pintype "input"))
      (node (ref "IC1") (pin "24") (pinfunction "B0-_24") (pintype "bidirectional"))
    )
    (net (code "142") (name "Net-(IC1-CEB{slash}IRQB)") (class "Default")
      (node (ref "IC1") (pin "118") (pinfunction "CEB/IRQB_118") (pintype "bidirectional"))
      (node (ref "R11") (pin "2") (pinfunction "2_2") (pintype "unspecified"))
      (node (ref "R15") (pin "1") (pinfunction "1_1") (pintype "unspecified"))
    )
    (net (code "143") (name "Net-(IC1-DDCSCL1{slash}GPIO)") (class "Default")
      (node (ref "IC1") (pin "58") (pinfunction "DDCSCL1/GPIO_58") (pintype "bidirectional"))
      (node (ref "R10") (pin "2") (pinfunction "2_2") (pintype "unspecified"))
      (node (ref "R24") (pin "1") (pinfunction "1_1") (pintype "unspecified"))
    )
    (net (code "144") (name "Net-(IC1-DDCSCL2{slash}GPIO)") (class "Default")
      (node (ref "IC1") (pin "124") (pinfunction "DDCSCL2/GPIO_124") (pintype "bidirectional"))
      (node (ref "R50") (pin "2") (pinfunction "2_2") (pintype "unspecified"))
    )
    (net (code "145") (name "Net-(IC1-DDCSDA1{slash}GPIO)") (class "Default")
      (node (ref "IC1") (pin "59") (pinfunction "DDCSDA1/GPIO_59") (pintype "bidirectional"))
      (node (ref "R23") (pin "1") (pinfunction "1_1") (pintype "unspecified"))
      (node (ref "R28") (pin "2") (pinfunction "2_2") (pintype "unspecified"))
    )
    (net (code "146") (name "Net-(IC1-DDCSDA2{slash}GPIO)") (class "Default")
      (node (ref "IC1") (pin "123") (pinfunction "DDCSDA2/GPIO_123") (pintype "bidirectional"))
      (node (ref "R49") (pin "2") (pinfunction "2_2") (pintype "unspecified"))
    )
    (net (code "147") (name "Net-(IC1-G0+)") (class "Default")
      (node (ref "C6") (pin "2") (pinfunction "2_2") (pintype "input"))
      (node (ref "IC1") (pin "27") (pinfunction "G0+_27") (pintype "bidirectional"))
    )
    (net (code "148") (name "Net-(IC1-G0-)") (class "Default")
      (node (ref "C7") (pin "2") (pinfunction "2_2") (pintype "input"))
      (node (ref "IC1") (pin "26") (pinfunction "G0-_26") (pintype "bidirectional"))
    )
    (net (code "149") (name "Net-(IC1-GPIO{slash}PWM2)") (class "Default")
      (node (ref "IC1") (pin "98") (pinfunction "GPIO/PWM2_98") (pintype "bidirectional"))
      (node (ref "R19") (pin "1") (pinfunction "1_1") (pintype "unspecified"))
      (node (ref "R20") (pin "2") (pinfunction "2_2") (pintype "unspecified"))
    )
    (net (code "150") (name "Net-(IC1-NC_1)") (class "Default")
      (node (ref "IC1") (pin "2") (pinfunction "NC_1_2") (pintype "bidirectional"))
      (node (ref "R16") (pin "2") (pinfunction "2_2") (pintype "unspecified"))
    )
    (net (code "151") (name "Net-(IC1-PVCC_1)") (class "Default")
      (node (ref "C16") (pin "2") (pinfunction "2_2") (pintype "input"))
      (node (ref "C19") (pin "1") (pinfunction "1_1") (pintype "unspecified"))
      (node (ref "C20") (pin "2") (pinfunction "2_2") (pintype "input"))
      (node (ref "C21") (pin "1") (pinfunction "1_1") (pintype "input"))
      (node (ref "C22") (pin "1") (pinfunction "1_1") (pintype "input"))
      (node (ref "IC1") (pin "1") (pinfunction "VDD_1_1") (pintype "bidirectional"))
      (node (ref "IC1") (pin "106") (pinfunction "PVCC_3_106") (pintype "bidirectional"))
      (node (ref "IC1") (pin "20") (pinfunction "VDD_2_20") (pintype "bidirectional"))
      (node (ref "IC1") (pin "49") (pinfunction "VADC_VDD_49") (pintype "bidirectional"))
      (node (ref "IC1") (pin "62") (pinfunction "PVCC_1_62") (pintype "bidirectional"))
      (node (ref "IC1") (pin "84") (pinfunction "PVCC_2_84") (pintype "bidirectional"))
      (node (ref "L12") (pin "2") (pinfunction "2_2") (pintype "unspecified"))
      (node (ref "R16") (pin "1") (pinfunction "1_1") (pintype "unspecified"))
      (node (ref "R72") (pin "2") (pinfunction "2_2") (pintype "unspecified"))
    )
    (net (code "152") (name "Net-(IC1-R0+)") (class "Default")
      (node (ref "C3") (pin "2") (pinfunction "2_2") (pintype "input"))
      (node (ref "IC1") (pin "30") (pinfunction "R0+_30") (pintype "bidirectional"))
    )
    (net (code "153") (name "Net-(IC1-R0-)") (class "Default")
      (node (ref "C4") (pin "2") (pinfunction "2_2") (pintype "input"))
      (node (ref "IC1") (pin "29") (pinfunction "R0-_29") (pintype "bidirectional"))
    )
    (net (code "154") (name "Net-(IC1-RESETB)") (class "Default")
      (node (ref "IC1") (pin "125") (pinfunction "RESETB_125") (pintype "bidirectional"))
      (node (ref "R51") (pin "1") (pinfunction "1_1") (pintype "unspecified"))
    )
    (net (code "155") (name "Net-(IC1-SI{slash}MCU_SCLK)") (class "Default")
      (node (ref "IC1") (pin "116") (pinfunction "SI/MCU_SCLK_116") (pintype "bidirectional"))
      (node (ref "R13") (pin "2") (pinfunction "2_2") (pintype "unspecified"))
    )
    (net (code "156") (name "Net-(IC1-SOG0)") (class "Default")
      (node (ref "C5") (pin "2") (pinfunction "2_2") (pintype "unspecified"))
      (node (ref "IC1") (pin "28") (pinfunction "SOG0_28") (pintype "bidirectional"))
    )
    (net (code "157") (name "Net-(IC1-SO{slash}SCSB)") (class "Default")
      (node (ref "IC1") (pin "117") (pinfunction "SO/SCSB_117") (pintype "bidirectional"))
      (node (ref "R12") (pin "2") (pinfunction "2_2") (pintype "unspecified"))
    )
    (net (code "158") (name "Net-(IC1-SPI_SCLK{slash}SDIO)") (class "Default")
      (node (ref "IC1") (pin "115") (pinfunction "SPI_SCLK/SDIO_115") (pintype "bidirectional"))
      (node (ref "R14") (pin "2") (pinfunction "2_2") (pintype "unspecified"))
    )
    (net (code "159") (name "Net-(IC1-V8_4{slash}VIN-1)") (class "Default")
      (node (ref "C33") (pin "1") (pinfunction "1_1") (pintype "input"))
      (node (ref "IC1") (pin "44") (pinfunction "V8_4/VIN-1_44") (pintype "bidirectional"))
    )
    (net (code "160") (name "Net-(IC1-V8_5{slash}VIN+1)") (class "Default")
      (node (ref "C35") (pin "1") (pinfunction "1_1") (pintype "input"))
      (node (ref "IC1") (pin "43") (pinfunction "V8_5/VIN+1_43") (pintype "bidirectional"))
    )
    (net (code "161") (name "Net-(IC1-WS{slash}TCON[7][1]{slash}GPIO{slash}PWM1)") (class "Default")
      (node (ref "IC1") (pin "65") (pinfunction "WS/TCON[7][1]/GPIO/PWM1_65") (pintype "bidirectional"))
      (node (ref "R21") (pin "1") (pinfunction "1_1") (pintype "unspecified"))
    )
    (net (code "162") (name "Net-(IC1-XI)") (class "Default")
      (node (ref "C11") (pin "1") (pinfunction "1_1") (pintype "input"))
      (node (ref "IC1") (pin "128") (pinfunction "XI_128") (pintype "bidirectional"))
      (node (ref "R52") (pin "2") (pinfunction "2_2") (pintype "unspecified"))
      (node (ref "X1") (pin "3") (pinfunction "OSC2_3") (pintype "unspecified"))
    )
    (net (code "163") (name "Net-(IC1-XO)") (class "Default")
      (node (ref "C39") (pin "2") (pinfunction "2_2") (pintype "input"))
      (node (ref "IC1") (pin "127") (pinfunction "XO_127") (pintype "bidirectional"))
      (node (ref "R52") (pin "1") (pinfunction "1_1") (pintype "unspecified"))
      (node (ref "X1") (pin "1") (pinfunction "OSC1_1") (pintype "unspecified"))
    )
    (net (code "164") (name "Net-(IR-V-Pad1)") (class "Default")
      (node (ref "IR-V") (pin "1") (pinfunction "1_1") (pintype "unspecified"))
      (node (ref "R27") (pin "2") (pinfunction "2_2") (pintype "input"))
    )
    (net (code "165") (name "Net-(J13-CC1)") (class "Default")
      (node (ref "J13") (pin "A5") (pinfunction "CC1_A5") (pintype "unspecified"))
      (node (ref "R80") (pin "1") (pinfunction "1_1") (pintype "input"))
    )
    (net (code "166") (name "Net-(J13-CC2)") (class "Default")
      (node (ref "J13") (pin "B5") (pinfunction "CC2_B5") (pintype "unspecified"))
      (node (ref "R76") (pin "2") (pinfunction "2_2") (pintype "input"))
    )
    (net (code "167") (name "Net-(L1.-Pad1)") (class "Default")
      (node (ref "L1.") (pin "1") (pinfunction "1_1") (pintype "unspecified"))
      (node (ref "R45") (pin "2") (pinfunction "2_2") (pintype "unspecified"))
      (node (ref "R46") (pin "2") (pinfunction "2_2") (pintype "input"))
    )
    (net (code "168") (name "Net-(L10-Pad2)") (class "Default")
      (node (ref "L10") (pin "2") (pinfunction "2_2") (pintype "unspecified"))
      (node (ref "R88") (pin "2") (pinfunction "2_2") (pintype "unspecified"))
      (node (ref "R89") (pin "2") (pinfunction "2_2") (pintype "unspecified"))
    )
    (net (code "169") (name "Net-(LG-Pad1)") (class "Default")
      (node (ref "LG") (pin "1") (pinfunction "1_1") (pintype "unspecified"))
      (node (ref "R21") (pin "2") (pinfunction "2_2") (pintype "unspecified"))
      (node (ref "R25") (pin "2") (pinfunction "2_2") (pintype "unspecified"))
    )
    (net (code "170") (name "Net-(LR-Pad1)") (class "Default")
      (node (ref "LR") (pin "1") (pinfunction "1_1") (pintype "unspecified"))
      (node (ref "R22") (pin "2") (pinfunction "2_2") (pintype "unspecified"))
      (node (ref "R9") (pin "2") (pinfunction "2_2") (pintype "unspecified"))
    )
    (net (code "171") (name "Net-(Q1-B)") (class "Default")
      (node (ref "Q1") (pin "1") (pinfunction "B_1") (pintype "unspecified"))
      (node (ref "R39") (pin "1") (pinfunction "1_1") (pintype "unspecified"))
      (node (ref "R40") (pin "2") (pinfunction "2_2") (pintype "input"))
    )
    (net (code "172") (name "Net-(Q2-G)") (class "Default")
      (node (ref "Q2") (pin "4") (pinfunction "G_4") (pintype "unspecified"))
      (node (ref "Q3") (pin "3") (pinfunction "C_3") (pintype "unspecified"))
      (node (ref "R29") (pin "2") (pinfunction "2_2") (pintype "unspecified"))
    )
    (net (code "173") (name "Net-(Q3-B)") (class "Default")
      (node (ref "Q3") (pin "1") (pinfunction "B_1") (pintype "unspecified"))
      (node (ref "R53") (pin "2") (pinfunction "2_2") (pintype "unspecified"))
    )
    (net (code "174") (name "Net-(Q5-B)") (class "Default")
      (node (ref "Q5") (pin "1") (pinfunction "B_1") (pintype "unspecified"))
      (node (ref "R90") (pin "1") (pinfunction "1_1") (pintype "unspecified"))
    )
    (net (code "175") (name "Net-(Q5-C)") (class "Default")
      (node (ref "Q5") (pin "3") (pinfunction "C_3") (pintype "unspecified"))
      (node (ref "R88") (pin "1") (pinfunction "1_1") (pintype "unspecified"))
      (node (ref "U2") (pin "4") (pinfunction "EN_4") (pintype "unspecified"))
    )
    (net (code "176") (name "Net-(Q6-B)") (class "Default")
      (node (ref "Q6") (pin "1") (pinfunction "B_1") (pintype "unspecified"))
      (node (ref "R364") (pin "2") (pinfunction "2_2") (pintype "unspecified"))
    )
    (net (code "177") (name "Net-(Q6-C)") (class "Default")
      (node (ref "Q6") (pin "3") (pinfunction "C_3") (pintype "unspecified"))
      (node (ref "R73") (pin "1") (pinfunction "1_1") (pintype "unspecified"))
      (node (ref "R98") (pin "2") (pinfunction "2_2") (pintype "unspecified"))
    )
    (net (code "178") (name "Net-(R66-Pad2)") (class "Default")
      (node (ref "R66") (pin "2") (pinfunction "2_2") (pintype "input"))
      (node (ref "U6") (pin "3") (pinfunction "3_3") (pintype "unspecified"))
    )
    (net (code "179") (name "Net-(R67-Pad1)") (class "Default")
      (node (ref "R67") (pin "1") (pinfunction "1_1") (pintype "input"))
      (node (ref "U6") (pin "4") (pinfunction "4_4") (pintype "unspecified"))
    )
    (net (code "180") (name "Net-(R91-Pad1)") (class "Default")
      (node (ref "R91") (pin "1") (pinfunction "1_1") (pintype "input"))
      (node (ref "SW3") (pin "1") (pinfunction "1_1") (pintype "unspecified"))
      (node (ref "SW3") (pin "2") (pinfunction "2_2") (pintype "unspecified"))
    )
    (net (code "181") (name "Net-(U1-HOLD#)") (class "Default")
      (node (ref "C17") (pin "2") (pinfunction "2_2") (pintype "input"))
      (node (ref "C25") (pin "2") (pinfunction "2_2") (pintype "input"))
      (node (ref "C82") (pin "2") (pinfunction "2_2") (pintype "unspecified"))
      (node (ref "L11") (pin "2") (pinfunction "2_2") (pintype "unspecified"))
      (node (ref "R10") (pin "1") (pinfunction "1_1") (pintype "unspecified"))
      (node (ref "R18") (pin "1") (pinfunction "1_1") (pintype "unspecified"))
      (node (ref "R20") (pin "1") (pinfunction "1_1") (pintype "unspecified"))
      (node (ref "R25") (pin "1") (pinfunction "1_1") (pintype "unspecified"))
      (node (ref "R27") (pin "1") (pinfunction "1_1") (pintype "input"))
      (node (ref "R28") (pin "1") (pinfunction "1_1") (pintype "unspecified"))
      (node (ref "R30") (pin "1") (pinfunction "1_1") (pintype "unspecified"))
      (node (ref "R31") (pin "1") (pinfunction "1_1") (pintype "unspecified"))
      (node (ref "R32") (pin "2") (pinfunction "2_2") (pintype "unspecified"))
      (node (ref "R82") (pin "1") (pinfunction "1_1") (pintype "unspecified"))
      (node (ref "R87") (pin "1") (pinfunction "1_1") (pintype "unspecified"))
      (node (ref "R9") (pin "1") (pinfunction "1_1") (pintype "unspecified"))
      (node (ref "U1") (pin "7") (pinfunction "HOLD#_7") (pintype "unspecified"))
      (node (ref "U1") (pin "8") (pinfunction "VCC_8") (pintype "unspecified"))
    )
    (net (code "182") (name "Net-(U1-WP#)") (class "Default")
      (node (ref "R82") (pin "2") (pinfunction "2_2") (pintype "unspecified"))
      (node (ref "U1") (pin "3") (pinfunction "WP#_3") (pintype "unspecified"))
    )
    (net (code "183") (name "Net-(U2-FB)") (class "Default")
      (node (ref "R41") (pin "1") (pinfunction "1_1") (pintype "unspecified"))
      (node (ref "R44") (pin "1") (pinfunction "1_1") (pintype "unspecified"))
      (node (ref "U2") (pin "3") (pinfunction "FB_3") (pintype "unspecified"))
    )
    (net (code "184") (name "Net-(U2-IN)") (class "Default")
      (node (ref "L14") (pin "2") (pinfunction "2_2") (pintype "unspecified"))
      (node (ref "L22") (pin "1") (pinfunction "1_1") (pintype "unspecified"))
      (node (ref "U2") (pin "6") (pinfunction "IN_6") (pintype "unspecified"))
    )
    (net (code "185") (name "Net-(U2-SW)") (class "Default")
      (node (ref "C13") (pin "1") (pinfunction "1_1") (pintype "input"))
      (node (ref "C14") (pin "2") (pinfunction "2_2") (pintype "input"))
      (node (ref "D1") (pin "2") (pinfunction "2_2") (pintype "unspecified"))
      (node (ref "D2") (pin "2") (pinfunction "2_2") (pintype "unspecified"))
      (node (ref "L22") (pin "2") (pinfunction "2_2") (pintype "unspecified"))
      (node (ref "U2") (pin "1") (pinfunction "SW_1") (pintype "unspecified"))
    )
    (net (code "186") (name "Net-(U9-BYPASS)") (class "Default")
      (node (ref "C78") (pin "1") (pinfunction "1_1") (pintype "unspecified"))
      (node (ref "U9") (pin "4") (pinfunction "BYPASS_4") (pintype "unspecified"))
    )
    (net (code "187") (name "Net-(U9-LIN-)") (class "Default")
      (node (ref "C81") (pin "1") (pinfunction "1_1") (pintype "unspecified"))
      (node (ref "U9") (pin "6") (pinfunction "LIN-_6") (pintype "unspecified"))
    )
    (net (code "188") (name "Net-(U9-LOUT+)") (class "Default")
      (node (ref "L100") (pin "1") (pinfunction "1_1") (pintype "unspecified"))
      (node (ref "U9") (pin "11") (pinfunction "LOUT+_11") (pintype "unspecified"))
    )
    (net (code "189") (name "Net-(U9-LOUT-)") (class "Default")
      (node (ref "L110") (pin "1") (pinfunction "1_1") (pintype "unspecified"))
      (node (ref "U9") (pin "9") (pinfunction "LOUT-_9") (pintype "unspecified"))
    )
    (net (code "190") (name "Net-(U9-RIN-)") (class "Default")
      (node (ref "C83") (pin "1") (pinfunction "1_1") (pintype "unspecified"))
      (node (ref "U9") (pin "3") (pinfunction "RIN-_3") (pintype "unspecified"))
    )
    (net (code "191") (name "Net-(U9-ROUT+)") (class "Default")
      (node (ref "L90") (pin "1") (pinfunction "1_1") (pintype "unspecified"))
      (node (ref "U9") (pin "14") (pinfunction "ROUT+_14") (pintype "unspecified"))
    )
    (net (code "192") (name "Net-(U9-ROUT-)") (class "Default")
      (node (ref "L80") (pin "1") (pinfunction "1_1") (pintype "unspecified"))
      (node (ref "U9") (pin "16") (pinfunction "ROUT-_16") (pintype "unspecified"))
    )
    (net (code "193") (name "Net-(U9-SD#)") (class "Default")
      (node (ref "R101") (pin "2") (pinfunction "2_2") (pintype "input"))
      (node (ref "U9") (pin "2") (pinfunction "SD#_2") (pintype "unspecified"))
    )
    (net (code "194") (name "Net-(U9-SE{slash}BTL#)") (class "Default")
      (node (ref "R95") (pin "1") (pinfunction "1_1") (pintype "input"))
      (node (ref "U9") (pin "13") (pinfunction "SE/BTL#_13") (pintype "unspecified"))
    )
    (net (code "195") (name "Net-(U11-NC)") (class "Default")
      (node (ref "C60") (pin "2") (pinfunction "2_2") (pintype "input"))
      (node (ref "U11") (pin "4") (pinfunction "NC_4") (pintype "unspecified"))
    )
    (net (code "196") (name "Net-(U13-GPIO16)") (class "Default")
      (node (ref "R100") (pin "1") (pinfunction "1_1") (pintype "input"))
      (node (ref "U13") (pin "27") (pinfunction "GPIO16_27") (pintype "bidirectional"))
    )
    (net (code "197") (name "Net-(U13-GPIO17)") (class "Default")
      (node (ref "R75") (pin "1") (pinfunction "1_1") (pintype "input"))
      (node (ref "U13") (pin "28") (pinfunction "GPIO17_28") (pintype "bidirectional"))
    )
    (net (code "198") (name "Net-(U13-GPIO18)") (class "Default")
      (node (ref "R74") (pin "1") (pinfunction "1_1") (pintype "input"))
      (node (ref "U13") (pin "29") (pinfunction "GPIO18_29") (pintype "bidirectional"))
    )
    (net (code "199") (name "Net-(U13-GPIO19)") (class "Default")
      (node (ref "R99") (pin "1") (pinfunction "1_1") (pintype "input"))
      (node (ref "U13") (pin "30") (pinfunction "GPIO19_30") (pintype "bidirectional"))
    )
    (net (code "200") (name "Net-(U13-GPIO20)") (class "Default")
      (node (ref "R97") (pin "1") (pinfunction "1_1") (pintype "input"))
      (node (ref "U13") (pin "31") (pinfunction "GPIO20_31") (pintype "bidirectional"))
    )
    (net (code "201") (name "Net-(U13-USB_DM)") (class "Default")
      (node (ref "D-,1") (pin "1") (pinfunction "1_1") (pintype "unspecified"))
      (node (ref "D-1") (pin "1") (pinfunction "1_1") (pintype "unspecified"))
      (node (ref "R93") (pin "1") (pinfunction "1_1") (pintype "input"))
      (node (ref "U13") (pin "46") (pinfunction "USB_DM_46") (pintype "bidirectional"))
    )
    (net (code "202") (name "Net-(U13-USB_DP)") (class "Default")
      (node (ref "D+,1") (pin "1") (pinfunction "1_1") (pintype "unspecified"))
      (node (ref "D+1") (pin "1") (pinfunction "1_1") (pintype "unspecified"))
      (node (ref "R96") (pin "1") (pinfunction "1_1") (pintype "input"))
      (node (ref "U13") (pin "47") (pinfunction "USB_DP_47") (pintype "bidirectional"))
    )
    (net (code "203") (name "Net-(Y1-OSC1)") (class "Default")
      (node (ref "C67") (pin "2") (pinfunction "2_2") (pintype "input"))
      (node (ref "R92") (pin "2") (pinfunction "2_2") (pintype "input"))
      (node (ref "Y1") (pin "1") (pinfunction "OSC1_1") (pintype "unspecified"))
    )
    (net (code "204") (name "OLED_SCL") (class "Default")
      (node (ref "H1") (pin "2") (pinfunction "2_2") (pintype "unspecified"))
      (node (ref "U13") (pin "37") (pinfunction "GPIO25_37") (pintype "bidirectional"))
    )
    (net (code "205") (name "OLED_SDA") (class "Default")
      (node (ref "H1") (pin "1") (pinfunction "1_1") (pintype "unspecified"))
      (node (ref "U13") (pin "40") (pinfunction "GPIO28_ADC2_40") (pintype "bidirectional"))
    )
    (net (code "206") (name "OSCIN") (class "Default")
      (node (ref "C46") (pin "2") (pinfunction "2_2") (pintype "input"))
      (node (ref "R70") (pin "1") (pinfunction "1_1") (pintype "unspecified"))
      (node (ref "U5") (pin "5") (pinfunction "PD0-OSC_IN_5") (pintype "unspecified"))
      (node (ref "X3") (pin "1") (pinfunction "1_1") (pintype "input"))
    )
    (net (code "207") (name "OSCOUT") (class "Default")
      (node (ref "C45") (pin "2") (pinfunction "2_2") (pintype "input"))
      (node (ref "R70") (pin "2") (pinfunction "2_2") (pintype "unspecified"))
      (node (ref "U5") (pin "6") (pinfunction "PD1-OSC_OUT_6") (pintype "unspecified"))
      (node (ref "X3") (pin "3") (pinfunction "3_3") (pintype "input"))
    )
    (net (code "208") (name "PA0") (class "Default")
      (node (ref "RIGHT-1") (pin "19") (pinfunction "19_19") (pintype "unspecified"))
      (node (ref "RY") (pin "1") (pinfunction "1_1") (pintype "unspecified"))
      (node (ref "U5") (pin "10") (pinfunction "PA0-WKUP_10") (pintype "unspecified"))
    )
    (net (code "209") (name "PA3") (class "Default")
      (node (ref "RIGHT-1") (pin "20") (pinfunction "20_20") (pintype "unspecified"))
      (node (ref "RX") (pin "1") (pinfunction "1_1") (pintype "unspecified"))
      (node (ref "U5") (pin "13") (pinfunction "PA3_13") (pintype "unspecified"))
    )
    (net (code "210") (name "PA6") (class "Default")
      (node (ref "LEFT-1") (pin "12") (pinfunction "12_12") (pintype "unspecified"))
      (node (ref "RIGHT") (pin "1") (pinfunction "1_1") (pintype "unspecified"))
      (node (ref "U5") (pin "16") (pinfunction "PA6_16") (pintype "unspecified"))
    )
    (net (code "211") (name "PA7") (class "Default")
      (node (ref "LEFT-1") (pin "11") (pinfunction "11_11") (pintype "unspecified"))
      (node (ref "U5") (pin "17") (pinfunction "PA7_17") (pintype "unspecified"))
      (node (ref "UP") (pin "1") (pinfunction "1_1") (pintype "unspecified"))
    )
    (net (code "212") (name "PA11") (class "Default")
      (node (ref "PA11") (pin "1") (pinfunction "1_1") (pintype "unspecified"))
      (node (ref "R61") (pin "2") (pinfunction "2_2") (pintype "input"))
      (node (ref "U5") (pin "32") (pinfunction "PA11_32") (pintype "unspecified"))
    )
    (net (code "213") (name "PA12") (class "Default")
      (node (ref "PA12") (pin "1") (pinfunction "1_1") (pintype "unspecified"))
      (node (ref "R62") (pin "2") (pinfunction "2_2") (pintype "unspecified"))
      (node (ref "R63") (pin "2") (pinfunction "2_2") (pintype "input"))
      (node (ref "U5") (pin "33") (pinfunction "PA12_33") (pintype "unspecified"))
    )
    (net (code "214") (name "PB0") (class "Default")
      (node (ref "R/2") (pin "1") (pinfunction "1_1") (pintype "unspecified"))
      (node (ref "RIGHT-1") (pin "16") (pinfunction "16_16") (pintype "unspecified"))
      (node (ref "U5") (pin "18") (pinfunction "PB0_18") (pintype "unspecified"))
    )
    (net (code "215") (name "PB1") (class "Default")
      (node (ref "R/1") (pin "1") (pinfunction "1_1") (pintype "unspecified"))
      (node (ref "RIGHT-1") (pin "18") (pinfunction "18_18") (pintype "unspecified"))
      (node (ref "U5") (pin "19") (pinfunction "PB1_19") (pintype "unspecified"))
    )
    (net (code "216") (name "PB3") (class "Default")
      (node (ref "C28") (pin "1") (pinfunction "1_1") (pintype "input"))
      (node (ref "IC1") (pin "64") (pinfunction "SD0/SPDIF0/TCON[0]/GPIO/IRDA_64") (pintype "bidirectional"))
      (node (ref "IR") (pin "1") (pinfunction "1_1") (pintype "unspecified"))
      (node (ref "PB3") (pin "1") (pinfunction "1_1") (pintype "unspecified"))
      (node (ref "R38") (pin "1") (pinfunction "1_1") (pintype "unspecified"))
      (node (ref "R72") (pin "1") (pinfunction "1_1") (pintype "unspecified"))
      (node (ref "U5") (pin "39") (pinfunction "PB3_39") (pintype "unspecified"))
    )
    (net (code "217") (name "PB4") (class "Default")
      (node (ref "RIGHT-1") (pin "10") (pinfunction "10_10") (pintype "unspecified"))
      (node (ref "TRIANGLE") (pin "1") (pinfunction "1_1") (pintype "unspecified"))
      (node (ref "U5") (pin "40") (pinfunction "PB4_40") (pintype "unspecified"))
    )
    (net (code "218") (name "PB5") (class "Default")
      (node (ref "RIGHT-1") (pin "11") (pinfunction "11_11") (pintype "unspecified"))
      (node (ref "SQUARE") (pin "1") (pinfunction "1_1") (pintype "unspecified"))
      (node (ref "U5") (pin "41") (pinfunction "PB5_41") (pintype "unspecified"))
    )
    (net (code "219") (name "PB6") (class "Default")
      (node (ref "PB6") (pin "1") (pinfunction "1_1") (pintype "unspecified"))
      (node (ref "U5") (pin "42") (pinfunction "PB6_42") (pintype "unspecified"))
    )
    (net (code "220") (name "PB7") (class "Default")
      (node (ref "PB7") (pin "1") (pinfunction "1_1") (pintype "unspecified"))
      (node (ref "U5") (pin "43") (pinfunction "PB7_43") (pintype "unspecified"))
    )
    (net (code "221") (name "PB10") (class "Default")
      (node (ref "R/3") (pin "1") (pinfunction "1_1") (pintype "unspecified"))
      (node (ref "RIGHT-1") (pin "17") (pinfunction "17_17") (pintype "unspecified"))
      (node (ref "U5") (pin "21") (pinfunction "PB10_21") (pintype "unspecified"))
    )
    (net (code "222") (name "PB11") (class "Default")
      (node (ref "PB11") (pin "1") (pinfunction "1_1") (pintype "unspecified"))
      (node (ref "U5") (pin "22") (pinfunction "PB11_22") (pintype "unspecified"))
    )
    (net (code "223") (name "PC13") (class "Default")
      (node (ref "LEFT-1") (pin "7") (pinfunction "7_7") (pintype "unspecified"))
      (node (ref "R68") (pin "2") (pinfunction "2_2") (pintype "unspecified"))
      (node (ref "RIGHT-1") (pin "9") (pinfunction "9_9") (pintype "unspecified"))
      (node (ref "SELECT") (pin "1") (pinfunction "1_1") (pintype "unspecified"))
      (node (ref "U5") (pin "2") (pinfunction "PC13-TAMPER-RTC_2") (pintype "unspecified"))
    )
    (net (code "224") (name "PC15") (class "Default")
      (node (ref "LEFT-1") (pin "6") (pinfunction "6_6") (pintype "unspecified"))
      (node (ref "RIGHT-1") (pin "15") (pinfunction "15_15") (pintype "unspecified"))
      (node (ref "START") (pin "1") (pinfunction "1_1") (pintype "unspecified"))
      (node (ref "U5") (pin "4") (pinfunction "PC15-OSC32_OUT_4") (pintype "unspecified"))
    )
    (net (code "225") (name "PSM") (class "Default")
      (node (ref "CONTROL3") (pin "8") (pinfunction "8_8") (pintype "unspecified"))
      (node (ref "U7") (pin "3") (pinfunction "8.5V_3") (pintype "unspecified"))
    )
    (net (code "226") (name "PSRAM_CLK") (class "Default")
      (node (ref "U10") (pin "6") (pinfunction "SCLK_6") (pintype "unspecified"))
      (node (ref "U13") (pin "5") (pinfunction "GPIO3_5") (pintype "bidirectional"))
      (node (ref "U8") (pin "6") (pinfunction "SCLK_6") (pintype "unspecified"))
    )
    (net (code "227") (name "PSRAM_CS") (class "Default")
      (node (ref "U10") (pin "1") (pinfunction "CE#_1") (pintype "unspecified"))
      (node (ref "U13") (pin "4") (pinfunction "GPIO2_4") (pintype "bidirectional"))
      (node (ref "U8") (pin "1") (pinfunction "#CE_1") (pintype "unspecified"))
    )
    (net (code "228") (name "PSRAM_IO0") (class "Default")
      (node (ref "U10") (pin "5") (pinfunction "SI/SIO[0]_5") (pintype "unspecified"))
      (node (ref "U13") (pin "6") (pinfunction "GPIO4_6") (pintype "bidirectional"))
      (node (ref "U8") (pin "5") (pinfunction "SI/SIO0_5") (pintype "unspecified"))
    )
    (net (code "229") (name "PSRAM_IO1") (class "Default")
      (node (ref "U10") (pin "2") (pinfunction "SO/SIO[1]_2") (pintype "unspecified"))
      (node (ref "U13") (pin "7") (pinfunction "GPIO5_7") (pintype "bidirectional"))
      (node (ref "U8") (pin "2") (pinfunction "SO/SIO1_2") (pintype "unspecified"))
    )
    (net (code "230") (name "PSRAM_IO2") (class "Default")
      (node (ref "U10") (pin "3") (pinfunction "SIO[2]_3") (pintype "unspecified"))
      (node (ref "U13") (pin "8") (pinfunction "GPIO6_8") (pintype "bidirectional"))
      (node (ref "U8") (pin "3") (pinfunction "SIO2_3") (pintype "unspecified"))
    )
    (net (code "231") (name "PSRAM_IO3") (class "Default")
      (node (ref "U10") (pin "7") (pinfunction "SIO[3]_7") (pintype "unspecified"))
      (node (ref "U13") (pin "9") (pinfunction "GPIO7_9") (pintype "bidirectional"))
      (node (ref "U8") (pin "7") (pinfunction "SIO3_7") (pintype "unspecified"))
    )
    (net (code "232") (name "PSX_3.5V") (class "Default")
      (node (ref "3.5V") (pin "1") (pinfunction "1_1") (pintype "unspecified"))
      (node (ref "C54") (pin "2") (pinfunction "2_2") (pintype "unspecified"))
      (node (ref "D8") (pin "2") (pinfunction "A_2") (pintype "unspecified"))
    )
    (net (code "233") (name "PSX_7.5V") (class "Default")
      (node (ref "8.5V") (pin "1") (pinfunction "1_1") (pintype "unspecified"))
    )
    (net (code "234") (name "PSX_ACK") (class "Default")
      (node (ref "ACK1") (pin "1") (pinfunction "1_1") (pintype "unspecified"))
      (node (ref "R100") (pin "2") (pinfunction "2_2") (pintype "input"))
    )
    (net (code "235") (name "PSX_CLK") (class "Default")
      (node (ref "CLK1") (pin "1") (pinfunction "1_1") (pintype "unspecified"))
      (node (ref "R74") (pin "2") (pinfunction "2_2") (pintype "input"))
    )
    (net (code "236") (name "PSX_CMD") (class "Default")
      (node (ref "CMD1") (pin "1") (pinfunction "1_1") (pintype "unspecified"))
      (node (ref "R99") (pin "2") (pinfunction "2_2") (pintype "input"))
    )
    (net (code "237") (name "PSX_DAT") (class "Default")
      (node (ref "DAT1") (pin "1") (pinfunction "1_1") (pintype "unspecified"))
      (node (ref "R97") (pin "2") (pinfunction "2_2") (pintype "input"))
    )
    (net (code "238") (name "PSX_SEL") (class "Default")
      (node (ref "ATT1") (pin "1") (pinfunction "1_1") (pintype "unspecified"))
      (node (ref "R75") (pin "2") (pinfunction "2_2") (pintype "input"))
    )
    (net (code "239") (name "PWM5") (class "Default")
      (node (ref "IC1") (pin "101") (pinfunction "GPIO/PWM5/TCON[0]_101") (pintype "bidirectional"))
      (node (ref "Q1") (pin "3") (pinfunction "C_3") (pintype "unspecified"))
      (node (ref "R38") (pin "2") (pinfunction "2_2") (pintype "unspecified"))
    )
    (net (code "240") (name "QSPI_SCLK") (class "Default")
      (node (ref "U12") (pin "6") (pinfunction "CLK_6") (pintype "unspecified"))
      (node (ref "U13") (pin "52") (pinfunction "QSPI_SCLK_52") (pintype "output"))
    )
    (net (code "241") (name "QSPI_SD0") (class "Default")
      (node (ref "U12") (pin "5") (pinfunction "DI(IO0)_5") (pintype "unspecified"))
      (node (ref "U13") (pin "53") (pinfunction "QSPI_SD0_53") (pintype "bidirectional"))
    )
    (net (code "242") (name "QSPI_SD1") (class "Default")
      (node (ref "U12") (pin "2") (pinfunction "DO(IO1)_2") (pintype "unspecified"))
      (node (ref "U13") (pin "55") (pinfunction "QSPI_SD1_55") (pintype "bidirectional"))
    )
    (net (code "243") (name "QSPI_SD2") (class "Default")
      (node (ref "U12") (pin "3") (pinfunction "WP#(IO2)_3") (pintype "unspecified"))
      (node (ref "U13") (pin "54") (pinfunction "QSPI_SD2_54") (pintype "bidirectional"))
    )
    (net (code "244") (name "QSPI_SD3") (class "Default")
      (node (ref "U12") (pin "7") (pinfunction "HOLD#orRESET#(IO3)_7") (pintype "unspecified"))
      (node (ref "U13") (pin "51") (pinfunction "QSPI_SD3_51") (pintype "bidirectional"))
    )
    (net (code "245") (name "QSPI_SS") (class "Default")
      (node (ref "R91") (pin "2") (pinfunction "2_2") (pintype "input"))
      (node (ref "SW3,") (pin "1") (pinfunction "1_1") (pintype "unspecified"))
      (node (ref "SW3/") (pin "1") (pinfunction "1_1") (pintype "unspecified"))
      (node (ref "U12") (pin "1") (pinfunction "CS#_1") (pintype "unspecified"))
      (node (ref "U13") (pin "56") (pinfunction "QSPI_SS_56") (pintype "bidirectional"))
    )
    (net (code "246") (name "R") (class "Default")
      (node (ref "C83") (pin "2") (pinfunction "2_2") (pintype "unspecified"))
      (node (ref "PS2") (pin "19") (pinfunction "19_19") (pintype "unspecified"))
      (node (ref "R-IN1") (pin "1") (pinfunction "1_1") (pintype "unspecified"))
    )
    (net (code "247") (name "R+") (class "Default")
      (node (ref "C44") (pin "1") (pinfunction "1_1") (pintype "input"))
      (node (ref "C72") (pin "1") (pinfunction "1_1") (pintype "unspecified"))
      (node (ref "L90") (pin "2") (pinfunction "2_2") (pintype "unspecified"))
      (node (ref "R+") (pin "1") (pinfunction "1_1") (pintype "unspecified"))
    )
    (net (code "248") (name "RESET") (class "Default")
      (node (ref "C50") (pin "2") (pinfunction "2_2") (pintype "unspecified"))
      (node (ref "R69") (pin "1") (pinfunction "1_1") (pintype "unspecified"))
      (node (ref "RESET") (pin "1") (pinfunction "1_1") (pintype "unspecified"))
      (node (ref "U5") (pin "7") (pinfunction "NRST_7") (pintype "unspecified"))
    )
    (net (code "249") (name "RESET-RT") (class "Default")
      (node (ref "FPC2") (pin "8") (pinfunction "8_8") (pintype "unspecified"))
      (node (ref "PS2") (pin "3") (pinfunction "3_3") (pintype "unspecified"))
    )
    (net (code "250") (name "RO") (class "Default")
      (node (ref "L3.") (pin "2") (pinfunction "2_2") (pintype "unspecified"))
      (node (ref "PS2") (pin "21") (pinfunction "21_21") (pintype "unspecified"))
      (node (ref "R") (pin "1") (pinfunction "1_1") (pintype "unspecified"))
    )
    (net (code "251") (name "SCL.") (class "Default")
      (node (ref "R24") (pin "2") (pinfunction "2_2") (pintype "unspecified"))
      (node (ref "SCL") (pin "1") (pinfunction "1_1") (pintype "unspecified"))
    )
    (net (code "252") (name "SCLK") (class "Default")
      (node (ref "R14") (pin "1") (pinfunction "1_1") (pintype "unspecified"))
      (node (ref "U1") (pin "6") (pinfunction "CLK_6") (pintype "unspecified"))
    )
    (net (code "253") (name "SDA.") (class "Default")
      (node (ref "R23") (pin "2") (pinfunction "2_2") (pintype "unspecified"))
      (node (ref "SDA") (pin "1") (pinfunction "1_1") (pintype "unspecified"))
    )
    (net (code "254") (name "SD_CLK") (class "Default")
      (node (ref "CARD1") (pin "5") (pinfunction "CLK_5") (pintype "unspecified"))
      (node (ref "U13") (pin "38") (pinfunction "GPIO26_ADC0_38") (pintype "bidirectional"))
    )
    (net (code "255") (name "SD_CS") (class "Default")
      (node (ref "CARD1") (pin "2") (pinfunction "CD/DAT3_2") (pintype "unspecified"))
      (node (ref "U13") (pin "41") (pinfunction "GPIO29_ADC3_41") (pintype "bidirectional"))
    )
    (net (code "256") (name "SD_MISO") (class "Default")
      (node (ref "CARD1") (pin "7") (pinfunction "DAT0_7") (pintype "unspecified"))
      (node (ref "R81") (pin "2") (pinfunction "2_2") (pintype "input"))
      (node (ref "U13") (pin "36") (pinfunction "GPIO24_36") (pintype "bidirectional"))
    )
    (net (code "257") (name "SD_MOSI") (class "Default")
      (node (ref "CARD1") (pin "3") (pinfunction "CMD_3") (pintype "unspecified"))
      (node (ref "U13") (pin "39") (pinfunction "GPIO27_ADC1_39") (pintype "bidirectional"))
    )
    (net (code "258") (name "SE{slash}BTL#") (class "Default")
      (node (ref "CN2") (pin "4") (pinfunction "4_4") (pintype "unspecified"))
      (node (ref "R94") (pin "1") (pinfunction "1_1") (pintype "input"))
      (node (ref "R95") (pin "2") (pinfunction "2_2") (pintype "input"))
    )
    (net (code "259") (name "SI") (class "Default")
      (node (ref "R13") (pin "1") (pinfunction "1_1") (pintype "unspecified"))
      (node (ref "U1") (pin "5") (pinfunction "DI_5") (pintype "unspecified"))
    )
    (net (code "260") (name "SO") (class "Default")
      (node (ref "R12") (pin "1") (pinfunction "1_1") (pintype "unspecified"))
      (node (ref "U1") (pin "2") (pinfunction "DO_2") (pintype "unspecified"))
    )
    (net (code "261") (name "SOURCE") (class "Default")
      (node (ref "FPC2") (pin "1") (pinfunction "1_1") (pintype "unspecified"))
      (node (ref "R36") (pin "1") (pinfunction "1_1") (pintype "unspecified"))
      (node (ref "SC") (pin "1") (pinfunction "1_1") (pintype "unspecified"))
    )
    (net (code "262") (name "SW1") (class "Default")
      (node (ref "SW1") (pin "1") (pinfunction "1_1") (pintype "unspecified"))
      (node (ref "SW1") (pin "2") (pinfunction "2_2") (pintype "unspecified"))
      (node (ref "SW1,") (pin "1") (pinfunction "1_1") (pintype "unspecified"))
      (node (ref "SW1/") (pin "1") (pinfunction "1_1") (pintype "unspecified"))
      (node (ref "U13") (pin "32") (pinfunction "GPIO21_32") (pintype "bidirectional"))
    )
    (net (code "263") (name "SW2") (class "Default")
      (node (ref "SW2") (pin "1") (pinfunction "1_1") (pintype "unspecified"))
      (node (ref "SW2") (pin "2") (pinfunction "2_2") (pintype "unspecified"))
      (node (ref "SW2,") (pin "1") (pinfunction "1_1") (pintype "unspecified"))
      (node (ref "SW2/") (pin "1") (pinfunction "1_1") (pintype "unspecified"))
      (node (ref "U13") (pin "35") (pinfunction "GPIO23_35") (pintype "bidirectional"))
    )
    (net (code "264") (name "SWCLK") (class "Default")
      (node (ref "C51") (pin "1") (pinfunction "1_1") (pintype "unspecified"))
      (node (ref "U13") (pin "24") (pinfunction "SWCLK_24") (pintype "output"))
    )
    (net (code "265") (name "SWDCLK") (class "Default")
      (node (ref "SWCLK") (pin "1") (pinfunction "1_1") (pintype "unspecified"))
      (node (ref "U5") (pin "37") (pinfunction "SWDCLK_37") (pintype "unspecified"))
    )
    (net (code "266") (name "SWDIO") (class "Default")
      (node (ref "D7") (pin "1") (pinfunction "1_1") (pintype "unspecified"))
      (node (ref "SWIO") (pin "1") (pinfunction "1_1") (pintype "unspecified"))
      (node (ref "U13") (pin "25") (pinfunction "SWD_25") (pintype "bidirectional"))
      (node (ref "U5") (pin "34") (pinfunction "PA13_34") (pintype "unspecified"))
    )
    (net (code "267") (name "UART_RX") (class "Default")
      (node (ref "RX1") (pin "1") (pinfunction "1_1") (pintype "unspecified"))
      (node (ref "U13") (pin "12") (pinfunction "GPIO9_12") (pintype "bidirectional"))
    )
    (net (code "268") (name "UART_TX") (class "Default")
      (node (ref "TX1") (pin "1") (pinfunction "1_1") (pintype "unspecified"))
      (node (ref "U13") (pin "11") (pinfunction "GPIO8_11") (pintype "bidirectional"))
    )
    (net (code "269") (name "VBAT") (class "Default")
      (node (ref "U5") (pin "1") (pinfunction "VBAT_1") (pintype "unspecified"))
      (node (ref "VBAT") (pin "1") (pinfunction "1_1") (pintype "unspecified"))
    )
    (net (code "270") (name "VBUS") (class "Default")
      (node (ref "C52") (pin "2") (pinfunction "2_2") (pintype "unspecified"))
      (node (ref "D9") (pin "2") (pinfunction "A_2") (pintype "unspecified"))
      (node (ref "J13") (pin "A4") (pinfunction "VBUS_A4") (pintype "unspecified"))
      (node (ref "J13") (pin "A9") (pinfunction "VBUS_A9") (pintype "unspecified"))
      (node (ref "J13") (pin "B4") (pinfunction "VBUS_B4") (pintype "unspecified"))
      (node (ref "J13") (pin "B9") (pinfunction "VBUS_B9") (pintype "unspecified"))
    )
    (net (code "271") (name "VOL") (class "Default")
      (node (ref "C76") (pin "1") (pinfunction "1_1") (pintype "unspecified"))
      (node (ref "C77") (pin "1") (pinfunction "1_1") (pintype "unspecified"))
      (node (ref "R98") (pin "1") (pinfunction "1_1") (pintype "unspecified"))
      (node (ref "U9") (pin "7") (pinfunction "VOLUME_7") (pintype "unspecified"))
    )
    (net (code "272") (name "VOL_PWM") (class "Default")
      (node (ref "IC1") (pin "55") (pinfunction "BADC0/PWM1/PWM5/GPIO_55") (pintype "bidirectional"))
      (node (ref "R364") (pin "1") (pinfunction "1_1") (pintype "unspecified"))
    )
    (net (code "273") (name "VSYNC") (class "Default")
      (node (ref "PS2") (pin "1") (pinfunction "1_1") (pintype "unspecified"))
      (node (ref "R55") (pin "1") (pinfunction "1_1") (pintype "unspecified"))
      (node (ref "R56") (pin "2") (pinfunction "2_2") (pintype "unspecified"))
      (node (ref "VS1") (pin "1") (pinfunction "1_1") (pintype "unspecified"))
    )
    (net (code "274") (name "VSYS") (class "Default")
      (node (ref "FPC2") (pin "12") (pinfunction "12_12") (pintype "unspecified"))
      (node (ref "FPC2") (pin "13") (pinfunction "13_13") (pintype "unspecified"))
      (node (ref "PS2") (pin "29") (pinfunction "29_29") (pintype "unspecified"))
      (node (ref "PS2") (pin "30") (pinfunction "30_30") (pintype "unspecified"))
      (node (ref "RIGHT-1") (pin "1") (pinfunction "1_1") (pintype "unspecified"))
      (node (ref "RIGHT-1") (pin "2") (pinfunction "2_2") (pintype "unspecified"))
    )
    (net (code "275") (name "XIN") (class "Default")
      (node (ref "C68") (pin "1") (pinfunction "1_1") (pintype "input"))
      (node (ref "U13") (pin "20") (pinfunction "XIN_20") (pintype "input"))
      (node (ref "Y1") (pin "3") (pinfunction "OSC2_3") (pintype "unspecified"))
    )
    (net (code "276") (name "XOUT") (class "Default")
      (node (ref "R92") (pin "1") (pinfunction "1_1") (pintype "input"))
      (node (ref "U13") (pin "21") (pinfunction "XOUT_21") (pintype "unspecified"))
    )
    (net (code "277") (name "button") (class "Default")
      (node (ref "LEFT-1") (pin "5") (pinfunction "5_5") (pintype "unspecified"))
      (node (ref "PS2") (pin "13") (pinfunction "13_13") (pintype "unspecified"))
    )
    (net (code "278") (name "unconnected-(CARD1-CD-Pad9)") (class "Default")
      (node (ref "CARD1") (pin "9") (pinfunction "CD_9") (pintype "unspecified+no_connect"))
    )
    (net (code "279") (name "unconnected-(CARD1-DAT1-Pad8)") (class "Default")
      (node (ref "CARD1") (pin "8") (pinfunction "DAT1_8") (pintype "unspecified+no_connect"))
    )
    (net (code "280") (name "unconnected-(CARD1-DAT2-Pad1)") (class "Default")
      (node (ref "CARD1") (pin "1") (pinfunction "DAT2_1") (pintype "unspecified+no_connect"))
    )
    (net (code "281") (name "unconnected-(FPC1-Pad1)") (class "Default")
      (node (ref "FPC1") (pin "1") (pinfunction "1_1") (pintype "unspecified+no_connect"))
    )
    (net (code "282") (name "unconnected-(FPC1-Pad2)") (class "Default")
      (node (ref "FPC1") (pin "2") (pinfunction "2_2") (pintype "unspecified+no_connect"))
    )
    (net (code "283") (name "unconnected-(FPC1-Pad6)") (class "Default")
      (node (ref "FPC1") (pin "6") (pinfunction "6_6") (pintype "unspecified+no_connect"))
    )
    (net (code "284") (name "unconnected-(FPC1-Pad43)") (class "Default")
      (node (ref "FPC1") (pin "43") (pinfunction "43_43") (pintype "unspecified+no_connect"))
    )
    (net (code "285") (name "unconnected-(FPC2-Pad14)") (class "Default")
      (node (ref "FPC2") (pin "14") (pinfunction "14_14") (pintype "unspecified+no_connect"))
    )
    (net (code "286") (name "unconnected-(FPC6-Pad35)") (class "Default")
      (node (ref "FPC6") (pin "35") (pinfunction "35_35") (pintype "unspecified+no_connect"))
    )
    (net (code "287") (name "unconnected-(FPC6-Pad37)") (class "Default")
      (node (ref "FPC6") (pin "37") (pinfunction "37_37") (pintype "unspecified+no_connect"))
    )
    (net (code "288") (name "unconnected-(FPC6-Pad38)") (class "Default")
      (node (ref "FPC6") (pin "38") (pinfunction "38_38") (pintype "unspecified+no_connect"))
    )
    (net (code "289") (name "unconnected-(FPC6-Pad39)") (class "Default")
      (node (ref "FPC6") (pin "39") (pinfunction "39_39") (pintype "unspecified+no_connect"))
    )
    (net (code "290") (name "unconnected-(FPC6-Pad40)") (class "Default")
      (node (ref "FPC6") (pin "40") (pinfunction "40_40") (pintype "unspecified+no_connect"))
    )
    (net (code "291") (name "unconnected-(HDMI1-Pad7)") (class "Default")
      (node (ref "HDMI1") (pin "7") (pinfunction "7_7") (pintype "unspecified+no_connect"))
    )
    (net (code "292") (name "unconnected-(HDMI1-Pad8)") (class "Default")
      (node (ref "HDMI1") (pin "8") (pinfunction "8_8") (pintype "unspecified+no_connect"))
    )
    (net (code "293") (name "unconnected-(IC1-A-ADC1{slash}GPIO-Pad51)") (class "Default")
      (node (ref "IC1") (pin "51") (pinfunction "A-ADC1/GPIO_51") (pintype "bidirectional+no_connect"))
    )
    (net (code "294") (name "unconnected-(IC1-A-ADC4{slash}GPIO-Pad54)") (class "Default")
      (node (ref "IC1") (pin "54") (pinfunction "A-ADC4/GPIO_54") (pintype "bidirectional+no_connect"))
    )
    (net (code "295") (name "unconnected-(IC1-CEC-Pad126)") (class "Default")
      (node (ref "IC1") (pin "126") (pinfunction "CEC_126") (pintype "bidirectional+no_connect"))
    )
    (net (code "296") (name "unconnected-(IC1-DDCSCL3{slash}GPIO-Pad121)") (class "Default")
      (node (ref "IC1") (pin "121") (pinfunction "DDCSCL3/GPIO_121") (pintype "bidirectional+no_connect"))
    )
    (net (code "297") (name "unconnected-(IC1-DDCSDA3{slash}GPIO-Pad122)") (class "Default")
      (node (ref "IC1") (pin "122") (pinfunction "DDCSDA3/GPIO_122") (pintype "bidirectional+no_connect"))
    )
    (net (code "298") (name "unconnected-(IC1-GPIO{slash}PWM4{slash}TCON[12][3]-Pad100)") (class "Default")
      (node (ref "IC1") (pin "100") (pinfunction "GPIO/PWM4/TCON[12][3]_100") (pintype "bidirectional+no_connect"))
    )
    (net (code "299") (name "unconnected-(IC1-MCK{slash}TCON[7]{slash}GPIO-Pad108)") (class "Default")
      (node (ref "IC1") (pin "108") (pinfunction "MCK/TCON[7]/GPIO_108") (pintype "bidirectional+no_connect"))
    )
    (net (code "300") (name "unconnected-(IC1-NC_2-Pad12)") (class "Default")
      (node (ref "IC1") (pin "12") (pinfunction "NC_2_12") (pintype "bidirectional+no_connect"))
    )
    (net (code "301") (name "unconnected-(IC1-NC_3-Pad13)") (class "Default")
      (node (ref "IC1") (pin "13") (pinfunction "NC_3_13") (pintype "bidirectional+no_connect"))
    )
    (net (code "302") (name "unconnected-(IC1-NC_4-Pad14)") (class "Default")
      (node (ref "IC1") (pin "14") (pinfunction "NC_4_14") (pintype "bidirectional+no_connect"))
    )
    (net (code "303") (name "unconnected-(IC1-NC_5-Pad15)") (class "Default")
      (node (ref "IC1") (pin "15") (pinfunction "NC_5_15") (pintype "bidirectional+no_connect"))
    )
    (net (code "304") (name "unconnected-(IC1-NC_6-Pad16)") (class "Default")
      (node (ref "IC1") (pin "16") (pinfunction "NC_6_16") (pintype "bidirectional+no_connect"))
    )
    (net (code "305") (name "unconnected-(IC1-NC_7-Pad17)") (class "Default")
      (node (ref "IC1") (pin "17") (pinfunction "NC_7_17") (pintype "bidirectional+no_connect"))
    )
    (net (code "306") (name "unconnected-(IC1-NC_8-Pad18)") (class "Default")
      (node (ref "IC1") (pin "18") (pinfunction "NC_8_18") (pintype "bidirectional+no_connect"))
    )
    (net (code "307") (name "unconnected-(IC1-NC_9-Pad19)") (class "Default")
      (node (ref "IC1") (pin "19") (pinfunction "NC_9_19") (pintype "bidirectional+no_connect"))
    )
    (net (code "308") (name "unconnected-(IC1-NC_10-Pad63)") (class "Default")
      (node (ref "IC1") (pin "63") (pinfunction "NC_10_63") (pintype "bidirectional+no_connect"))
    )
    (net (code "309") (name "unconnected-(IC1-NC_11-Pad72)") (class "Default")
      (node (ref "IC1") (pin "72") (pinfunction "NC_11_72") (pintype "bidirectional+no_connect"))
    )
    (net (code "310") (name "unconnected-(IC1-NC_12-Pad119)") (class "Default")
      (node (ref "IC1") (pin "119") (pinfunction "NC_12_119") (pintype "bidirectional+no_connect"))
    )
    (net (code "311") (name "unconnected-(IC1-PGND_2-Pad107)") (class "Default")
      (node (ref "IC1") (pin "107") (pinfunction "PGND_2_107") (pintype "bidirectional+no_connect"))
    )
    (net (code "312") (name "unconnected-(IC1-SCK{slash}TCON[3]{slash}GPIO-Pad109)") (class "Default")
      (node (ref "IC1") (pin "109") (pinfunction "SCK/TCON[3]/GPIO_109") (pintype "bidirectional+no_connect"))
    )
    (net (code "313") (name "unconnected-(IC1-SD0{slash}SPDIF0{slash}TCON[9]{slash}GPIO-Pad105)") (class "Default")
      (node (ref "IC1") (pin "105") (pinfunction "SD0/SPDIF0/TCON[9]/GPIO_105") (pintype "bidirectional+no_connect"))
    )
    (net (code "314") (name "unconnected-(IC1-SD1{slash}SPDIF1{slash}TCON[5]{slash}GPIO{slash}IRQB{slash}IICSDA-Pad104)") (class "Default")
      (node (ref "IC1") (pin "104") (pinfunction "SD1/SPDIF1/TCON[5]/GPIO/IRQB/IICSDA_104") (pintype "bidirectional+no_connect"))
    )
    (net (code "315") (name "unconnected-(IC1-SD1{slash}SPDIF1{slash}TCON[9]{slash}GPIO-Pad112)") (class "Default")
      (node (ref "IC1") (pin "112") (pinfunction "SD1/SPDIF1/TCON[9]/GPIO_112") (pintype "bidirectional+no_connect"))
    )
    (net (code "316") (name "unconnected-(IC1-SD2{slash}SPDIF2{slash}TCON[1]{slash}GPIO{slash}IRDA-Pad113)") (class "Default")
      (node (ref "IC1") (pin "113") (pinfunction "SD2/SPDIF2/TCON[1]/GPIO/IRDA_113") (pintype "bidirectional+no_connect"))
    )
    (net (code "317") (name "unconnected-(IC1-SD2{slash}SPDIF2{slash}TCON[8]{slash}GPIO{slash}IICSCL{slash}PWM1-Pad103)") (class "Default")
      (node (ref "IC1") (pin "103") (pinfunction "SD2/SPDIF2/TCON[8]/GPIO/IICSCL/PWM1_103") (pintype "bidirectional+no_connect"))
    )
    (net (code "318") (name "unconnected-(IC1-SD3{slash}SPDIF3{slash}TCON[13]{slash}GPIO{slash}VCLK-Pad114)") (class "Default")
      (node (ref "IC1") (pin "114") (pinfunction "SD3/SPDIF3/TCON[13]/GPIO/VCLK_114") (pintype "bidirectional+no_connect"))
    )
    (net (code "319") (name "unconnected-(IC1-V8_0{slash}AHS1-Pad39)") (class "Default")
      (node (ref "IC1") (pin "39") (pinfunction "V8_0/AHS1_39") (pintype "bidirectional+no_connect"))
    )
    (net (code "320") (name "unconnected-(IC1-V8_0{slash}VIN-3-Pad48)") (class "Default")
      (node (ref "IC1") (pin "48") (pinfunction "V8_0/VIN-3_48") (pintype "bidirectional+no_connect"))
    )
    (net (code "321") (name "unconnected-(IC1-V8_1{slash}R1+-Pad37)") (class "Default")
      (node (ref "IC1") (pin "37") (pinfunction "V8_1/R1+_37") (pintype "bidirectional+no_connect"))
    )
    (net (code "322") (name "unconnected-(IC1-V8_1{slash}VIN+3-Pad47)") (class "Default")
      (node (ref "IC1") (pin "47") (pinfunction "V8_1/VIN+3_47") (pintype "bidirectional+no_connect"))
    )
    (net (code "323") (name "unconnected-(IC1-V8_2{slash}R1--Pad36)") (class "Default")
      (node (ref "IC1") (pin "36") (pinfunction "V8_2/R1-_36") (pintype "bidirectional+no_connect"))
    )
    (net (code "324") (name "unconnected-(IC1-V8_2{slash}VIN-2-Pad46)") (class "Default")
      (node (ref "IC1") (pin "46") (pinfunction "V8_2/VIN-2_46") (pintype "bidirectional+no_connect"))
    )
    (net (code "325") (name "unconnected-(IC1-V8_3{slash}SOG1-Pad35)") (class "Default")
      (node (ref "IC1") (pin "35") (pinfunction "V8_3/SOG1_35") (pintype "bidirectional+no_connect"))
    )
    (net (code "326") (name "unconnected-(IC1-V8_3{slash}VIN+2-Pad45)") (class "Default")
      (node (ref "IC1") (pin "45") (pinfunction "V8_3/VIN+2_45") (pintype "bidirectional+no_connect"))
    )
    (net (code "327") (name "unconnected-(IC1-V8_4{slash}G1+-Pad34)") (class "Default")
      (node (ref "IC1") (pin "34") (pinfunction "V8_4/G1+_34") (pintype "bidirectional+no_connect"))
    )
    (net (code "328") (name "unconnected-(IC1-V8_5{slash}G1--Pad33)") (class "Default")
      (node (ref "IC1") (pin "33") (pinfunction "V8_5/G1-_33") (pintype "bidirectional+no_connect"))
    )
    (net (code "329") (name "unconnected-(IC1-V8_6{slash}B1+-Pad32)") (class "Default")
      (node (ref "IC1") (pin "32") (pinfunction "V8_6/B1+_32") (pintype "bidirectional+no_connect"))
    )
    (net (code "330") (name "unconnected-(IC1-V8_6{slash}VIN-0-Pad42)") (class "Default")
      (node (ref "IC1") (pin "42") (pinfunction "V8_6/VIN-0_42") (pintype "bidirectional+no_connect"))
    )
    (net (code "331") (name "unconnected-(IC1-V8_7{slash}B1--Pad31)") (class "Default")
      (node (ref "IC1") (pin "31") (pinfunction "V8_7/B1-_31") (pintype "bidirectional+no_connect"))
    )
    (net (code "332") (name "unconnected-(IC1-V8_7{slash}VIN+0-Pad41)") (class "Default")
      (node (ref "IC1") (pin "41") (pinfunction "V8_7/VIN+0_41") (pintype "bidirectional+no_connect"))
    )
    (net (code "333") (name "unconnected-(IC1-VCLK{slash}AVS1-Pad40)") (class "Default")
      (node (ref "IC1") (pin "40") (pinfunction "VCLK/AVS1_40") (pintype "bidirectional+no_connect"))
    )
    (net (code "334") (name "unconnected-(J13-SBU1-PadA8)") (class "Default")
      (node (ref "J13") (pin "A8") (pinfunction "SBU1_A8") (pintype "unspecified+no_connect"))
    )
    (net (code "335") (name "unconnected-(J13-SBU2-PadB8)") (class "Default")
      (node (ref "J13") (pin "B8") (pinfunction "SBU2_B8") (pintype "unspecified+no_connect"))
    )
    (net (code "336") (name "unconnected-(U9-MUTE-Pad1)") (class "Default")
      (node (ref "U9") (pin "1") (pinfunction "MUTE_1") (pintype "unspecified+no_connect"))
    )
    (net (code "337") (name "unconnected-(U12-EP-Pad9)") (class "Default")
      (node (ref "U12") (pin "9") (pinfunction "EP_9") (pintype "unspecified+no_connect"))
    )
    (net (code "338") (name "unconnected-(U13-GPIO0-Pad2)") (class "Default")
      (node (ref "U13") (pin "2") (pinfunction "GPIO0_2") (pintype "bidirectional+no_connect"))
    )
    (net (code "339") (name "unconnected-(U13-GPIO1-Pad3)") (class "Default")
      (node (ref "U13") (pin "3") (pinfunction "GPIO1_3") (pintype "bidirectional+no_connect"))
    )
    (net (code "340") (name "unconnected-(U13-GPIO10-Pad13)") (class "Default")
      (node (ref "U13") (pin "13") (pinfunction "GPIO10_13") (pintype "bidirectional+no_connect"))
    )
    (net (code "341") (name "unconnected-(U13-GPIO11-Pad14)") (class "Default")
      (node (ref "U13") (pin "14") (pinfunction "GPIO11_14") (pintype "bidirectional+no_connect"))
    )
    (net (code "342") (name "unconnected-(U13-GPIO12-Pad15)") (class "Default")
      (node (ref "U13") (pin "15") (pinfunction "GPIO12_15") (pintype "bidirectional+no_connect"))
    )
    (net (code "343") (name "unconnected-(U13-GPIO13-Pad16)") (class "Default")
      (node (ref "U13") (pin "16") (pinfunction "GPIO13_16") (pintype "bidirectional+no_connect"))
    )
    (net (code "344") (name "unconnected-(U13-GPIO14-Pad17)") (class "Default")
      (node (ref "U13") (pin "17") (pinfunction "GPIO14_17") (pintype "bidirectional+no_connect"))
    )
    (net (code "345") (name "unconnected-(U13-GPIO15-Pad18)") (class "Default")
      (node (ref "U13") (pin "18") (pinfunction "GPIO15_18") (pintype "bidirectional+no_connect"))
    )
    (net (code "346") (name "unconnected-(U13-GPIO22-Pad34)") (class "Default")
      (node (ref "U13") (pin "34") (pinfunction "GPIO22_34") (pintype "bidirectional+no_connect"))
    )
    (net (code "347") (name "vol+") (class "Default")
      (node (ref "FPC2") (pin "7") (pinfunction "7_7") (pintype "unspecified"))
      (node (ref "PS2") (pin "14") (pinfunction "14_14") (pintype "unspecified"))
    )
    (net (code "348") (name "vol-") (class "Default")
      (node (ref "FPC2") (pin "6") (pinfunction "6_6") (pintype "unspecified"))
      (node (ref "PS2") (pin "15") (pinfunction "15_15") (pintype "unspecified"))
    )
  )
)
